# nt08.net
KiCad netlist of a schematic drawn in EAGLE
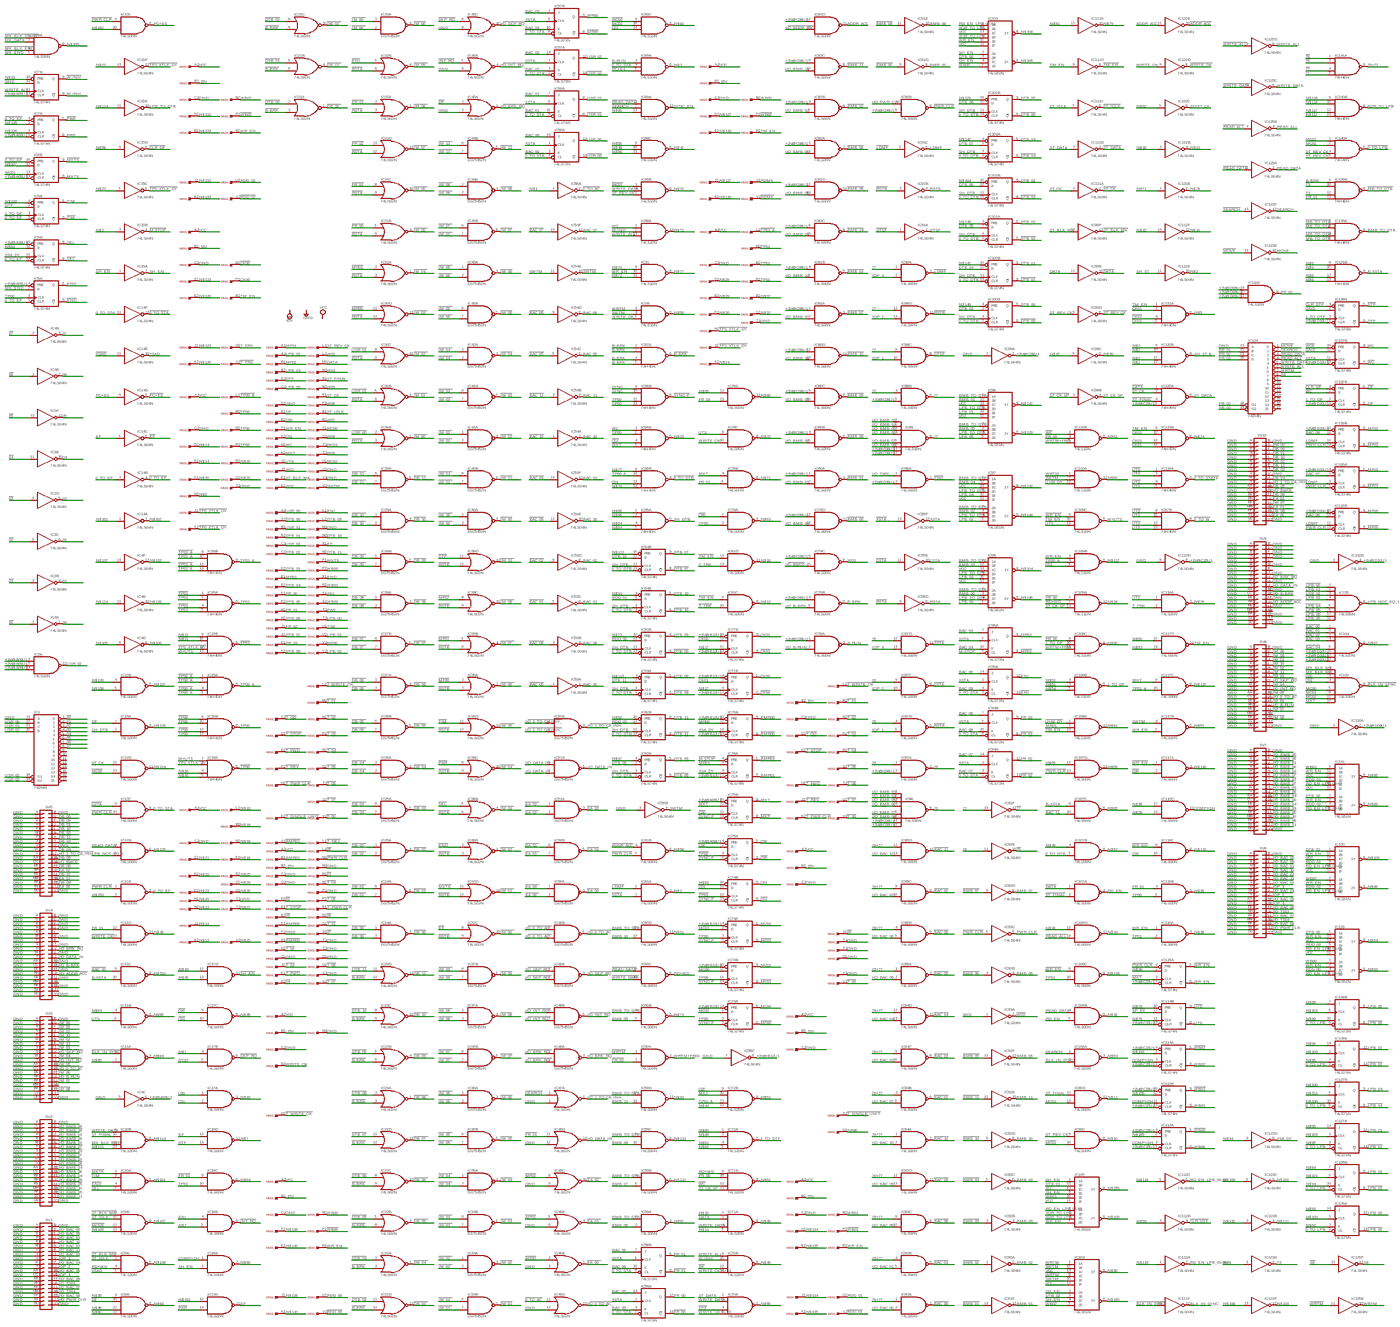
[diagram p0: schematic, sheet 1, overview]
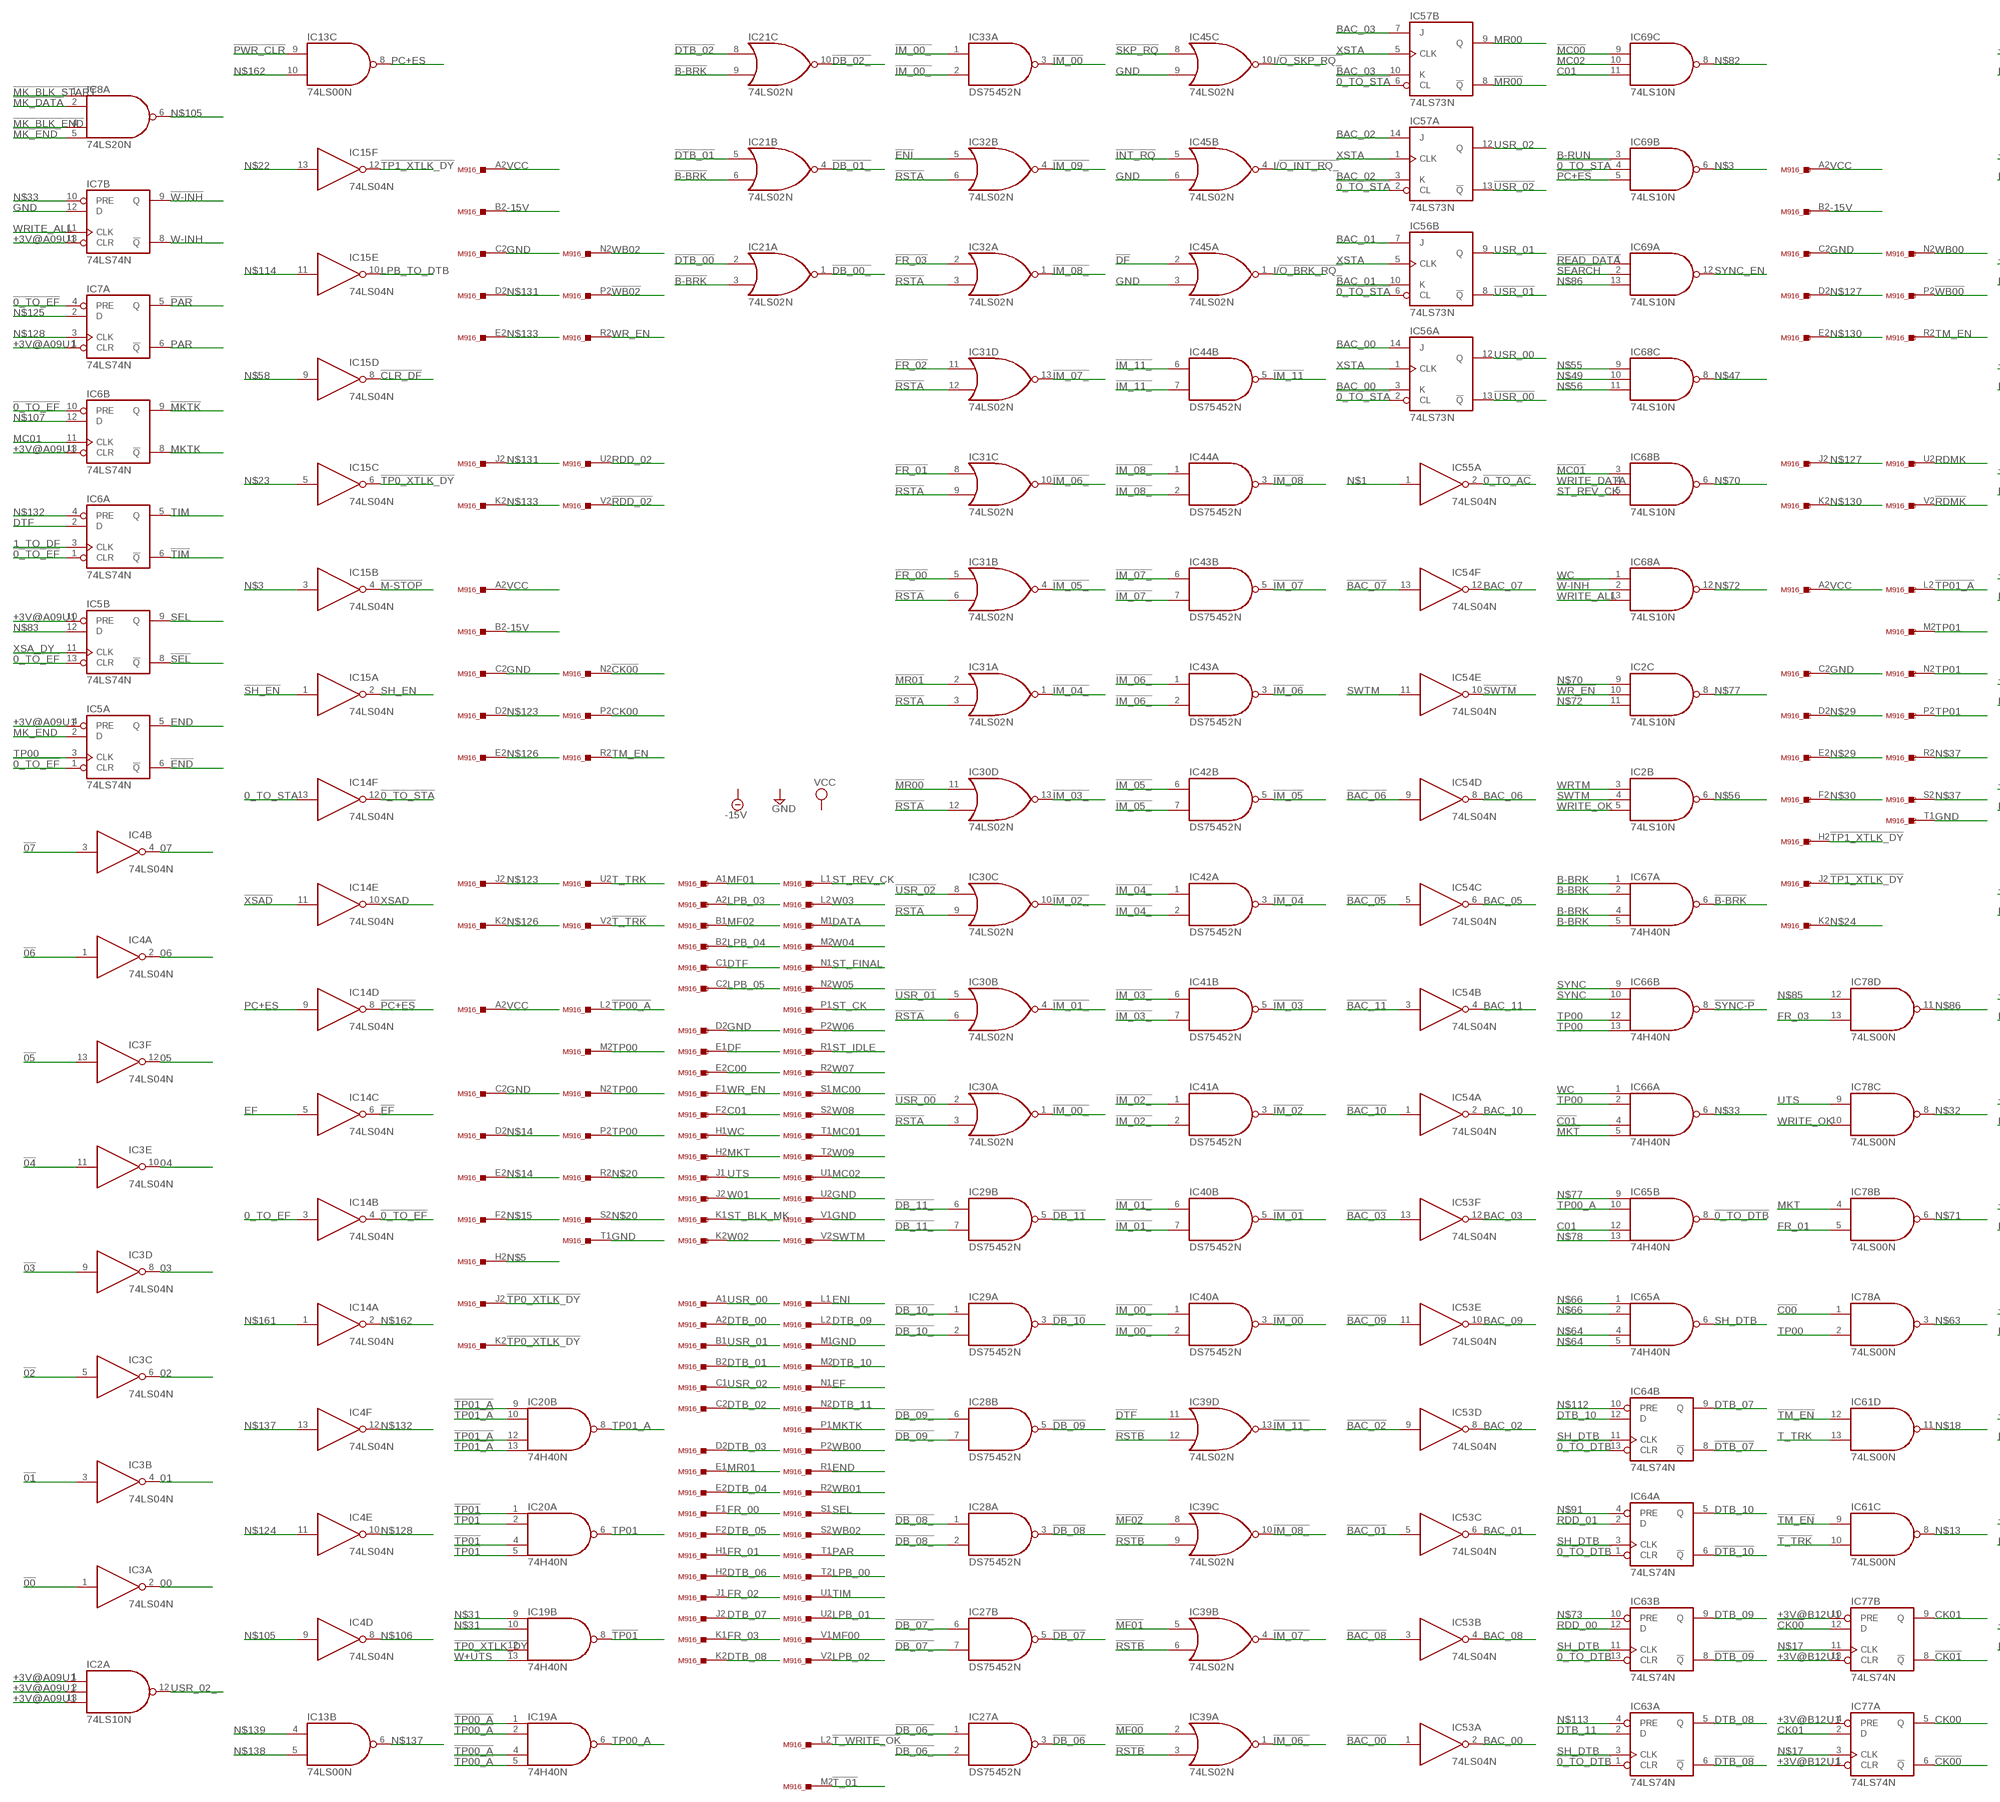
[diagram p1: schematic, sheet 1, part 1 of 4]
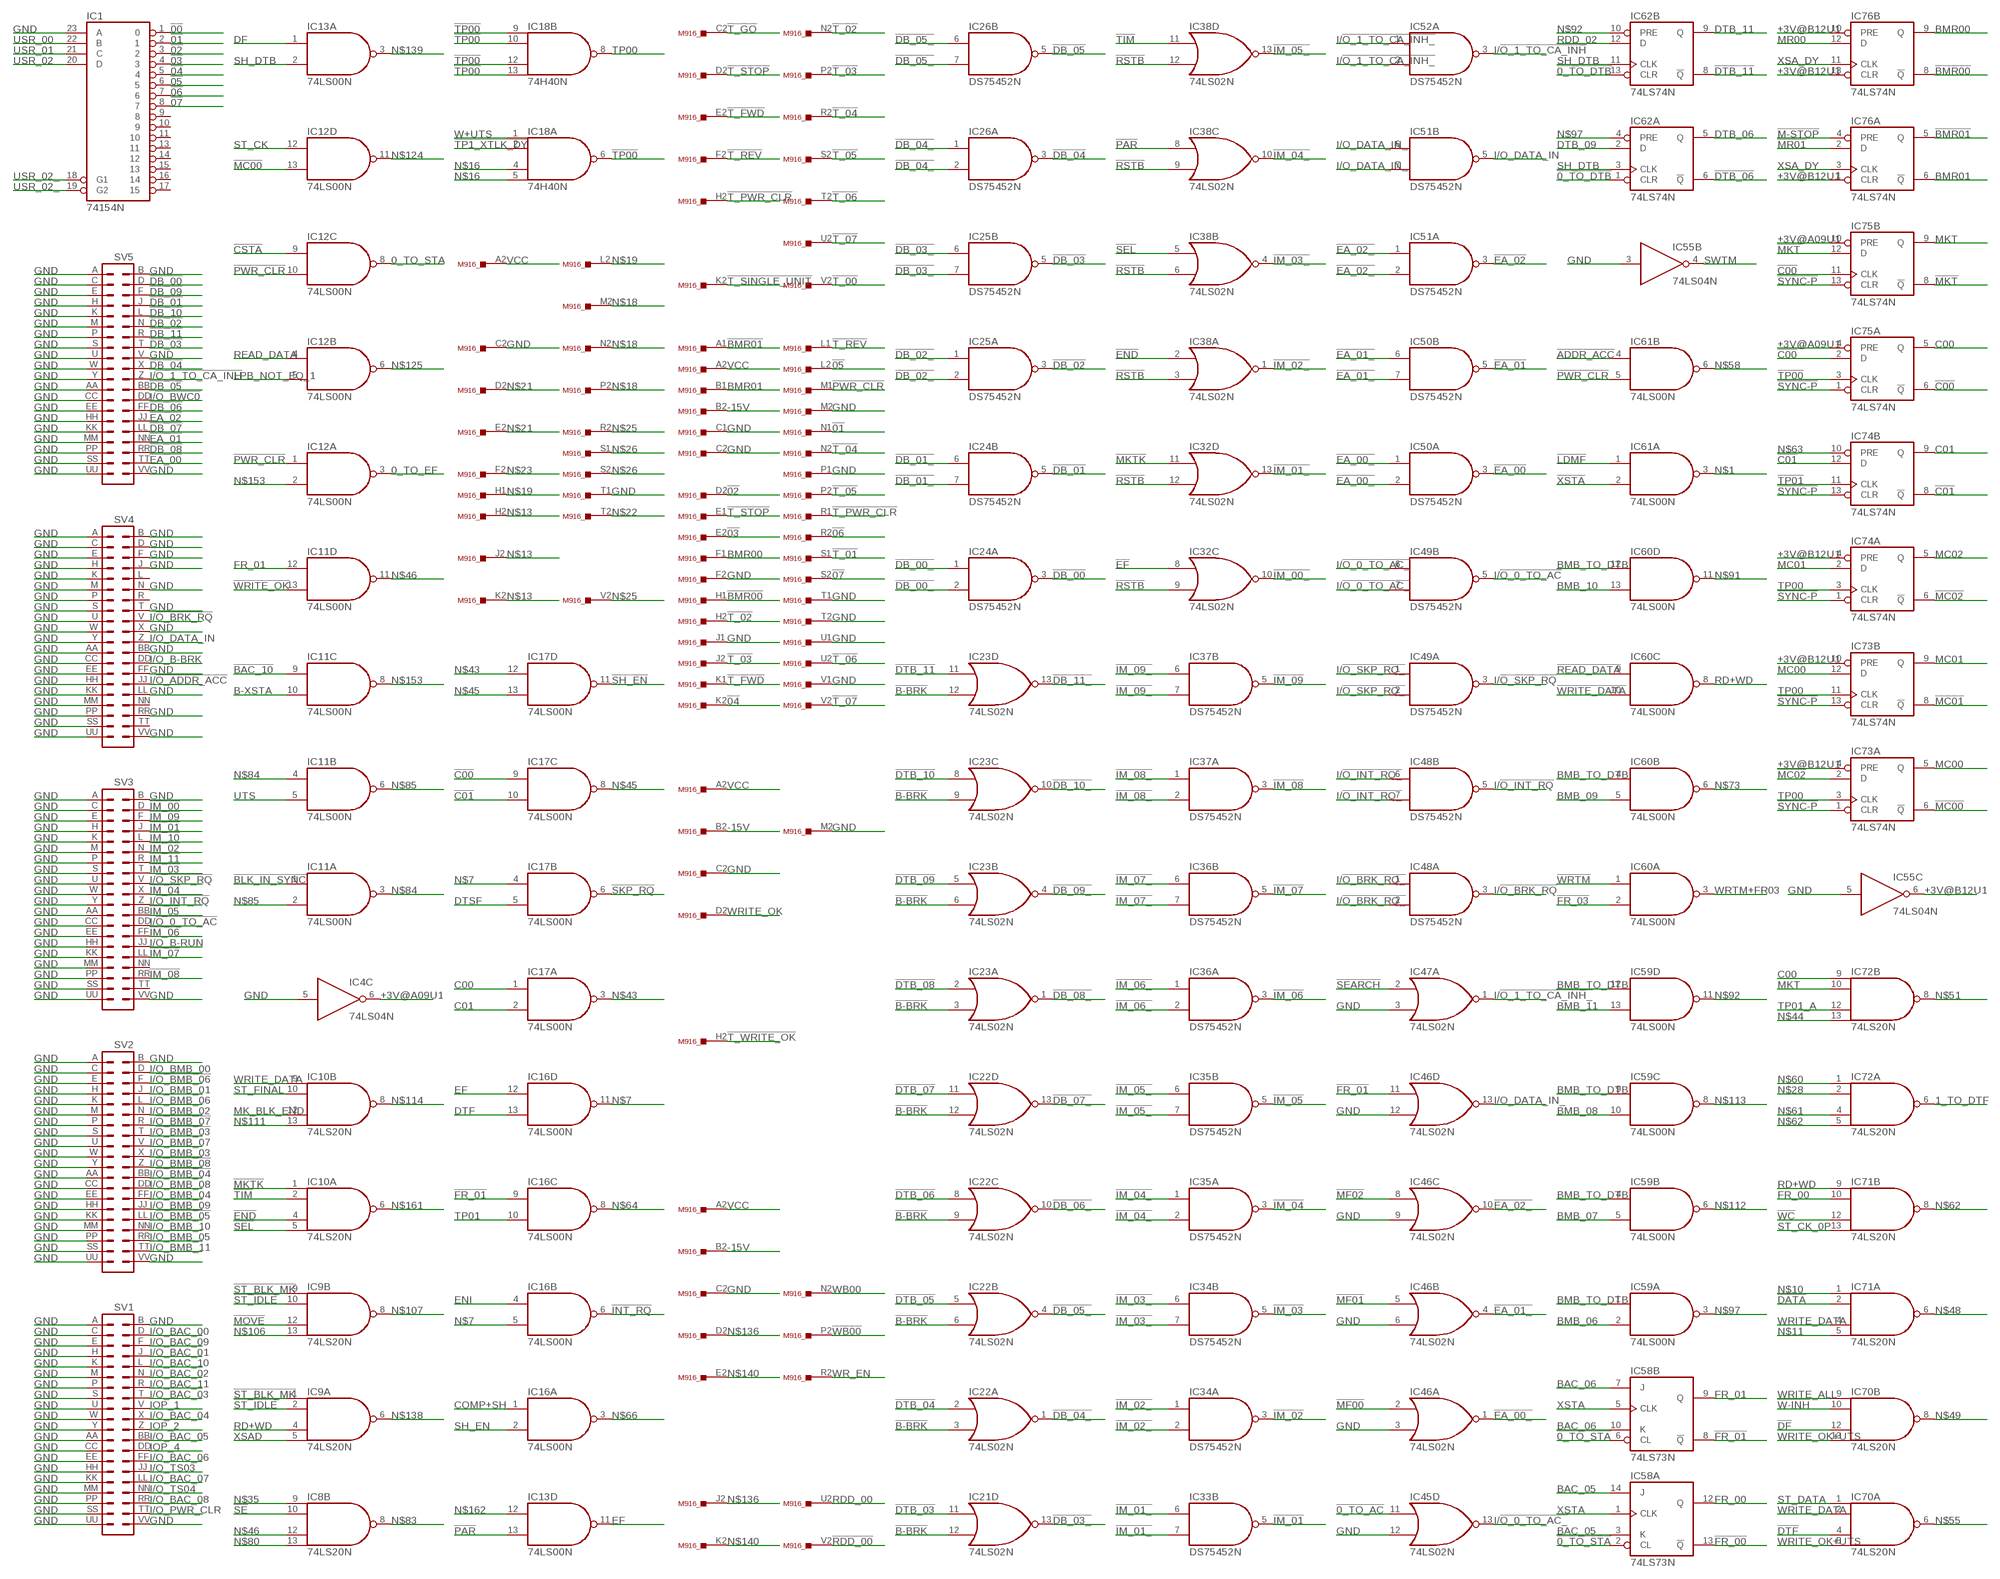
[diagram p2: schematic, sheet 1, part 2 of 4]
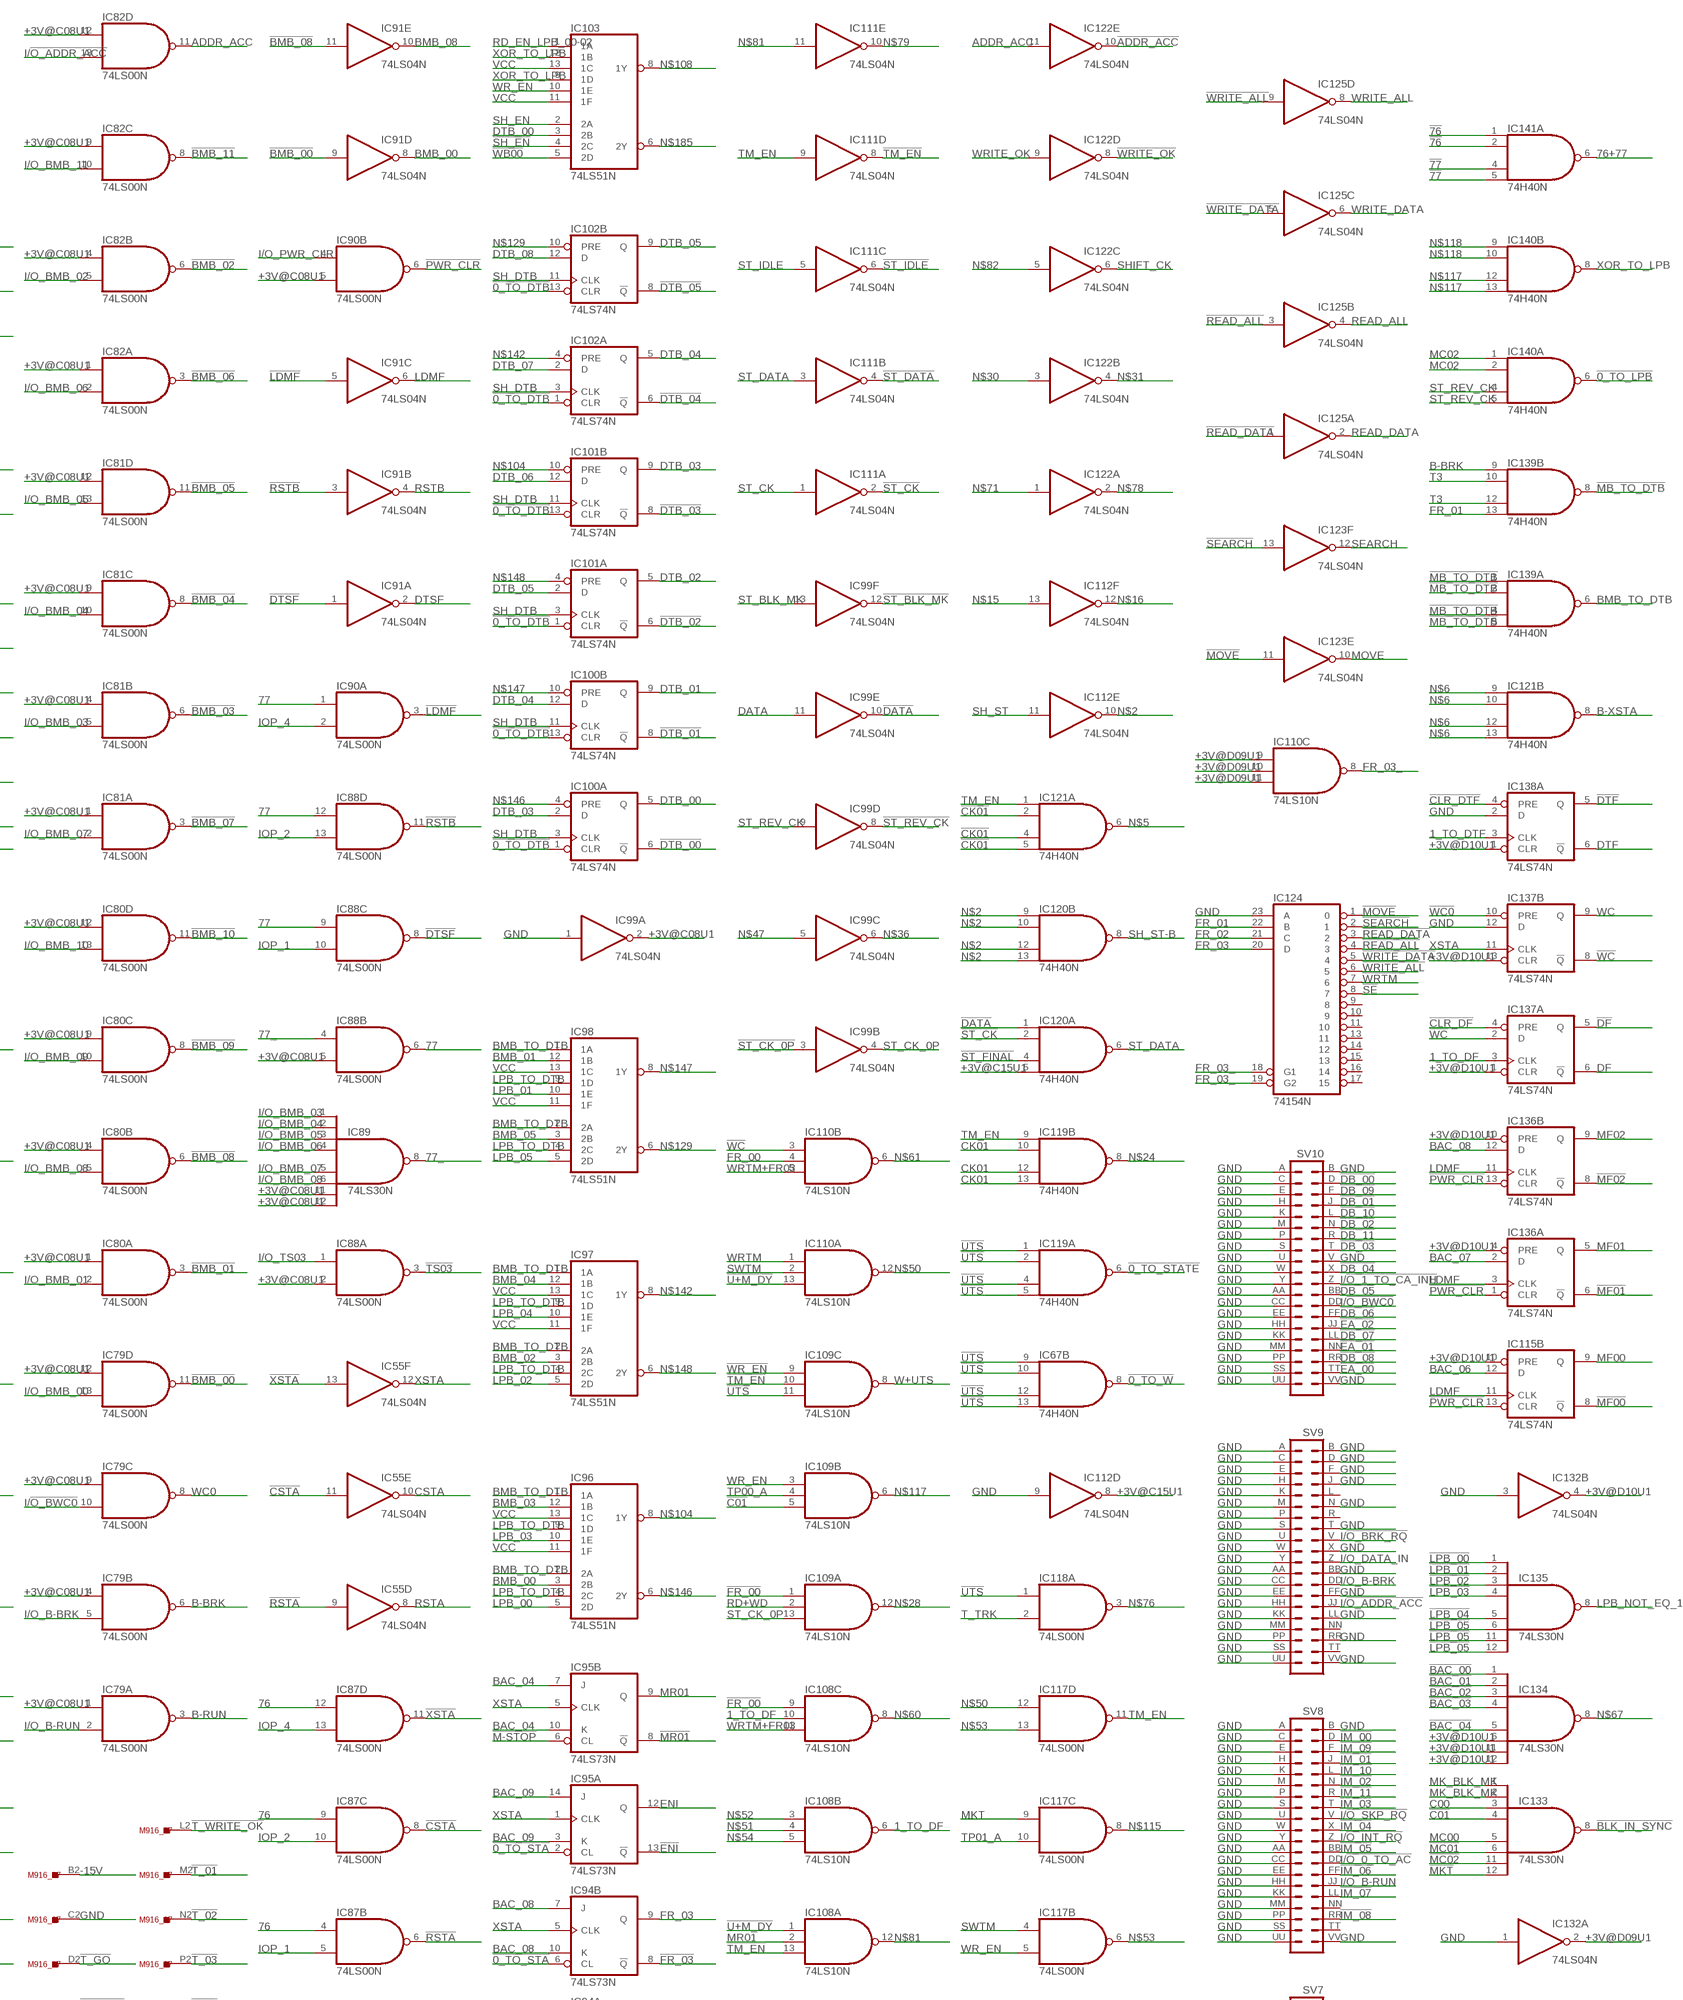
[diagram p3: schematic, sheet 1, part 3 of 4]
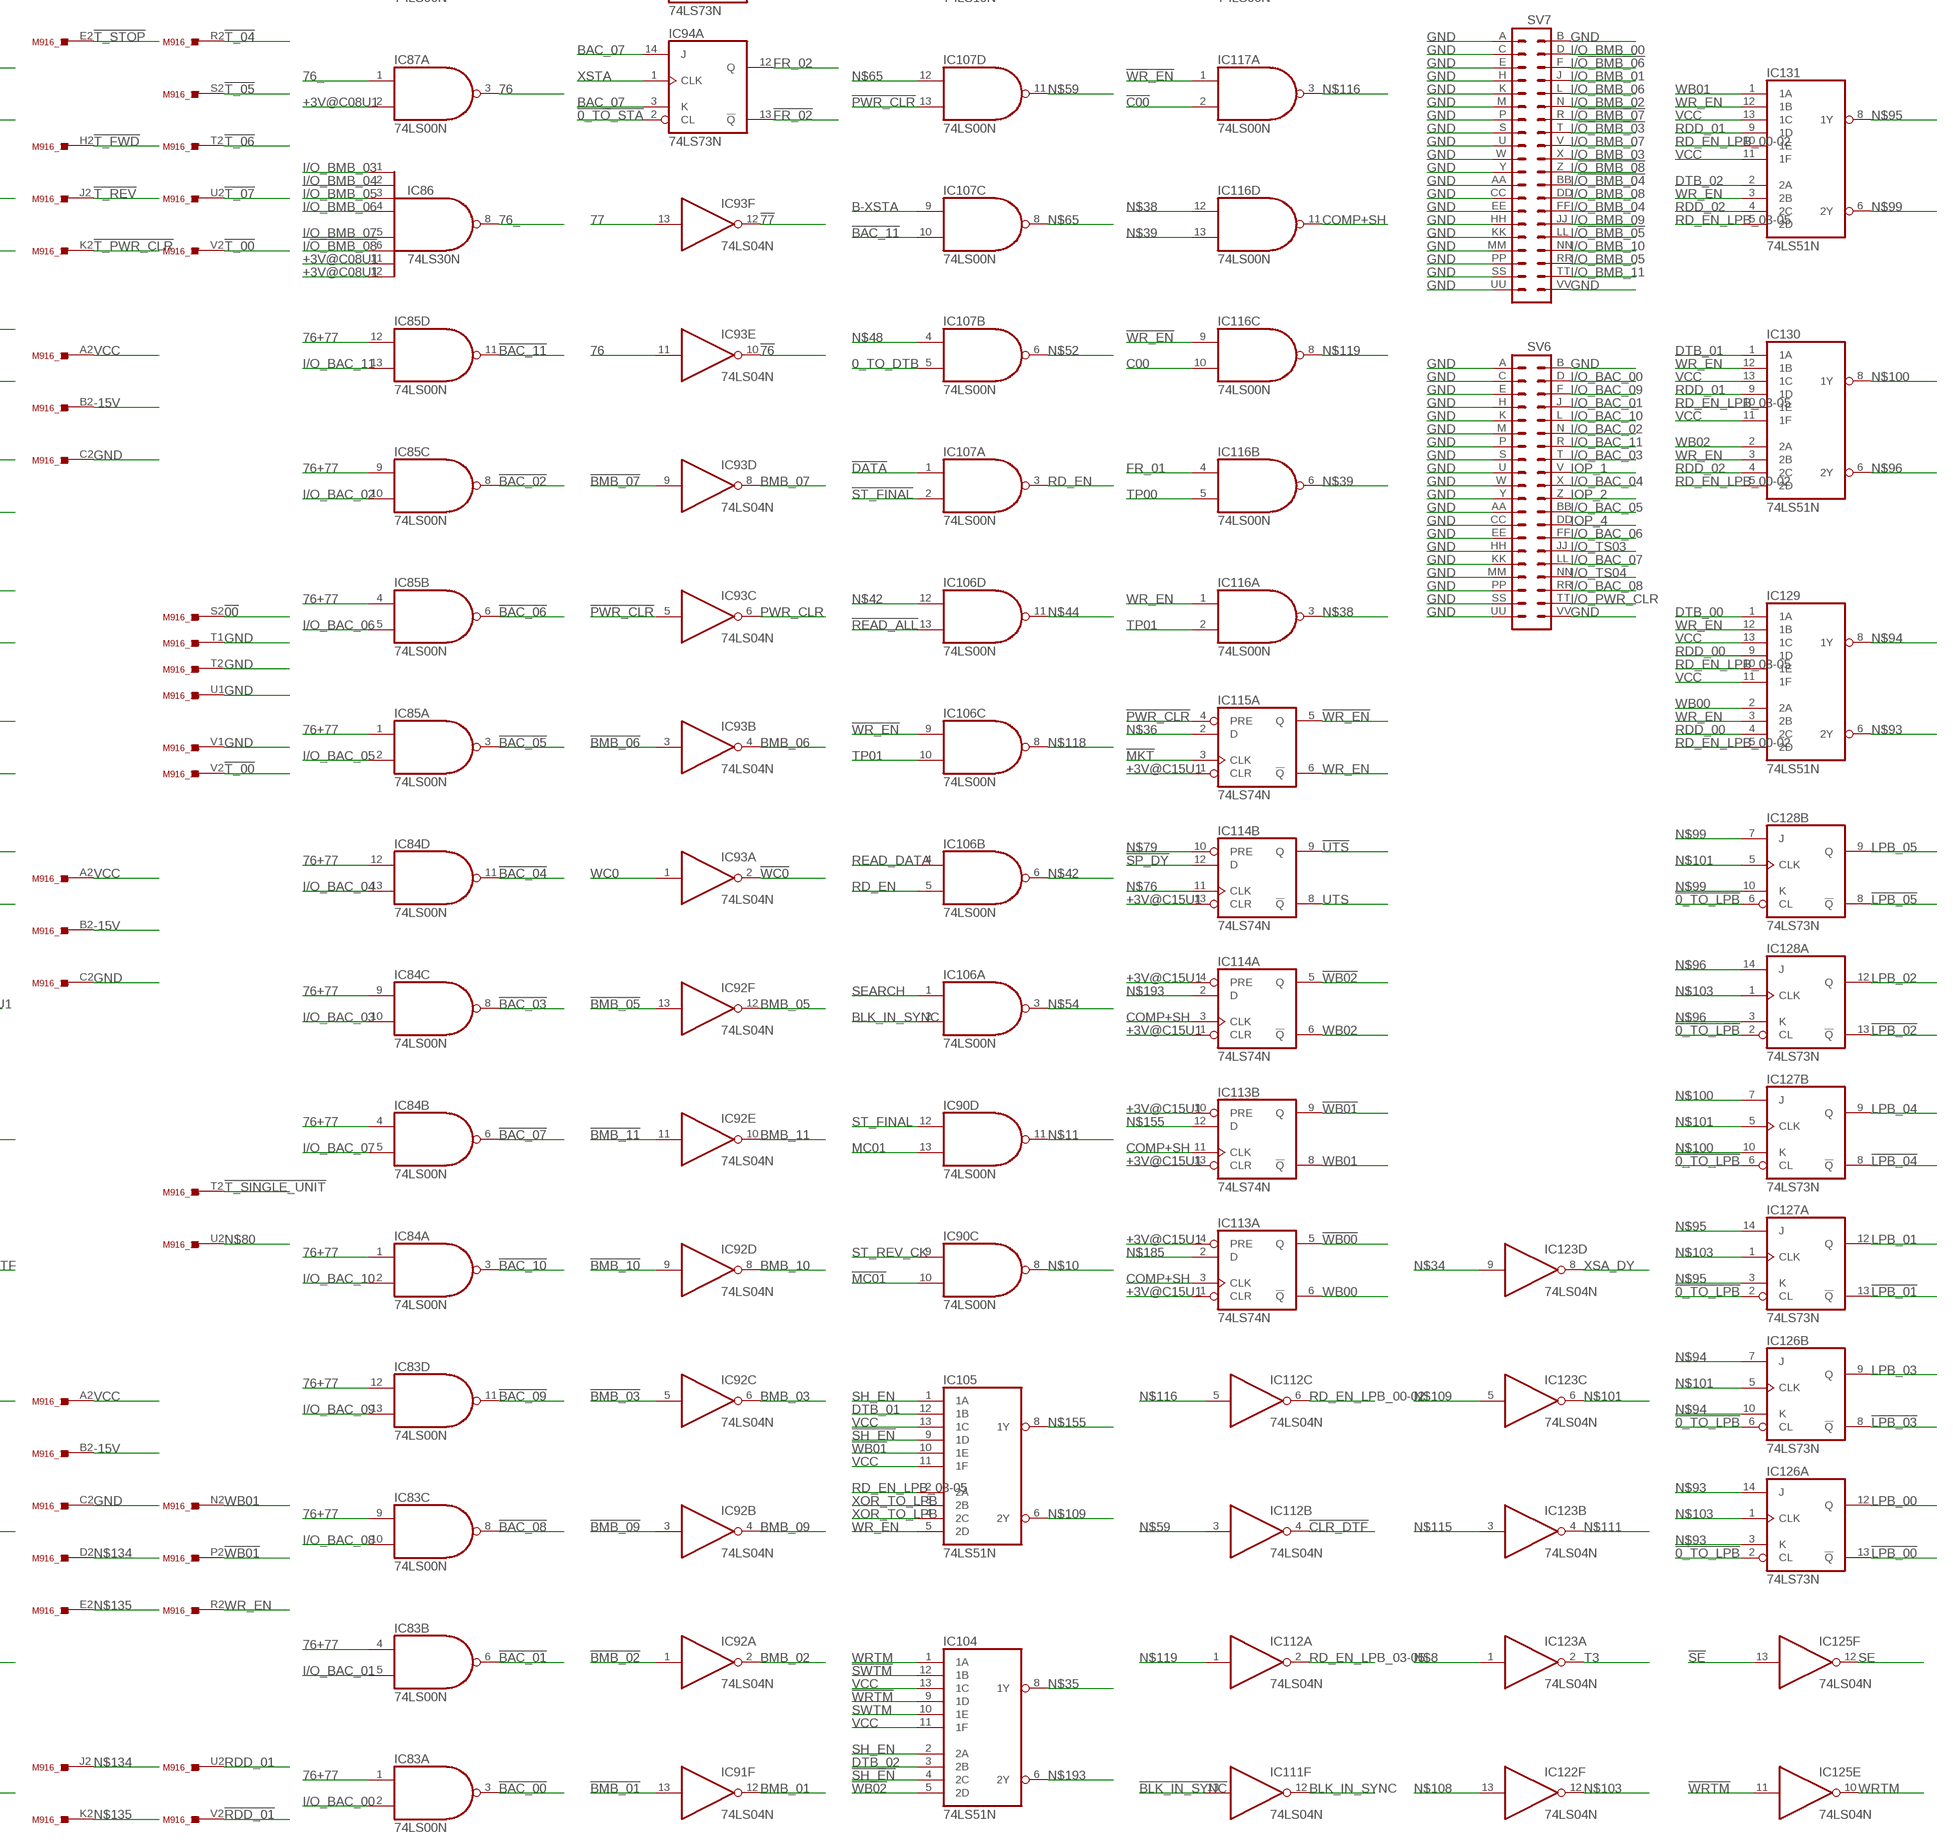
[diagram p4: schematic, sheet 1, part 4 of 4]
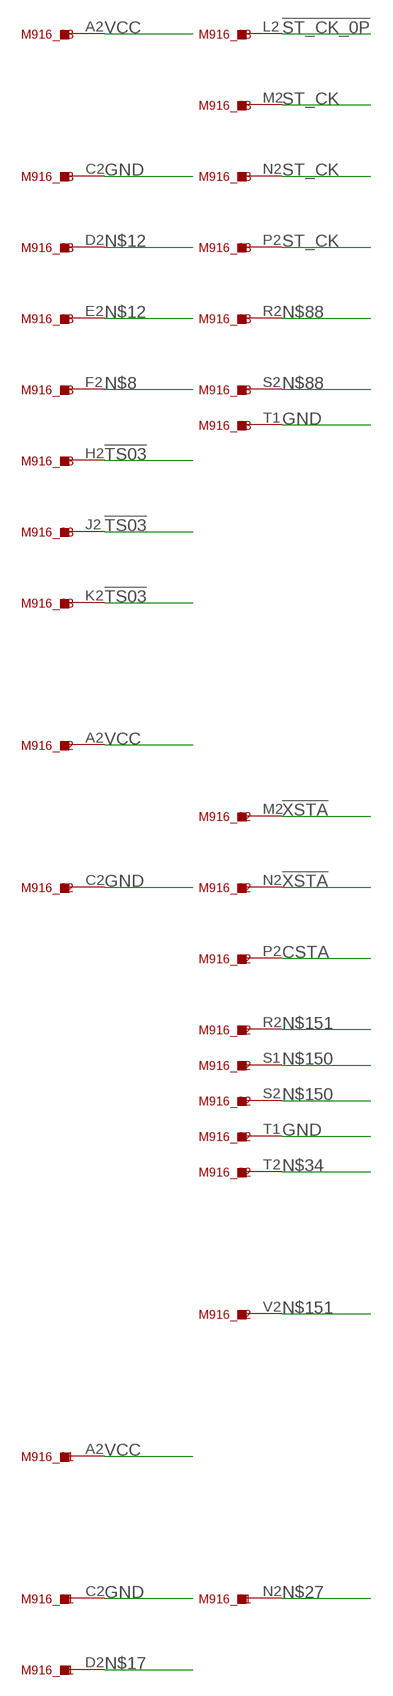
[diagram p5: schematic, sheet 2, part 1 of 2]
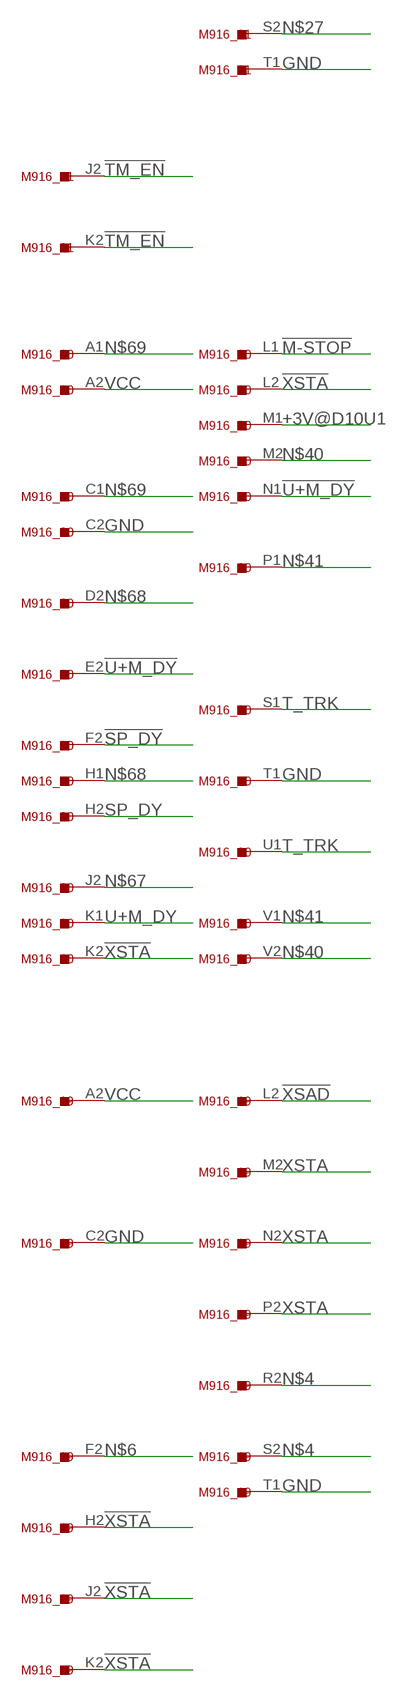
[diagram p6: schematic, sheet 2, part 2 of 2]

(export (version "E")
  (design (tool "Eeschema 10.0.6"))
  (components
    (comp (ref "M916_19")
      (value "M602")
      (footprint "eagle-import:H807")
      (libsource (lib "eagle-import") (part "M916"))
    )
    (comp (ref "M916_20")
      (value "M307")
      (footprint "eagle-import:H807")
      (libsource (lib "eagle-import") (part "M916"))
    )
    (comp (ref "M916_21")
      (value "M401")
      (footprint "eagle-import:H807")
      (libsource (lib "eagle-import") (part "M916"))
    )
    (comp (ref "M916_22")
      (value "M302")
      (footprint "eagle-import:H807")
      (libsource (lib "eagle-import") (part "M916"))
    )
    (comp (ref "M916_23")
      (value "M602")
      (footprint "eagle-import:H807")
      (libsource (lib "eagle-import") (part "M916"))
    )
    (comp (ref "IC1")
      (value "74154N")
      (footprint "eagle-import:DIL24-6")
      (libsource (lib "eagle-import") (part "74154N"))
    )
    (comp (ref "IC2")
      (value "74LS10N")
      (footprint "eagle-import:DIL14")
      (libsource (lib "eagle-import") (part "7410NLS"))
    )
    (comp (ref "IC3")
      (value "74LS04N")
      (footprint "eagle-import:DIL14")
      (libsource (lib "eagle-import") (part "7404NLS"))
    )
    (comp (ref "IC4")
      (value "74LS04N")
      (footprint "eagle-import:DIL14")
      (libsource (lib "eagle-import") (part "7404NLS"))
    )
    (comp (ref "IC5")
      (value "74LS74N")
      (footprint "eagle-import:DIL14")
      (libsource (lib "eagle-import") (part "7474NLS"))
    )
    (comp (ref "IC6")
      (value "74LS74N")
      (footprint "eagle-import:DIL14")
      (libsource (lib "eagle-import") (part "7474NLS"))
    )
    (comp (ref "IC7")
      (value "74LS74N")
      (footprint "eagle-import:DIL14")
      (libsource (lib "eagle-import") (part "7474NLS"))
    )
    (comp (ref "IC8")
      (value "74LS20N")
      (footprint "eagle-import:DIL14")
      (libsource (lib "eagle-import") (part "7420NLS"))
    )
    (comp (ref "IC9")
      (value "74LS20N")
      (footprint "eagle-import:DIL14")
      (libsource (lib "eagle-import") (part "7420NLS"))
    )
    (comp (ref "IC10")
      (value "74LS20N")
      (footprint "eagle-import:DIL14")
      (libsource (lib "eagle-import") (part "7420NLS"))
    )
    (comp (ref "IC11")
      (value "74LS00N")
      (footprint "eagle-import:DIL14")
      (libsource (lib "eagle-import") (part "7400NLS"))
    )
    (comp (ref "IC12")
      (value "74LS00N")
      (footprint "eagle-import:DIL14")
      (libsource (lib "eagle-import") (part "7400NLS"))
    )
    (comp (ref "IC13")
      (value "74LS00N")
      (footprint "eagle-import:DIL14")
      (libsource (lib "eagle-import") (part "7400NLS"))
    )
    (comp (ref "IC14")
      (value "74LS04N")
      (footprint "eagle-import:DIL14")
      (libsource (lib "eagle-import") (part "7404NLS"))
    )
    (comp (ref "IC15")
      (value "74LS04N")
      (footprint "eagle-import:DIL14")
      (libsource (lib "eagle-import") (part "7404NLS"))
    )
    (comp (ref "IC16")
      (value "74LS00N")
      (footprint "eagle-import:DIL14")
      (libsource (lib "eagle-import") (part "7400NLS"))
    )
    (comp (ref "IC17")
      (value "74LS00N")
      (footprint "eagle-import:DIL14")
      (libsource (lib "eagle-import") (part "7400NLS"))
    )
    (comp (ref "IC18")
      (value "74H40N")
      (footprint "eagle-import:DIL14")
      (libsource (lib "eagle-import") (part "7420NS"))
    )
    (comp (ref "IC19")
      (value "74H40N")
      (footprint "eagle-import:DIL14")
      (libsource (lib "eagle-import") (part "7420NS"))
    )
    (comp (ref "IC20")
      (value "74H40N")
      (footprint "eagle-import:DIL14")
      (libsource (lib "eagle-import") (part "7420NS"))
    )
    (comp (ref "IC21")
      (value "74LS02N")
      (footprint "eagle-import:DIL14")
      (libsource (lib "eagle-import") (part "7402NLS"))
    )
    (comp (ref "IC22")
      (value "74LS02N")
      (footprint "eagle-import:DIL14")
      (libsource (lib "eagle-import") (part "7402NLS"))
    )
    (comp (ref "IC23")
      (value "74LS02N")
      (footprint "eagle-import:DIL14")
      (libsource (lib "eagle-import") (part "7402NLS"))
    )
    (comp (ref "IC24")
      (value "DS75452N")
      (footprint "eagle-import:DIL08")
      (libsource (lib "eagle-import") (part "DS75452N"))
    )
    (comp (ref "IC25")
      (value "DS75452N")
      (footprint "eagle-import:DIL08")
      (libsource (lib "eagle-import") (part "DS75452N"))
    )
    (comp (ref "IC26")
      (value "DS75452N")
      (footprint "eagle-import:DIL08")
      (libsource (lib "eagle-import") (part "DS75452N"))
    )
    (comp (ref "IC27")
      (value "DS75452N")
      (footprint "eagle-import:DIL08")
      (libsource (lib "eagle-import") (part "DS75452N"))
    )
    (comp (ref "IC28")
      (value "DS75452N")
      (footprint "eagle-import:DIL08")
      (libsource (lib "eagle-import") (part "DS75452N"))
    )
    (comp (ref "IC29")
      (value "DS75452N")
      (footprint "eagle-import:DIL08")
      (libsource (lib "eagle-import") (part "DS75452N"))
    )
    (comp (ref "IC30")
      (value "74LS02N")
      (footprint "eagle-import:DIL14")
      (libsource (lib "eagle-import") (part "7402NLS"))
    )
    (comp (ref "IC31")
      (value "74LS02N")
      (footprint "eagle-import:DIL14")
      (libsource (lib "eagle-import") (part "7402NLS"))
    )
    (comp (ref "IC32")
      (value "74LS02N")
      (footprint "eagle-import:DIL14")
      (libsource (lib "eagle-import") (part "7402NLS"))
    )
    (comp (ref "IC33")
      (value "DS75452N")
      (footprint "eagle-import:DIL08")
      (libsource (lib "eagle-import") (part "DS75452N"))
    )
    (comp (ref "IC34")
      (value "DS75452N")
      (footprint "eagle-import:DIL08")
      (libsource (lib "eagle-import") (part "DS75452N"))
    )
    (comp (ref "IC35")
      (value "DS75452N")
      (footprint "eagle-import:DIL08")
      (libsource (lib "eagle-import") (part "DS75452N"))
    )
    (comp (ref "IC36")
      (value "DS75452N")
      (footprint "eagle-import:DIL08")
      (libsource (lib "eagle-import") (part "DS75452N"))
    )
    (comp (ref "IC37")
      (value "DS75452N")
      (footprint "eagle-import:DIL08")
      (libsource (lib "eagle-import") (part "DS75452N"))
    )
    (comp (ref "IC38")
      (value "74LS02N")
      (footprint "eagle-import:DIL14")
      (libsource (lib "eagle-import") (part "7402NLS"))
    )
    (comp (ref "IC39")
      (value "74LS02N")
      (footprint "eagle-import:DIL14")
      (libsource (lib "eagle-import") (part "7402NLS"))
    )
    (comp (ref "IC40")
      (value "DS75452N")
      (footprint "eagle-import:DIL08")
      (libsource (lib "eagle-import") (part "DS75452N"))
    )
    (comp (ref "IC41")
      (value "DS75452N")
      (footprint "eagle-import:DIL08")
      (libsource (lib "eagle-import") (part "DS75452N"))
    )
    (comp (ref "IC42")
      (value "DS75452N")
      (footprint "eagle-import:DIL08")
      (libsource (lib "eagle-import") (part "DS75452N"))
    )
    (comp (ref "IC43")
      (value "DS75452N")
      (footprint "eagle-import:DIL08")
      (libsource (lib "eagle-import") (part "DS75452N"))
    )
    (comp (ref "IC44")
      (value "DS75452N")
      (footprint "eagle-import:DIL08")
      (libsource (lib "eagle-import") (part "DS75452N"))
    )
    (comp (ref "IC45")
      (value "74LS02N")
      (footprint "eagle-import:DIL14")
      (libsource (lib "eagle-import") (part "7402NLS"))
    )
    (comp (ref "IC46")
      (value "74LS02N")
      (footprint "eagle-import:DIL14")
      (libsource (lib "eagle-import") (part "7402NLS"))
    )
    (comp (ref "IC47")
      (value "74LS02N")
      (footprint "eagle-import:DIL14")
      (libsource (lib "eagle-import") (part "7402NLS"))
    )
    (comp (ref "IC48")
      (value "DS75452N")
      (footprint "eagle-import:DIL08")
      (libsource (lib "eagle-import") (part "DS75452N"))
    )
    (comp (ref "IC49")
      (value "DS75452N")
      (footprint "eagle-import:DIL08")
      (libsource (lib "eagle-import") (part "DS75452N"))
    )
    (comp (ref "IC50")
      (value "DS75452N")
      (footprint "eagle-import:DIL08")
      (libsource (lib "eagle-import") (part "DS75452N"))
    )
    (comp (ref "IC51")
      (value "DS75452N")
      (footprint "eagle-import:DIL08")
      (libsource (lib "eagle-import") (part "DS75452N"))
    )
    (comp (ref "IC52")
      (value "DS75452N")
      (footprint "eagle-import:DIL08")
      (libsource (lib "eagle-import") (part "DS75452N"))
    )
    (comp (ref "IC53")
      (value "74LS04N")
      (footprint "eagle-import:DIL14")
      (libsource (lib "eagle-import") (part "7404NLS"))
    )
    (comp (ref "IC54")
      (value "74LS04N")
      (footprint "eagle-import:DIL14")
      (libsource (lib "eagle-import") (part "7404NLS"))
    )
    (comp (ref "IC55")
      (value "74LS04N")
      (footprint "eagle-import:DIL14")
      (libsource (lib "eagle-import") (part "7404NLS"))
    )
    (comp (ref "IC56")
      (value "74LS73N")
      (footprint "eagle-import:DIL14")
      (libsource (lib "eagle-import") (part "7473NLS"))
    )
    (comp (ref "IC57")
      (value "74LS73N")
      (footprint "eagle-import:DIL14")
      (libsource (lib "eagle-import") (part "7473NLS"))
    )
    (comp (ref "IC58")
      (value "74LS73N")
      (footprint "eagle-import:DIL14")
      (libsource (lib "eagle-import") (part "7473NLS"))
    )
    (comp (ref "IC59")
      (value "74LS00N")
      (footprint "eagle-import:DIL14")
      (libsource (lib "eagle-import") (part "7400NLS"))
    )
    (comp (ref "IC60")
      (value "74LS00N")
      (footprint "eagle-import:DIL14")
      (libsource (lib "eagle-import") (part "7400NLS"))
    )
    (comp (ref "IC61")
      (value "74LS00N")
      (footprint "eagle-import:DIL14")
      (libsource (lib "eagle-import") (part "7400NLS"))
    )
    (comp (ref "IC62")
      (value "74LS74N")
      (footprint "eagle-import:DIL14")
      (libsource (lib "eagle-import") (part "7474NLS"))
    )
    (comp (ref "IC63")
      (value "74LS74N")
      (footprint "eagle-import:DIL14")
      (libsource (lib "eagle-import") (part "7474NLS"))
    )
    (comp (ref "IC64")
      (value "74LS74N")
      (footprint "eagle-import:DIL14")
      (libsource (lib "eagle-import") (part "7474NLS"))
    )
    (comp (ref "IC65")
      (value "74H40N")
      (footprint "eagle-import:DIL14")
      (libsource (lib "eagle-import") (part "7420NS"))
    )
    (comp (ref "IC66")
      (value "74H40N")
      (footprint "eagle-import:DIL14")
      (libsource (lib "eagle-import") (part "7420NS"))
    )
    (comp (ref "IC67")
      (value "74H40N")
      (footprint "eagle-import:DIL14")
      (libsource (lib "eagle-import") (part "7420NS"))
    )
    (comp (ref "IC68")
      (value "74LS10N")
      (footprint "eagle-import:DIL14")
      (libsource (lib "eagle-import") (part "7410NLS"))
    )
    (comp (ref "IC69")
      (value "74LS10N")
      (footprint "eagle-import:DIL14")
      (libsource (lib "eagle-import") (part "7410NLS"))
    )
    (comp (ref "IC70")
      (value "74LS20N")
      (footprint "eagle-import:DIL14")
      (libsource (lib "eagle-import") (part "7420NLS"))
    )
    (comp (ref "IC71")
      (value "74LS20N")
      (footprint "eagle-import:DIL14")
      (libsource (lib "eagle-import") (part "7420NLS"))
    )
    (comp (ref "IC72")
      (value "74LS20N")
      (footprint "eagle-import:DIL14")
      (libsource (lib "eagle-import") (part "7420NLS"))
    )
    (comp (ref "IC73")
      (value "74LS74N")
      (footprint "eagle-import:DIL14")
      (libsource (lib "eagle-import") (part "7474NLS"))
    )
    (comp (ref "IC74")
      (value "74LS74N")
      (footprint "eagle-import:DIL14")
      (libsource (lib "eagle-import") (part "7474NLS"))
    )
    (comp (ref "IC75")
      (value "74LS74N")
      (footprint "eagle-import:DIL14")
      (libsource (lib "eagle-import") (part "7474NLS"))
    )
    (comp (ref "IC76")
      (value "74LS74N")
      (footprint "eagle-import:DIL14")
      (libsource (lib "eagle-import") (part "7474NLS"))
    )
    (comp (ref "IC77")
      (value "74LS74N")
      (footprint "eagle-import:DIL14")
      (libsource (lib "eagle-import") (part "7474NLS"))
    )
    (comp (ref "IC78")
      (value "74LS00N")
      (footprint "eagle-import:DIL14")
      (libsource (lib "eagle-import") (part "7400NLS"))
    )
    (comp (ref "IC79")
      (value "74LS00N")
      (footprint "eagle-import:DIL14")
      (libsource (lib "eagle-import") (part "7400NLS"))
    )
    (comp (ref "IC80")
      (value "74LS00N")
      (footprint "eagle-import:DIL14")
      (libsource (lib "eagle-import") (part "7400NLS"))
    )
    (comp (ref "IC81")
      (value "74LS00N")
      (footprint "eagle-import:DIL14")
      (libsource (lib "eagle-import") (part "7400NLS"))
    )
    (comp (ref "IC82")
      (value "74LS00N")
      (footprint "eagle-import:DIL14")
      (libsource (lib "eagle-import") (part "7400NLS"))
    )
    (comp (ref "IC83")
      (value "74LS00N")
      (footprint "eagle-import:DIL14")
      (libsource (lib "eagle-import") (part "7400NLS"))
    )
    (comp (ref "IC84")
      (value "74LS00N")
      (footprint "eagle-import:DIL14")
      (libsource (lib "eagle-import") (part "7400NLS"))
    )
    (comp (ref "IC85")
      (value "74LS00N")
      (footprint "eagle-import:DIL14")
      (libsource (lib "eagle-import") (part "7400NLS"))
    )
    (comp (ref "IC86")
      (value "74LS30N")
      (footprint "eagle-import:DIL14")
      (libsource (lib "eagle-import") (part "7430NLS"))
    )
    (comp (ref "IC87")
      (value "74LS00N")
      (footprint "eagle-import:DIL14")
      (libsource (lib "eagle-import") (part "7400NLS"))
    )
    (comp (ref "IC88")
      (value "74LS00N")
      (footprint "eagle-import:DIL14")
      (libsource (lib "eagle-import") (part "7400NLS"))
    )
    (comp (ref "IC89")
      (value "74LS30N")
      (footprint "eagle-import:DIL14")
      (libsource (lib "eagle-import") (part "7430NLS"))
    )
    (comp (ref "IC90")
      (value "74LS00N")
      (footprint "eagle-import:DIL14")
      (libsource (lib "eagle-import") (part "7400NLS"))
    )
    (comp (ref "IC91")
      (value "74LS04N")
      (footprint "eagle-import:DIL14")
      (libsource (lib "eagle-import") (part "7404NLS"))
    )
    (comp (ref "IC92")
      (value "74LS04N")
      (footprint "eagle-import:DIL14")
      (libsource (lib "eagle-import") (part "7404NLS"))
    )
    (comp (ref "IC93")
      (value "74LS04N")
      (footprint "eagle-import:DIL14")
      (libsource (lib "eagle-import") (part "7404NLS"))
    )
    (comp (ref "IC94")
      (value "74LS73N")
      (footprint "eagle-import:DIL14")
      (libsource (lib "eagle-import") (part "7473NLS"))
    )
    (comp (ref "IC95")
      (value "74LS73N")
      (footprint "eagle-import:DIL14")
      (libsource (lib "eagle-import") (part "7473NLS"))
    )
    (comp (ref "IC96")
      (value "74LS51N")
      (footprint "eagle-import:DIL14")
      (libsource (lib "eagle-import") (part "7451NLS"))
    )
    (comp (ref "IC97")
      (value "74LS51N")
      (footprint "eagle-import:DIL14")
      (libsource (lib "eagle-import") (part "7451NLS"))
    )
    (comp (ref "IC98")
      (value "74LS51N")
      (footprint "eagle-import:DIL14")
      (libsource (lib "eagle-import") (part "7451NLS"))
    )
    (comp (ref "IC99")
      (value "74LS04N")
      (footprint "eagle-import:DIL14")
      (libsource (lib "eagle-import") (part "7404NLS"))
    )
    (comp (ref "IC100")
      (value "74LS74N")
      (footprint "eagle-import:DIL14")
      (libsource (lib "eagle-import") (part "7474NLS"))
    )
    (comp (ref "IC101")
      (value "74LS74N")
      (footprint "eagle-import:DIL14")
      (libsource (lib "eagle-import") (part "7474NLS"))
    )
    (comp (ref "IC102")
      (value "74LS74N")
      (footprint "eagle-import:DIL14")
      (libsource (lib "eagle-import") (part "7474NLS"))
    )
    (comp (ref "IC103")
      (value "74LS51N")
      (footprint "eagle-import:DIL14")
      (libsource (lib "eagle-import") (part "7451NLS"))
    )
    (comp (ref "IC104")
      (value "74LS51N")
      (footprint "eagle-import:DIL14")
      (libsource (lib "eagle-import") (part "7451NLS"))
    )
    (comp (ref "IC105")
      (value "74LS51N")
      (footprint "eagle-import:DIL14")
      (libsource (lib "eagle-import") (part "7451NLS"))
    )
    (comp (ref "IC106")
      (value "74LS00N")
      (footprint "eagle-import:DIL14")
      (libsource (lib "eagle-import") (part "7400NLS"))
    )
    (comp (ref "IC107")
      (value "74LS00N")
      (footprint "eagle-import:DIL14")
      (libsource (lib "eagle-import") (part "7400NLS"))
    )
    (comp (ref "IC108")
      (value "74LS10N")
      (footprint "eagle-import:DIL14")
      (libsource (lib "eagle-import") (part "7410NLS"))
    )
    (comp (ref "IC109")
      (value "74LS10N")
      (footprint "eagle-import:DIL14")
      (libsource (lib "eagle-import") (part "7410NLS"))
    )
    (comp (ref "IC110")
      (value "74LS10N")
      (footprint "eagle-import:DIL14")
      (libsource (lib "eagle-import") (part "7410NLS"))
    )
    (comp (ref "IC111")
      (value "74LS04N")
      (footprint "eagle-import:DIL14")
      (libsource (lib "eagle-import") (part "7404NLS"))
    )
    (comp (ref "IC112")
      (value "74LS04N")
      (footprint "eagle-import:DIL14")
      (libsource (lib "eagle-import") (part "7404NLS"))
    )
    (comp (ref "IC113")
      (value "74LS74N")
      (footprint "eagle-import:DIL14")
      (libsource (lib "eagle-import") (part "7474NLS"))
    )
    (comp (ref "IC114")
      (value "74LS74N")
      (footprint "eagle-import:DIL14")
      (libsource (lib "eagle-import") (part "7474NLS"))
    )
    (comp (ref "IC115")
      (value "74LS74N")
      (footprint "eagle-import:DIL14")
      (libsource (lib "eagle-import") (part "7474NLS"))
    )
    (comp (ref "IC116")
      (value "74LS00N")
      (footprint "eagle-import:DIL14")
      (libsource (lib "eagle-import") (part "7400NLS"))
    )
    (comp (ref "IC117")
      (value "74LS00N")
      (footprint "eagle-import:DIL14")
      (libsource (lib "eagle-import") (part "7400NLS"))
    )
    (comp (ref "IC118")
      (value "74LS00N")
      (footprint "eagle-import:DIL14")
      (libsource (lib "eagle-import") (part "7400NLS"))
    )
    (comp (ref "IC119")
      (value "74H40N")
      (footprint "eagle-import:DIL14")
      (libsource (lib "eagle-import") (part "7420NS"))
    )
    (comp (ref "IC120")
      (value "74H40N")
      (footprint "eagle-import:DIL14")
      (libsource (lib "eagle-import") (part "7420NS"))
    )
    (comp (ref "IC121")
      (value "74H40N")
      (footprint "eagle-import:DIL14")
      (libsource (lib "eagle-import") (part "7420NS"))
    )
    (comp (ref "IC122")
      (value "74LS04N")
      (footprint "eagle-import:DIL14")
      (libsource (lib "eagle-import") (part "7404NLS"))
    )
    (comp (ref "IC123")
      (value "74LS04N")
      (footprint "eagle-import:DIL14")
      (libsource (lib "eagle-import") (part "7404NLS"))
    )
    (comp (ref "IC124")
      (value "74154N")
      (footprint "eagle-import:DIL24-6")
      (libsource (lib "eagle-import") (part "74154N"))
    )
    (comp (ref "IC125")
      (value "74LS04N")
      (footprint "eagle-import:DIL14")
      (libsource (lib "eagle-import") (part "7404NLS"))
    )
    (comp (ref "IC126")
      (value "74LS73N")
      (footprint "eagle-import:DIL14")
      (libsource (lib "eagle-import") (part "7473NLS"))
    )
    (comp (ref "IC127")
      (value "74LS73N")
      (footprint "eagle-import:DIL14")
      (libsource (lib "eagle-import") (part "7473NLS"))
    )
    (comp (ref "IC128")
      (value "74LS73N")
      (footprint "eagle-import:DIL14")
      (libsource (lib "eagle-import") (part "7473NLS"))
    )
    (comp (ref "IC129")
      (value "74LS51N")
      (footprint "eagle-import:DIL14")
      (libsource (lib "eagle-import") (part "7451NLS"))
    )
    (comp (ref "IC130")
      (value "74LS51N")
      (footprint "eagle-import:DIL14")
      (libsource (lib "eagle-import") (part "7451NLS"))
    )
    (comp (ref "IC131")
      (value "74LS51N")
      (footprint "eagle-import:DIL14")
      (libsource (lib "eagle-import") (part "7451NLS"))
    )
    (comp (ref "IC132")
      (value "74LS04N")
      (footprint "eagle-import:DIL14")
      (libsource (lib "eagle-import") (part "7404NLS"))
    )
    (comp (ref "IC133")
      (value "74LS30N")
      (footprint "eagle-import:DIL14")
      (libsource (lib "eagle-import") (part "7430NLS"))
    )
    (comp (ref "IC134")
      (value "74LS30N")
      (footprint "eagle-import:DIL14")
      (libsource (lib "eagle-import") (part "7430NLS"))
    )
    (comp (ref "IC135")
      (value "74LS30N")
      (footprint "eagle-import:DIL14")
      (libsource (lib "eagle-import") (part "7430NLS"))
    )
    (comp (ref "IC136")
      (value "74LS74N")
      (footprint "eagle-import:DIL14")
      (libsource (lib "eagle-import") (part "7474NLS"))
    )
    (comp (ref "IC137")
      (value "74LS74N")
      (footprint "eagle-import:DIL14")
      (libsource (lib "eagle-import") (part "7474NLS"))
    )
    (comp (ref "IC138")
      (value "74LS74N")
      (footprint "eagle-import:DIL14")
      (libsource (lib "eagle-import") (part "7474NLS"))
    )
    (comp (ref "IC139")
      (value "74H40N")
      (footprint "eagle-import:DIL14")
      (libsource (lib "eagle-import") (part "7420NS"))
    )
    (comp (ref "IC140")
      (value "74H40N")
      (footprint "eagle-import:DIL14")
      (libsource (lib "eagle-import") (part "7420NS"))
    )
    (comp (ref "IC141")
      (value "74H40N")
      (footprint "eagle-import:DIL14")
      (libsource (lib "eagle-import") (part "7420NS"))
    )
    (comp (ref "M916_1")
      (value "M302")
      (footprint "eagle-import:H807")
      (libsource (lib "eagle-import") (part "M916"))
    )
    (comp (ref "M916_2")
      (value "M602")
      (footprint "eagle-import:H807")
      (libsource (lib "eagle-import") (part "M916"))
    )
    (comp (ref "M916_3")
      (value "G888")
      (footprint "eagle-import:H807")
      (libsource (lib "eagle-import") (part "M916"))
    )
    (comp (ref "M916_4")
      (value "M302")
      (footprint "eagle-import:H807")
      (libsource (lib "eagle-import") (part "M916"))
    )
    (comp (ref "M916_5")
      (value "G888")
      (footprint "eagle-import:H807")
      (libsource (lib "eagle-import") (part "M916"))
    )
    (comp (ref "M916_6")
      (value "G888")
      (footprint "eagle-import:H807")
      (libsource (lib "eagle-import") (part "M916"))
    )
    (comp (ref "M916_7")
      (value "M633")
      (footprint "eagle-import:H807")
      (libsource (lib "eagle-import") (part "M916"))
    )
    (comp (ref "M916_8")
      (value "W023")
      (footprint "eagle-import:H807")
      (libsource (lib "eagle-import") (part "M916"))
    )
    (comp (ref "M916_9")
      (value "M916")
      (footprint "eagle-import:H807")
      (libsource (lib "eagle-import") (part "M916"))
    )
    (comp (ref "M916_10")
      (value "M916")
      (footprint "eagle-import:H807")
      (libsource (lib "eagle-import") (part "M916"))
    )
    (comp (ref "M916_12")
      (value "M602")
      (footprint "eagle-import:H807")
      (libsource (lib "eagle-import") (part "M916"))
    )
    (comp (ref "M916_13")
      (value "G888")
      (footprint "eagle-import:H807")
      (libsource (lib "eagle-import") (part "M916"))
    )
    (comp (ref "M916_14")
      (value "G888")
      (footprint "eagle-import:H807")
      (libsource (lib "eagle-import") (part "M916"))
    )
    (comp (ref "M916_15")
      (value "G879")
      (footprint "eagle-import:H807")
      (libsource (lib "eagle-import") (part "M916"))
    )
    (comp (ref "M916_16")
      (value "M633")
      (footprint "eagle-import:H807")
      (libsource (lib "eagle-import") (part "M916"))
    )
    (comp (ref "M916_17")
      (value "W005")
      (footprint "eagle-import:H807")
      (libsource (lib "eagle-import") (part "M916"))
    )
    (comp (ref "SV1")
      (value "DEC40PINV")
      (footprint "eagle-import:DEC40PINV")
      (libsource (lib "eagle-import") (part "DEC40PINV"))
    )
    (comp (ref "SV2")
      (value "DEC40PINV")
      (footprint "eagle-import:DEC40PINV")
      (libsource (lib "eagle-import") (part "DEC40PINV"))
    )
    (comp (ref "SV3")
      (value "DEC40PINV")
      (footprint "eagle-import:DEC40PINV")
      (libsource (lib "eagle-import") (part "DEC40PINV"))
    )
    (comp (ref "SV4")
      (value "DEC40PINV")
      (footprint "eagle-import:DEC40PINV")
      (libsource (lib "eagle-import") (part "DEC40PINV"))
    )
    (comp (ref "SV5")
      (value "DEC40PINV")
      (footprint "eagle-import:DEC40PINV")
      (libsource (lib "eagle-import") (part "DEC40PINV"))
    )
    (comp (ref "SV6")
      (value "DEC40PINV")
      (footprint "eagle-import:DEC40PINV")
      (libsource (lib "eagle-import") (part "DEC40PINV"))
    )
    (comp (ref "SV7")
      (value "DEC40PINV")
      (footprint "eagle-import:DEC40PINV")
      (libsource (lib "eagle-import") (part "DEC40PINV"))
    )
    (comp (ref "SV8")
      (value "DEC40PINV")
      (footprint "eagle-import:DEC40PINV")
      (libsource (lib "eagle-import") (part "DEC40PINV"))
    )
    (comp (ref "SV9")
      (value "DEC40PINV")
      (footprint "eagle-import:DEC40PINV")
      (libsource (lib "eagle-import") (part "DEC40PINV"))
    )
    (comp (ref "SV10")
      (value "DEC40PINV")
      (footprint "eagle-import:DEC40PINV")
      (libsource (lib "eagle-import") (part "DEC40PINV"))
    )
  )
  (nets
    (net (code "1") (name "+3V@A09U1") (class "Default")
      (node (ref "IC2") (pin "1") (pinfunction "I0_1") (pintype "input"))
      (node (ref "IC2") (pin "13") (pinfunction "I2_13") (pintype "input"))
      (node (ref "IC2") (pin "2") (pinfunction "I1_2") (pintype "input"))
      (node (ref "IC4") (pin "6") (pinfunction "O_6") (pintype "output"))
      (node (ref "IC5") (pin "10") (pinfunction "PRE_10") (pintype "input"))
      (node (ref "IC5") (pin "4") (pinfunction "PRE_4") (pintype "input"))
      (node (ref "IC6") (pin "13") (pinfunction "CLR_13") (pintype "input"))
      (node (ref "IC7") (pin "1") (pinfunction "CLR_1") (pintype "input"))
      (node (ref "IC7") (pin "13") (pinfunction "CLR_13") (pintype "input"))
      (node (ref "IC75") (pin "10") (pinfunction "PRE_10") (pintype "input"))
      (node (ref "IC75") (pin "4") (pinfunction "PRE_4") (pintype "input"))
    )
    (net (code "2") (name "+3V@B12U1") (class "Default")
      (node (ref "IC55") (pin "6") (pinfunction "O_6") (pintype "output"))
      (node (ref "IC73") (pin "10") (pinfunction "PRE_10") (pintype "input"))
      (node (ref "IC73") (pin "4") (pinfunction "PRE_4") (pintype "input"))
      (node (ref "IC74") (pin "4") (pinfunction "PRE_4") (pintype "input"))
      (node (ref "IC76") (pin "1") (pinfunction "CLR_1") (pintype "input"))
      (node (ref "IC76") (pin "10") (pinfunction "PRE_10") (pintype "input"))
      (node (ref "IC76") (pin "13") (pinfunction "CLR_13") (pintype "input"))
      (node (ref "IC77") (pin "1") (pinfunction "CLR_1") (pintype "input"))
      (node (ref "IC77") (pin "10") (pinfunction "PRE_10") (pintype "input"))
      (node (ref "IC77") (pin "13") (pinfunction "CLR_13") (pintype "input"))
      (node (ref "IC77") (pin "4") (pinfunction "PRE_4") (pintype "input"))
    )
    (net (code "3") (name "+3V@C08U1") (class "Default")
      (node (ref "IC79") (pin "1") (pinfunction "I0_1") (pintype "input"))
      (node (ref "IC79") (pin "12") (pinfunction "I0_12") (pintype "input"))
      (node (ref "IC79") (pin "4") (pinfunction "I0_4") (pintype "input"))
      (node (ref "IC79") (pin "9") (pinfunction "I0_9") (pintype "input"))
      (node (ref "IC80") (pin "1") (pinfunction "I0_1") (pintype "input"))
      (node (ref "IC80") (pin "12") (pinfunction "I0_12") (pintype "input"))
      (node (ref "IC80") (pin "4") (pinfunction "I0_4") (pintype "input"))
      (node (ref "IC80") (pin "9") (pinfunction "I0_9") (pintype "input"))
      (node (ref "IC81") (pin "1") (pinfunction "I0_1") (pintype "input"))
      (node (ref "IC81") (pin "12") (pinfunction "I0_12") (pintype "input"))
      (node (ref "IC81") (pin "4") (pinfunction "I0_4") (pintype "input"))
      (node (ref "IC81") (pin "9") (pinfunction "I0_9") (pintype "input"))
      (node (ref "IC82") (pin "1") (pinfunction "I0_1") (pintype "input"))
      (node (ref "IC82") (pin "12") (pinfunction "I0_12") (pintype "input"))
      (node (ref "IC82") (pin "4") (pinfunction "I0_4") (pintype "input"))
      (node (ref "IC82") (pin "9") (pinfunction "I0_9") (pintype "input"))
      (node (ref "IC86") (pin "11") (pinfunction "I6_11") (pintype "input"))
      (node (ref "IC86") (pin "12") (pinfunction "I7_12") (pintype "input"))
      (node (ref "IC87") (pin "2") (pinfunction "I1_2") (pintype "input"))
      (node (ref "IC88") (pin "2") (pinfunction "I1_2") (pintype "input"))
      (node (ref "IC88") (pin "5") (pinfunction "I1_5") (pintype "input"))
      (node (ref "IC89") (pin "11") (pinfunction "I6_11") (pintype "input"))
      (node (ref "IC89") (pin "12") (pinfunction "I7_12") (pintype "input"))
      (node (ref "IC90") (pin "5") (pinfunction "I1_5") (pintype "input"))
      (node (ref "IC99") (pin "2") (pinfunction "O_2") (pintype "output"))
    )
    (net (code "4") (name "+3V@C15U1") (class "Default")
      (node (ref "IC112") (pin "8") (pinfunction "O_8") (pintype "output"))
      (node (ref "IC113") (pin "1") (pinfunction "CLR_1") (pintype "input"))
      (node (ref "IC113") (pin "10") (pinfunction "PRE_10") (pintype "input"))
      (node (ref "IC113") (pin "13") (pinfunction "CLR_13") (pintype "input"))
      (node (ref "IC113") (pin "4") (pinfunction "PRE_4") (pintype "input"))
      (node (ref "IC114") (pin "1") (pinfunction "CLR_1") (pintype "input"))
      (node (ref "IC114") (pin "13") (pinfunction "CLR_13") (pintype "input"))
      (node (ref "IC114") (pin "4") (pinfunction "PRE_4") (pintype "input"))
      (node (ref "IC115") (pin "1") (pinfunction "CLR_1") (pintype "input"))
      (node (ref "IC120") (pin "5") (pinfunction "I3_5") (pintype "input"))
    )
    (net (code "5") (name "+3V@D09U1") (class "Default")
      (node (ref "IC110") (pin "10") (pinfunction "I1_10") (pintype "input"))
      (node (ref "IC110") (pin "11") (pinfunction "I2_11") (pintype "input"))
      (node (ref "IC110") (pin "9") (pinfunction "I0_9") (pintype "input"))
      (node (ref "IC132") (pin "2") (pinfunction "O_2") (pintype "output"))
    )
    (net (code "6") (name "+3V@D10U1") (class "Default")
      (node (ref "IC115") (pin "10") (pinfunction "PRE_10") (pintype "input"))
      (node (ref "IC132") (pin "4") (pinfunction "O_4") (pintype "output"))
      (node (ref "IC134") (pin "11") (pinfunction "I6_11") (pintype "input"))
      (node (ref "IC134") (pin "12") (pinfunction "I7_12") (pintype "input"))
      (node (ref "IC134") (pin "6") (pinfunction "I5_6") (pintype "input"))
      (node (ref "IC136") (pin "10") (pinfunction "PRE_10") (pintype "input"))
      (node (ref "IC136") (pin "4") (pinfunction "PRE_4") (pintype "input"))
      (node (ref "IC137") (pin "1") (pinfunction "CLR_1") (pintype "input"))
      (node (ref "IC137") (pin "13") (pinfunction "CLR_13") (pintype "input"))
      (node (ref "IC138") (pin "1") (pinfunction "CLR_1") (pintype "input"))
      (node (ref "M916_20") (pin "M1") (pinfunction "P$2_M1") (pintype "bidirectional"))
    )
    (net (code "7") (name "-15V") (class "Default")
      (node (ref "M916_13") (pin "B2") (pinfunction "P$2_B2") (pintype "bidirectional"))
      (node (ref "M916_14") (pin "B2") (pinfunction "P$2_B2") (pintype "bidirectional"))
      (node (ref "M916_15") (pin "B2") (pinfunction "P$2_B2") (pintype "bidirectional"))
      (node (ref "M916_16") (pin "B2") (pinfunction "P$2_B2") (pintype "bidirectional"))
      (node (ref "M916_17") (pin "B2") (pinfunction "P$2_B2") (pintype "bidirectional"))
      (node (ref "M916_3") (pin "B2") (pinfunction "P$2_B2") (pintype "bidirectional"))
      (node (ref "M916_4") (pin "B2") (pinfunction "P$2_B2") (pintype "bidirectional"))
      (node (ref "M916_5") (pin "B2") (pinfunction "P$2_B2") (pintype "bidirectional"))
      (node (ref "M916_6") (pin "B2") (pinfunction "P$2_B2") (pintype "bidirectional"))
      (node (ref "M916_7") (pin "B2") (pinfunction "P$2_B2") (pintype "bidirectional"))
    )
    (net (code "8") (name "00") (class "Default")
      (node (ref "IC3") (pin "2") (pinfunction "O_2") (pintype "output"))
    )
    (net (code "9") (name "0_TO_DTB") (class "Default")
      (node (ref "IC107") (pin "5") (pinfunction "I1_5") (pintype "input"))
    )
    (net (code "10") (name "0_TO_EF") (class "Default")
      (node (ref "IC12") (pin "3") (pinfunction "O_3") (pintype "output"))
      (node (ref "IC14") (pin "3") (pinfunction "I_3") (pintype "input"))
    )
    (net (code "11") (name "0_TO_STA") (class "Default")
      (node (ref "IC12") (pin "8") (pinfunction "O_8") (pintype "output"))
      (node (ref "IC14") (pin "13") (pinfunction "I_13") (pintype "input"))
    )
    (net (code "12") (name "01") (class "Default")
      (node (ref "IC3") (pin "4") (pinfunction "O_4") (pintype "output"))
    )
    (net (code "13") (name "1_TO_DF") (class "Default")
      (node (ref "IC108") (pin "10") (pinfunction "I1_10") (pintype "input"))
      (node (ref "IC108") (pin "6") (pinfunction "O_6") (pintype "output"))
      (node (ref "IC137") (pin "3") (pinfunction "CLK_3") (pintype "input"))
      (node (ref "IC6") (pin "3") (pinfunction "CLK_3") (pintype "input"))
    )
    (net (code "14") (name "1_TO_DTF") (class "Default")
      (node (ref "IC138") (pin "3") (pinfunction "CLK_3") (pintype "input"))
      (node (ref "IC72") (pin "6") (pinfunction "O_6") (pintype "output"))
    )
    (net (code "15") (name "02") (class "Default")
      (node (ref "IC3") (pin "6") (pinfunction "O_6") (pintype "output"))
    )
    (net (code "16") (name "03") (class "Default")
      (node (ref "IC3") (pin "8") (pinfunction "O_8") (pintype "output"))
    )
    (net (code "17") (name "04") (class "Default")
      (node (ref "IC3") (pin "10") (pinfunction "O_10") (pintype "output"))
    )
    (net (code "18") (name "05") (class "Default")
      (node (ref "IC3") (pin "12") (pinfunction "O_12") (pintype "output"))
    )
    (net (code "19") (name "06") (class "Default")
      (node (ref "IC4") (pin "2") (pinfunction "O_2") (pintype "output"))
    )
    (net (code "20") (name "07") (class "Default")
      (node (ref "IC4") (pin "4") (pinfunction "O_4") (pintype "output"))
    )
    (net (code "21") (name "76") (class "Default")
      (node (ref "IC87") (pin "12") (pinfunction "I0_12") (pintype "input"))
      (node (ref "IC87") (pin "3") (pinfunction "O_3") (pintype "output"))
      (node (ref "IC87") (pin "4") (pinfunction "I0_4") (pintype "input"))
      (node (ref "IC87") (pin "9") (pinfunction "I0_9") (pintype "input"))
      (node (ref "IC93") (pin "11") (pinfunction "I_11") (pintype "input"))
    )
    (net (code "22") (name "76+77") (class "Default")
      (node (ref "IC141") (pin "6") (pinfunction "O_6") (pintype "output"))
      (node (ref "IC83") (pin "1") (pinfunction "I0_1") (pintype "input"))
      (node (ref "IC83") (pin "12") (pinfunction "I0_12") (pintype "input"))
      (node (ref "IC83") (pin "4") (pinfunction "I0_4") (pintype "input"))
      (node (ref "IC83") (pin "9") (pinfunction "I0_9") (pintype "input"))
      (node (ref "IC84") (pin "1") (pinfunction "I0_1") (pintype "input"))
      (node (ref "IC84") (pin "12") (pinfunction "I0_12") (pintype "input"))
      (node (ref "IC84") (pin "4") (pinfunction "I0_4") (pintype "input"))
      (node (ref "IC84") (pin "9") (pinfunction "I0_9") (pintype "input"))
      (node (ref "IC85") (pin "1") (pinfunction "I0_1") (pintype "input"))
      (node (ref "IC85") (pin "12") (pinfunction "I0_12") (pintype "input"))
      (node (ref "IC85") (pin "4") (pinfunction "I0_4") (pintype "input"))
      (node (ref "IC85") (pin "9") (pinfunction "I0_9") (pintype "input"))
    )
    (net (code "23") (name "76_") (class "Default")
      (node (ref "IC86") (pin "8") (pinfunction "O_8") (pintype "output"))
      (node (ref "IC87") (pin "1") (pinfunction "I0_1") (pintype "input"))
    )
    (net (code "24") (name "77") (class "Default")
      (node (ref "IC88") (pin "12") (pinfunction "I0_12") (pintype "input"))
      (node (ref "IC88") (pin "6") (pinfunction "O_6") (pintype "output"))
      (node (ref "IC88") (pin "9") (pinfunction "I0_9") (pintype "input"))
      (node (ref "IC90") (pin "1") (pinfunction "I0_1") (pintype "input"))
      (node (ref "IC93") (pin "13") (pinfunction "I_13") (pintype "input"))
    )
    (net (code "25") (name "77_") (class "Default")
      (node (ref "IC88") (pin "4") (pinfunction "I0_4") (pintype "input"))
      (node (ref "IC89") (pin "8") (pinfunction "O_8") (pintype "output"))
    )
    (net (code "26") (name "ADDR_ACC") (class "Default")
      (node (ref "IC122") (pin "11") (pinfunction "I_11") (pintype "input"))
      (node (ref "IC82") (pin "11") (pinfunction "O_11") (pintype "output"))
    )
    (net (code "27") (name "B-BRK") (class "Default")
      (node (ref "IC139") (pin "9") (pinfunction "I0_9") (pintype "input"))
      (node (ref "IC67") (pin "1") (pinfunction "I0_1") (pintype "input"))
      (node (ref "IC67") (pin "2") (pinfunction "I1_2") (pintype "input"))
      (node (ref "IC67") (pin "4") (pinfunction "I2_4") (pintype "input"))
      (node (ref "IC67") (pin "5") (pinfunction "I3_5") (pintype "input"))
      (node (ref "IC79") (pin "6") (pinfunction "O_6") (pintype "output"))
    )
    (net (code "28") (name "B-RUN") (class "Default")
      (node (ref "IC69") (pin "3") (pinfunction "I0_3") (pintype "input"))
      (node (ref "IC79") (pin "3") (pinfunction "O_3") (pintype "output"))
    )
    (net (code "29") (name "B-XSTA") (class "Default")
      (node (ref "IC107") (pin "9") (pinfunction "I0_9") (pintype "input"))
      (node (ref "IC11") (pin "10") (pinfunction "I1_10") (pintype "input"))
      (node (ref "IC121") (pin "8") (pinfunction "O_8") (pintype "output"))
    )
    (net (code "30") (name "BAC_00") (class "Default")
      (node (ref "IC53") (pin "2") (pinfunction "O_2") (pintype "output"))
      (node (ref "IC56") (pin "14") (pinfunction "J_14") (pintype "input"))
      (node (ref "IC56") (pin "3") (pinfunction "K_3") (pintype "input"))
    )
    (net (code "31") (name "BAC_01") (class "Default")
      (node (ref "IC53") (pin "6") (pinfunction "O_6") (pintype "output"))
      (node (ref "IC56") (pin "10") (pinfunction "K_10") (pintype "input"))
      (node (ref "IC56") (pin "7") (pinfunction "J_7") (pintype "input"))
    )
    (net (code "32") (name "BAC_02") (class "Default")
      (node (ref "IC53") (pin "8") (pinfunction "O_8") (pintype "output"))
      (node (ref "IC57") (pin "14") (pinfunction "J_14") (pintype "input"))
      (node (ref "IC57") (pin "3") (pinfunction "K_3") (pintype "input"))
    )
    (net (code "33") (name "BAC_03") (class "Default")
      (node (ref "IC53") (pin "12") (pinfunction "O_12") (pintype "output"))
      (node (ref "IC57") (pin "10") (pinfunction "K_10") (pintype "input"))
      (node (ref "IC57") (pin "7") (pinfunction "J_7") (pintype "input"))
    )
    (net (code "34") (name "BAC_04") (class "Default")
      (node (ref "IC95") (pin "10") (pinfunction "K_10") (pintype "input"))
      (node (ref "IC95") (pin "7") (pinfunction "J_7") (pintype "input"))
    )
    (net (code "35") (name "BAC_05") (class "Default")
      (node (ref "IC54") (pin "6") (pinfunction "O_6") (pintype "output"))
      (node (ref "IC58") (pin "14") (pinfunction "J_14") (pintype "input"))
      (node (ref "IC58") (pin "3") (pinfunction "K_3") (pintype "input"))
    )
    (net (code "36") (name "BAC_06") (class "Default")
      (node (ref "IC115") (pin "12") (pinfunction "D_12") (pintype "input"))
      (node (ref "IC54") (pin "8") (pinfunction "O_8") (pintype "output"))
      (node (ref "IC58") (pin "10") (pinfunction "K_10") (pintype "input"))
      (node (ref "IC58") (pin "7") (pinfunction "J_7") (pintype "input"))
    )
    (net (code "37") (name "BAC_07") (class "Default")
      (node (ref "IC136") (pin "2") (pinfunction "D_2") (pintype "input"))
      (node (ref "IC54") (pin "12") (pinfunction "O_12") (pintype "output"))
      (node (ref "IC94") (pin "14") (pinfunction "J_14") (pintype "input"))
      (node (ref "IC94") (pin "3") (pinfunction "K_3") (pintype "input"))
    )
    (net (code "38") (name "BAC_08") (class "Default")
      (node (ref "IC136") (pin "12") (pinfunction "D_12") (pintype "input"))
      (node (ref "IC53") (pin "4") (pinfunction "O_4") (pintype "output"))
      (node (ref "IC94") (pin "10") (pinfunction "K_10") (pintype "input"))
      (node (ref "IC94") (pin "7") (pinfunction "J_7") (pintype "input"))
    )
    (net (code "39") (name "BAC_09") (class "Default")
      (node (ref "IC53") (pin "10") (pinfunction "O_10") (pintype "output"))
      (node (ref "IC95") (pin "14") (pinfunction "J_14") (pintype "input"))
      (node (ref "IC95") (pin "3") (pinfunction "K_3") (pintype "input"))
    )
    (net (code "40") (name "BAC_10") (class "Default")
      (node (ref "IC54") (pin "2") (pinfunction "O_2") (pintype "output"))
    )
    (net (code "41") (name "BAC_11") (class "Default")
      (node (ref "IC54") (pin "4") (pinfunction "O_4") (pintype "output"))
    )
    (net (code "42") (name "BLK_IN_SYNC") (class "Default")
      (node (ref "IC106") (pin "2") (pinfunction "I1_2") (pintype "input"))
      (node (ref "IC111") (pin "12") (pinfunction "O_12") (pintype "output"))
    )
    (net (code "43") (name "BMB_00") (class "Default")
      (node (ref "IC91") (pin "8") (pinfunction "O_8") (pintype "output"))
      (node (ref "IC96") (pin "3") (pinfunction "2B_3") (pintype "input"))
    )
    (net (code "44") (name "BMB_01") (class "Default")
      (node (ref "IC91") (pin "12") (pinfunction "O_12") (pintype "output"))
      (node (ref "IC98") (pin "12") (pinfunction "1B_12") (pintype "input"))
    )
    (net (code "45") (name "BMB_02") (class "Default")
      (node (ref "IC92") (pin "2") (pinfunction "O_2") (pintype "output"))
      (node (ref "IC97") (pin "3") (pinfunction "2B_3") (pintype "input"))
    )
    (net (code "46") (name "BMB_03") (class "Default")
      (node (ref "IC92") (pin "6") (pinfunction "O_6") (pintype "output"))
      (node (ref "IC96") (pin "12") (pinfunction "1B_12") (pintype "input"))
    )
    (net (code "47") (name "BMB_04") (class "Default")
      (node (ref "IC97") (pin "12") (pinfunction "1B_12") (pintype "input"))
    )
    (net (code "48") (name "BMB_05") (class "Default")
      (node (ref "IC92") (pin "12") (pinfunction "O_12") (pintype "output"))
      (node (ref "IC98") (pin "3") (pinfunction "2B_3") (pintype "input"))
    )
    (net (code "49") (name "BMB_06") (class "Default")
      (node (ref "IC59") (pin "2") (pinfunction "I1_2") (pintype "input"))
      (node (ref "IC93") (pin "4") (pinfunction "O_4") (pintype "output"))
    )
    (net (code "50") (name "BMB_07") (class "Default")
      (node (ref "IC59") (pin "5") (pinfunction "I1_5") (pintype "input"))
      (node (ref "IC93") (pin "8") (pinfunction "O_8") (pintype "output"))
    )
    (net (code "51") (name "BMB_08") (class "Default")
      (node (ref "IC59") (pin "10") (pinfunction "I1_10") (pintype "input"))
      (node (ref "IC91") (pin "10") (pinfunction "O_10") (pintype "output"))
    )
    (net (code "52") (name "BMB_09") (class "Default")
      (node (ref "IC60") (pin "5") (pinfunction "I1_5") (pintype "input"))
      (node (ref "IC92") (pin "4") (pinfunction "O_4") (pintype "output"))
    )
    (net (code "53") (name "BMB_10") (class "Default")
      (node (ref "IC60") (pin "13") (pinfunction "I1_13") (pintype "input"))
      (node (ref "IC92") (pin "8") (pinfunction "O_8") (pintype "output"))
    )
    (net (code "54") (name "BMB_11") (class "Default")
      (node (ref "IC59") (pin "13") (pinfunction "I1_13") (pintype "input"))
      (node (ref "IC92") (pin "10") (pinfunction "O_10") (pintype "output"))
    )
    (net (code "55") (name "BMB_TO_DTB") (class "Default")
      (node (ref "IC139") (pin "6") (pinfunction "O_6") (pintype "output"))
      (node (ref "IC59") (pin "1") (pinfunction "I0_1") (pintype "input"))
      (node (ref "IC59") (pin "12") (pinfunction "I0_12") (pintype "input"))
      (node (ref "IC59") (pin "4") (pinfunction "I0_4") (pintype "input"))
      (node (ref "IC59") (pin "9") (pinfunction "I0_9") (pintype "input"))
      (node (ref "IC60") (pin "12") (pinfunction "I0_12") (pintype "input"))
      (node (ref "IC60") (pin "4") (pinfunction "I0_4") (pintype "input"))
      (node (ref "IC96") (pin "1") (pinfunction "1A_1") (pintype "input"))
      (node (ref "IC96") (pin "2") (pinfunction "2A_2") (pintype "input"))
      (node (ref "IC97") (pin "1") (pinfunction "1A_1") (pintype "input"))
      (node (ref "IC97") (pin "2") (pinfunction "2A_2") (pintype "input"))
      (node (ref "IC98") (pin "1") (pinfunction "1A_1") (pintype "input"))
      (node (ref "IC98") (pin "2") (pinfunction "2A_2") (pintype "input"))
    )
    (net (code "56") (name "BMR00") (class "Default")
      (node (ref "IC76") (pin "9") (pinfunction "Q_9") (pintype "output"))
      (node (ref "M916_7") (pin "F1") (pinfunction "P$2_F1") (pintype "bidirectional"))
    )
    (net (code "57") (name "BMR01") (class "Default")
      (node (ref "IC76") (pin "6") (pinfunction "~{Q}_6") (pintype "output"))
      (node (ref "M916_7") (pin "B1") (pinfunction "P$2_B1") (pintype "bidirectional"))
    )
    (net (code "58") (name "C00") (class "Default")
      (node (ref "IC116") (pin "10") (pinfunction "I1_10") (pintype "input"))
      (node (ref "IC133") (pin "3") (pinfunction "I2_3") (pintype "input"))
      (node (ref "IC17") (pin "1") (pinfunction "I0_1") (pintype "input"))
      (node (ref "IC72") (pin "9") (pinfunction "I0_9") (pintype "input"))
      (node (ref "IC75") (pin "5") (pinfunction "Q_5") (pintype "output"))
      (node (ref "M916_10") (pin "E2") (pinfunction "P$2_E2") (pintype "bidirectional"))
    )
    (net (code "59") (name "C01") (class "Default")
      (node (ref "IC17") (pin "2") (pinfunction "I1_2") (pintype "input"))
      (node (ref "IC65") (pin "12") (pinfunction "I2_12") (pintype "input"))
      (node (ref "IC69") (pin "11") (pinfunction "I2_11") (pintype "input"))
      (node (ref "IC74") (pin "9") (pinfunction "Q_9") (pintype "output"))
      (node (ref "M916_10") (pin "F2") (pinfunction "P$2_F2") (pintype "bidirectional"))
    )
    (net (code "60") (name "CK00") (class "Default")
      (node (ref "IC77") (pin "5") (pinfunction "Q_5") (pintype "output"))
      (node (ref "M916_3") (pin "P2") (pinfunction "P$2_P2") (pintype "bidirectional"))
    )
    (net (code "61") (name "CK01") (class "Default")
      (node (ref "IC119") (pin "10") (pinfunction "I1_10") (pintype "input"))
      (node (ref "IC119") (pin "12") (pinfunction "I2_12") (pintype "input"))
      (node (ref "IC119") (pin "13") (pinfunction "I3_13") (pintype "input"))
      (node (ref "IC77") (pin "2") (pinfunction "D_2") (pintype "input"))
      (node (ref "IC77") (pin "9") (pinfunction "Q_9") (pintype "output"))
    )
    (net (code "62") (name "COMP+SH") (class "Default")
      (node (ref "IC113") (pin "11") (pinfunction "CLK_11") (pintype "input"))
      (node (ref "IC113") (pin "3") (pinfunction "CLK_3") (pintype "input"))
      (node (ref "IC114") (pin "3") (pinfunction "CLK_3") (pintype "input"))
      (node (ref "IC116") (pin "11") (pinfunction "O_11") (pintype "output"))
      (node (ref "IC16") (pin "1") (pinfunction "I0_1") (pintype "input"))
    )
    (net (code "63") (name "CSTA") (class "Default")
      (node (ref "IC55") (pin "10") (pinfunction "O_10") (pintype "output"))
      (node (ref "M916_22") (pin "P2") (pinfunction "P$2_P2") (pintype "bidirectional"))
    )
    (net (code "64") (name "DATA") (class "Default")
      (node (ref "IC99") (pin "11") (pinfunction "I_11") (pintype "input"))
      (node (ref "M916_10") (pin "M1") (pinfunction "P$2_M1") (pintype "bidirectional"))
    )
    (net (code "65") (name "DF") (class "Default")
      (node (ref "IC13") (pin "1") (pinfunction "I0_1") (pintype "input"))
      (node (ref "IC137") (pin "6") (pinfunction "~{Q}_6") (pintype "output"))
      (node (ref "M916_10") (pin "E1") (pinfunction "P$2_E1") (pintype "bidirectional"))
    )
    (net (code "66") (name "DTB_00") (class "Default")
      (node (ref "IC100") (pin "5") (pinfunction "Q_5") (pintype "output"))
      (node (ref "IC103") (pin "3") (pinfunction "2B_3") (pintype "input"))
      (node (ref "IC129") (pin "1") (pinfunction "1A_1") (pintype "input"))
      (node (ref "M916_9") (pin "A2") (pinfunction "P$2_A2") (pintype "bidirectional"))
    )
    (net (code "67") (name "DTB_01") (class "Default")
      (node (ref "IC100") (pin "9") (pinfunction "Q_9") (pintype "output"))
      (node (ref "IC105") (pin "12") (pinfunction "1B_12") (pintype "input"))
      (node (ref "IC130") (pin "1") (pinfunction "1A_1") (pintype "input"))
      (node (ref "M916_9") (pin "B2") (pinfunction "P$2_B2") (pintype "bidirectional"))
    )
    (net (code "68") (name "DTB_02") (class "Default")
      (node (ref "IC101") (pin "5") (pinfunction "Q_5") (pintype "output"))
      (node (ref "IC104") (pin "3") (pinfunction "2B_3") (pintype "input"))
      (node (ref "IC131") (pin "2") (pinfunction "2A_2") (pintype "input"))
      (node (ref "M916_9") (pin "C2") (pinfunction "P$2_C2") (pintype "bidirectional"))
    )
    (net (code "69") (name "DTB_03") (class "Default")
      (node (ref "IC100") (pin "2") (pinfunction "D_2") (pintype "input"))
      (node (ref "IC101") (pin "9") (pinfunction "Q_9") (pintype "output"))
      (node (ref "M916_9") (pin "D2") (pinfunction "P$2_D2") (pintype "bidirectional"))
    )
    (net (code "70") (name "DTB_04") (class "Default")
      (node (ref "IC100") (pin "12") (pinfunction "D_12") (pintype "input"))
      (node (ref "IC102") (pin "5") (pinfunction "Q_5") (pintype "output"))
      (node (ref "M916_9") (pin "E2") (pinfunction "P$2_E2") (pintype "bidirectional"))
    )
    (net (code "71") (name "DTB_05") (class "Default")
      (node (ref "IC101") (pin "2") (pinfunction "D_2") (pintype "input"))
      (node (ref "IC102") (pin "9") (pinfunction "Q_9") (pintype "output"))
      (node (ref "M916_9") (pin "F2") (pinfunction "P$2_F2") (pintype "bidirectional"))
    )
    (net (code "72") (name "DTB_06") (class "Default")
      (node (ref "IC101") (pin "12") (pinfunction "D_12") (pintype "input"))
      (node (ref "IC62") (pin "5") (pinfunction "Q_5") (pintype "output"))
      (node (ref "M916_9") (pin "H2") (pinfunction "P$2_H2") (pintype "bidirectional"))
    )
    (net (code "73") (name "DTB_07") (class "Default")
      (node (ref "IC102") (pin "2") (pinfunction "D_2") (pintype "input"))
      (node (ref "IC64") (pin "9") (pinfunction "Q_9") (pintype "output"))
      (node (ref "M916_9") (pin "J2") (pinfunction "P$2_J2") (pintype "bidirectional"))
    )
    (net (code "74") (name "DTB_08") (class "Default")
      (node (ref "IC102") (pin "12") (pinfunction "D_12") (pintype "input"))
      (node (ref "IC63") (pin "5") (pinfunction "Q_5") (pintype "output"))
      (node (ref "M916_9") (pin "K2") (pinfunction "P$2_K2") (pintype "bidirectional"))
    )
    (net (code "75") (name "DTB_09") (class "Default")
      (node (ref "IC62") (pin "2") (pinfunction "D_2") (pintype "input"))
      (node (ref "IC63") (pin "9") (pinfunction "Q_9") (pintype "output"))
      (node (ref "M916_9") (pin "L2") (pinfunction "P$2_L2") (pintype "bidirectional"))
    )
    (net (code "76") (name "DTB_10") (class "Default")
      (node (ref "IC64") (pin "12") (pinfunction "D_12") (pintype "input"))
      (node (ref "IC64") (pin "5") (pinfunction "Q_5") (pintype "output"))
      (node (ref "M916_9") (pin "M2") (pinfunction "P$2_M2") (pintype "bidirectional"))
    )
    (net (code "77") (name "DTB_11") (class "Default")
      (node (ref "IC62") (pin "9") (pinfunction "Q_9") (pintype "output"))
      (node (ref "IC63") (pin "2") (pinfunction "D_2") (pintype "input"))
      (node (ref "M916_9") (pin "N2") (pinfunction "P$2_N2") (pintype "bidirectional"))
    )
    (net (code "78") (name "DTF") (class "Default")
      (node (ref "IC138") (pin "6") (pinfunction "~{Q}_6") (pintype "output"))
      (node (ref "IC16") (pin "13") (pinfunction "I1_13") (pintype "input"))
      (node (ref "IC6") (pin "2") (pinfunction "D_2") (pintype "input"))
      (node (ref "M916_10") (pin "C1") (pinfunction "P$2_C1") (pintype "bidirectional"))
    )
    (net (code "79") (name "DTSF") (class "Default")
      (node (ref "IC17") (pin "5") (pinfunction "I1_5") (pintype "input"))
      (node (ref "IC91") (pin "2") (pinfunction "O_2") (pintype "output"))
    )
    (net (code "80") (name "EF") (class "Default")
      (node (ref "IC13") (pin "11") (pinfunction "O_11") (pintype "output"))
      (node (ref "IC14") (pin "5") (pinfunction "I_5") (pintype "input"))
      (node (ref "IC16") (pin "12") (pinfunction "I0_12") (pintype "input"))
      (node (ref "M916_9") (pin "N1") (pinfunction "P$2_N1") (pintype "bidirectional"))
    )
    (net (code "81") (name "END") (class "Default")
      (node (ref "IC5") (pin "5") (pinfunction "Q_5") (pintype "output"))
      (node (ref "M916_9") (pin "R1") (pinfunction "P$2_R1") (pintype "bidirectional"))
    )
    (net (code "82") (name "ENI") (class "Default")
      (node (ref "IC16") (pin "4") (pinfunction "I0_4") (pintype "input"))
      (node (ref "IC95") (pin "12") (pinfunction "Q_12") (pintype "output"))
      (node (ref "M916_9") (pin "L1") (pinfunction "P$2_L1") (pintype "bidirectional"))
    )
    (net (code "83") (name "FR_00") (class "Default")
      (node (ref "IC110") (pin "4") (pinfunction "I1_4") (pintype "input"))
      (node (ref "IC58") (pin "12") (pinfunction "Q_12") (pintype "output"))
      (node (ref "IC71") (pin "10") (pinfunction "I1_10") (pintype "input"))
      (node (ref "M916_9") (pin "F1") (pinfunction "P$2_F1") (pintype "bidirectional"))
    )
    (net (code "84") (name "FR_01") (class "Default")
      (node (ref "IC11") (pin "12") (pinfunction "I0_12") (pintype "input"))
      (node (ref "IC116") (pin "4") (pinfunction "I0_4") (pintype "input"))
      (node (ref "IC124") (pin "22") (pinfunction "B_22") (pintype "input"))
      (node (ref "IC139") (pin "13") (pinfunction "I3_13") (pintype "input"))
      (node (ref "IC58") (pin "9") (pinfunction "Q_9") (pintype "output"))
      (node (ref "IC78") (pin "5") (pinfunction "I1_5") (pintype "input"))
      (node (ref "M916_9") (pin "H1") (pinfunction "P$2_H1") (pintype "bidirectional"))
    )
    (net (code "85") (name "FR_02") (class "Default")
      (node (ref "IC124") (pin "21") (pinfunction "C_21") (pintype "input"))
      (node (ref "IC94") (pin "12") (pinfunction "Q_12") (pintype "output"))
      (node (ref "M916_9") (pin "J1") (pinfunction "P$2_J1") (pintype "bidirectional"))
    )
    (net (code "86") (name "FR_03") (class "Default")
      (node (ref "IC124") (pin "20") (pinfunction "D_20") (pintype "input"))
      (node (ref "IC78") (pin "13") (pinfunction "I1_13") (pintype "input"))
      (node (ref "IC94") (pin "9") (pinfunction "Q_9") (pintype "output"))
      (node (ref "M916_9") (pin "K1") (pinfunction "P$2_K1") (pintype "bidirectional"))
    )
    (net (code "87") (name "FR_03_") (class "Default")
      (node (ref "IC110") (pin "8") (pinfunction "O_8") (pintype "output"))
      (node (ref "IC124") (pin "18") (pinfunction "G1_18") (pintype "input"))
      (node (ref "IC124") (pin "19") (pinfunction "G2_19") (pintype "input"))
    )
    (net (code "88") (name "GND") (class "Default")
      (node (ref "IC1") (pin "23") (pinfunction "A_23") (pintype "input"))
      (node (ref "IC112") (pin "9") (pinfunction "I_9") (pintype "input"))
      (node (ref "IC124") (pin "23") (pinfunction "A_23") (pintype "input"))
      (node (ref "IC132") (pin "1") (pinfunction "I_1") (pintype "input"))
      (node (ref "IC132") (pin "3") (pinfunction "I_3") (pintype "input"))
      (node (ref "IC137") (pin "12") (pinfunction "D_12") (pintype "input"))
      (node (ref "IC138") (pin "2") (pinfunction "D_2") (pintype "input"))
      (node (ref "IC4") (pin "5") (pinfunction "I_5") (pintype "input"))
      (node (ref "IC45") (pin "12") (pinfunction "I1_12") (pintype "input"))
      (node (ref "IC45") (pin "3") (pinfunction "I1_3") (pintype "input"))
      (node (ref "IC45") (pin "6") (pinfunction "I1_6") (pintype "input"))
      (node (ref "IC45") (pin "9") (pinfunction "I1_9") (pintype "input"))
      (node (ref "IC46") (pin "12") (pinfunction "I1_12") (pintype "input"))
      (node (ref "IC46") (pin "3") (pinfunction "I1_3") (pintype "input"))
      (node (ref "IC46") (pin "6") (pinfunction "I1_6") (pintype "input"))
      (node (ref "IC46") (pin "9") (pinfunction "I1_9") (pintype "input"))
      (node (ref "IC47") (pin "3") (pinfunction "I1_3") (pintype "input"))
      (node (ref "IC55") (pin "3") (pinfunction "I_3") (pintype "input"))
      (node (ref "IC55") (pin "5") (pinfunction "I_5") (pintype "input"))
      (node (ref "IC7") (pin "12") (pinfunction "D_12") (pintype "input"))
      (node (ref "IC99") (pin "1") (pinfunction "I_1") (pintype "input"))
      (node (ref "M916_1") (pin "C2") (pinfunction "P$2_C2") (pintype "bidirectional"))
      (node (ref "M916_1") (pin "T1") (pinfunction "P$2_T1") (pintype "bidirectional"))
      (node (ref "M916_10") (pin "D2") (pinfunction "P$2_D2") (pintype "bidirectional"))
      (node (ref "M916_10") (pin "U2") (pinfunction "P$2_U2") (pintype "bidirectional"))
      (node (ref "M916_10") (pin "V1") (pinfunction "P$2_V1") (pintype "bidirectional"))
      (node (ref "M916_12") (pin "C2") (pinfunction "P$2_C2") (pintype "bidirectional"))
      (node (ref "M916_12") (pin "T1") (pinfunction "P$2_T1") (pintype "bidirectional"))
      (node (ref "M916_13") (pin "C2") (pinfunction "P$2_C2") (pintype "bidirectional"))
      (node (ref "M916_14") (pin "C2") (pinfunction "P$2_C2") (pintype "bidirectional"))
      (node (ref "M916_15") (pin "C2") (pinfunction "P$2_C2") (pintype "bidirectional"))
      (node (ref "M916_16") (pin "C2") (pinfunction "P$2_C2") (pintype "bidirectional"))
      (node (ref "M916_16") (pin "T1") (pinfunction "P$2_T1") (pintype "bidirectional"))
      (node (ref "M916_16") (pin "T2") (pinfunction "P$2_T2") (pintype "bidirectional"))
      (node (ref "M916_16") (pin "U1") (pinfunction "P$2_U1") (pintype "bidirectional"))
      (node (ref "M916_16") (pin "V1") (pinfunction "P$2_V1") (pintype "bidirectional"))
      (node (ref "M916_17") (pin "C2") (pinfunction "P$2_C2") (pintype "bidirectional"))
      (node (ref "M916_19") (pin "C2") (pinfunction "P$2_C2") (pintype "bidirectional"))
      (node (ref "M916_19") (pin "T1") (pinfunction "P$2_T1") (pintype "bidirectional"))
      (node (ref "M916_2") (pin "C2") (pinfunction "P$2_C2") (pintype "bidirectional"))
      (node (ref "M916_2") (pin "T1") (pinfunction "P$2_T1") (pintype "bidirectional"))
      (node (ref "M916_20") (pin "C2") (pinfunction "P$2_C2") (pintype "bidirectional"))
      (node (ref "M916_20") (pin "T1") (pinfunction "P$2_T1") (pintype "bidirectional"))
      (node (ref "M916_21") (pin "C2") (pinfunction "P$2_C2") (pintype "bidirectional"))
      (node (ref "M916_21") (pin "T1") (pinfunction "P$2_T1") (pintype "bidirectional"))
      (node (ref "M916_22") (pin "C2") (pinfunction "P$2_C2") (pintype "bidirectional"))
      (node (ref "M916_22") (pin "T1") (pinfunction "P$2_T1") (pintype "bidirectional"))
      (node (ref "M916_23") (pin "C2") (pinfunction "P$2_C2") (pintype "bidirectional"))
      (node (ref "M916_23") (pin "T1") (pinfunction "P$2_T1") (pintype "bidirectional"))
      (node (ref "M916_3") (pin "C2") (pinfunction "P$2_C2") (pintype "bidirectional"))
      (node (ref "M916_4") (pin "C2") (pinfunction "P$2_C2") (pintype "bidirectional"))
      (node (ref "M916_5") (pin "C2") (pinfunction "P$2_C2") (pintype "bidirectional"))
      (node (ref "M916_6") (pin "C2") (pinfunction "P$2_C2") (pintype "bidirectional"))
      (node (ref "M916_6") (pin "M2") (pinfunction "P$2_M2") (pintype "bidirectional"))
      (node (ref "M916_7") (pin "C1") (pinfunction "P$2_C1") (pintype "bidirectional"))
      (node (ref "M916_7") (pin "C2") (pinfunction "P$2_C2") (pintype "bidirectional"))
      (node (ref "M916_7") (pin "F2") (pinfunction "P$2_F2") (pintype "bidirectional"))
      (node (ref "M916_7") (pin "J1") (pinfunction "P$2_J1") (pintype "bidirectional"))
      (node (ref "M916_7") (pin "M2") (pinfunction "P$2_M2") (pintype "bidirectional"))
      (node (ref "M916_7") (pin "P1") (pinfunction "P$2_P1") (pintype "bidirectional"))
      (node (ref "M916_7") (pin "T1") (pinfunction "P$2_T1") (pintype "bidirectional"))
      (node (ref "M916_7") (pin "T2") (pinfunction "P$2_T2") (pintype "bidirectional"))
      (node (ref "M916_7") (pin "U1") (pinfunction "P$2_U1") (pintype "bidirectional"))
      (node (ref "M916_7") (pin "V1") (pinfunction "P$2_V1") (pintype "bidirectional"))
      (node (ref "M916_9") (pin "M1") (pinfunction "P$2_M1") (pintype "bidirectional"))
      (node (ref "SV1") (pin "A") (pinfunction "1_A") (pintype "bidirectional"))
      (node (ref "SV1") (pin "AA") (pinfunction "23_AA") (pintype "bidirectional"))
      (node (ref "SV1") (pin "B") (pinfunction "2_B") (pintype "bidirectional"))
      (node (ref "SV1") (pin "C") (pinfunction "3_C") (pintype "bidirectional"))
      (node (ref "SV1") (pin "CC") (pinfunction "25_CC") (pintype "bidirectional"))
      (node (ref "SV1") (pin "E") (pinfunction "5_E") (pintype "bidirectional"))
      (node (ref "SV1") (pin "EE") (pinfunction "27_EE") (pintype "bidirectional"))
      (node (ref "SV1") (pin "H") (pinfunction "7_H") (pintype "bidirectional"))
      (node (ref "SV1") (pin "HH") (pinfunction "29_HH") (pintype "bidirectional"))
      (node (ref "SV1") (pin "K") (pinfunction "9_K") (pintype "bidirectional"))
      (node (ref "SV1") (pin "KK") (pinfunction "31_KK") (pintype "bidirectional"))
      (node (ref "SV1") (pin "M") (pinfunction "11_M") (pintype "bidirectional"))
      (node (ref "SV1") (pin "MM") (pinfunction "33_MM") (pintype "bidirectional"))
      (node (ref "SV1") (pin "P") (pinfunction "13_P") (pintype "bidirectional"))
      (node (ref "SV1") (pin "PP") (pinfunction "35_PP") (pintype "bidirectional"))
      (node (ref "SV1") (pin "S") (pinfunction "15_S") (pintype "bidirectional"))
      (node (ref "SV1") (pin "SS") (pinfunction "37_SS") (pintype "bidirectional"))
      (node (ref "SV1") (pin "U") (pinfunction "17_U") (pintype "bidirectional"))
      (node (ref "SV1") (pin "UU") (pinfunction "39_UU") (pintype "bidirectional"))
      (node (ref "SV1") (pin "VV") (pinfunction "40_VV") (pintype "bidirectional"))
      (node (ref "SV1") (pin "W") (pinfunction "19_W") (pintype "bidirectional"))
      (node (ref "SV1") (pin "Y") (pinfunction "21_Y") (pintype "bidirectional"))
      (node (ref "SV10") (pin "A") (pinfunction "1_A") (pintype "bidirectional"))
      (node (ref "SV10") (pin "AA") (pinfunction "23_AA") (pintype "bidirectional"))
      (node (ref "SV10") (pin "B") (pinfunction "2_B") (pintype "bidirectional"))
      (node (ref "SV10") (pin "C") (pinfunction "3_C") (pintype "bidirectional"))
      (node (ref "SV10") (pin "CC") (pinfunction "25_CC") (pintype "bidirectional"))
      (node (ref "SV10") (pin "E") (pinfunction "5_E") (pintype "bidirectional"))
      (node (ref "SV10") (pin "EE") (pinfunction "27_EE") (pintype "bidirectional"))
      (node (ref "SV10") (pin "H") (pinfunction "7_H") (pintype "bidirectional"))
      (node (ref "SV10") (pin "HH") (pinfunction "29_HH") (pintype "bidirectional"))
      (node (ref "SV10") (pin "K") (pinfunction "9_K") (pintype "bidirectional"))
      (node (ref "SV10") (pin "KK") (pinfunction "31_KK") (pintype "bidirectional"))
      (node (ref "SV10") (pin "M") (pinfunction "11_M") (pintype "bidirectional"))
      (node (ref "SV10") (pin "MM") (pinfunction "33_MM") (pintype "bidirectional"))
      (node (ref "SV10") (pin "P") (pinfunction "13_P") (pintype "bidirectional"))
      (node (ref "SV10") (pin "PP") (pinfunction "35_PP") (pintype "bidirectional"))
      (node (ref "SV10") (pin "S") (pinfunction "15_S") (pintype "bidirectional"))
      (node (ref "SV10") (pin "SS") (pinfunction "37_SS") (pintype "bidirectional"))
      (node (ref "SV10") (pin "U") (pinfunction "17_U") (pintype "bidirectional"))
      (node (ref "SV10") (pin "UU") (pinfunction "39_UU") (pintype "bidirectional"))
      (node (ref "SV10") (pin "V") (pinfunction "18_V") (pintype "bidirectional"))
      (node (ref "SV10") (pin "VV") (pinfunction "40_VV") (pintype "bidirectional"))
      (node (ref "SV10") (pin "W") (pinfunction "19_W") (pintype "bidirectional"))
      (node (ref "SV10") (pin "Y") (pinfunction "21_Y") (pintype "bidirectional"))
      (node (ref "SV2") (pin "A") (pinfunction "1_A") (pintype "bidirectional"))
      (node (ref "SV2") (pin "AA") (pinfunction "23_AA") (pintype "bidirectional"))
      (node (ref "SV2") (pin "B") (pinfunction "2_B") (pintype "bidirectional"))
      (node (ref "SV2") (pin "C") (pinfunction "3_C") (pintype "bidirectional"))
      (node (ref "SV2") (pin "CC") (pinfunction "25_CC") (pintype "bidirectional"))
      (node (ref "SV2") (pin "E") (pinfunction "5_E") (pintype "bidirectional"))
      (node (ref "SV2") (pin "EE") (pinfunction "27_EE") (pintype "bidirectional"))
      (node (ref "SV2") (pin "H") (pinfunction "7_H") (pintype "bidirectional"))
      (node (ref "SV2") (pin "HH") (pinfunction "29_HH") (pintype "bidirectional"))
      (node (ref "SV2") (pin "K") (pinfunction "9_K") (pintype "bidirectional"))
      (node (ref "SV2") (pin "KK") (pinfunction "31_KK") (pintype "bidirectional"))
      (node (ref "SV2") (pin "M") (pinfunction "11_M") (pintype "bidirectional"))
      (node (ref "SV2") (pin "MM") (pinfunction "33_MM") (pintype "bidirectional"))
      (node (ref "SV2") (pin "P") (pinfunction "13_P") (pintype "bidirectional"))
      (node (ref "SV2") (pin "PP") (pinfunction "35_PP") (pintype "bidirectional"))
      (node (ref "SV2") (pin "S") (pinfunction "15_S") (pintype "bidirectional"))
      (node (ref "SV2") (pin "SS") (pinfunction "37_SS") (pintype "bidirectional"))
      (node (ref "SV2") (pin "U") (pinfunction "17_U") (pintype "bidirectional"))
      (node (ref "SV2") (pin "UU") (pinfunction "39_UU") (pintype "bidirectional"))
      (node (ref "SV2") (pin "VV") (pinfunction "40_VV") (pintype "bidirectional"))
      (node (ref "SV2") (pin "W") (pinfunction "19_W") (pintype "bidirectional"))
      (node (ref "SV2") (pin "Y") (pinfunction "21_Y") (pintype "bidirectional"))
      (node (ref "SV3") (pin "A") (pinfunction "1_A") (pintype "bidirectional"))
      (node (ref "SV3") (pin "AA") (pinfunction "23_AA") (pintype "bidirectional"))
      (node (ref "SV3") (pin "B") (pinfunction "2_B") (pintype "bidirectional"))
      (node (ref "SV3") (pin "C") (pinfunction "3_C") (pintype "bidirectional"))
      (node (ref "SV3") (pin "CC") (pinfunction "25_CC") (pintype "bidirectional"))
      (node (ref "SV3") (pin "E") (pinfunction "5_E") (pintype "bidirectional"))
      (node (ref "SV3") (pin "EE") (pinfunction "27_EE") (pintype "bidirectional"))
      (node (ref "SV3") (pin "H") (pinfunction "7_H") (pintype "bidirectional"))
      (node (ref "SV3") (pin "HH") (pinfunction "29_HH") (pintype "bidirectional"))
      (node (ref "SV3") (pin "K") (pinfunction "9_K") (pintype "bidirectional"))
      (node (ref "SV3") (pin "KK") (pinfunction "31_KK") (pintype "bidirectional"))
      (node (ref "SV3") (pin "M") (pinfunction "11_M") (pintype "bidirectional"))
      (node (ref "SV3") (pin "MM") (pinfunction "33_MM") (pintype "bidirectional"))
      (node (ref "SV3") (pin "P") (pinfunction "13_P") (pintype "bidirectional"))
      (node (ref "SV3") (pin "PP") (pinfunction "35_PP") (pintype "bidirectional"))
      (node (ref "SV3") (pin "S") (pinfunction "15_S") (pintype "bidirectional"))
      (node (ref "SV3") (pin "SS") (pinfunction "37_SS") (pintype "bidirectional"))
      (node (ref "SV3") (pin "U") (pinfunction "17_U") (pintype "bidirectional"))
      (node (ref "SV3") (pin "UU") (pinfunction "39_UU") (pintype "bidirectional"))
      (node (ref "SV3") (pin "VV") (pinfunction "40_VV") (pintype "bidirectional"))
      (node (ref "SV3") (pin "W") (pinfunction "19_W") (pintype "bidirectional"))
      (node (ref "SV3") (pin "Y") (pinfunction "21_Y") (pintype "bidirectional"))
      (node (ref "SV4") (pin "A") (pinfunction "1_A") (pintype "bidirectional"))
      (node (ref "SV4") (pin "AA") (pinfunction "23_AA") (pintype "bidirectional"))
      (node (ref "SV4") (pin "B") (pinfunction "2_B") (pintype "bidirectional"))
      (node (ref "SV4") (pin "BB") (pinfunction "24_BB") (pintype "bidirectional"))
      (node (ref "SV4") (pin "C") (pinfunction "3_C") (pintype "bidirectional"))
      (node (ref "SV4") (pin "CC") (pinfunction "25_CC") (pintype "bidirectional"))
      (node (ref "SV4") (pin "D") (pinfunction "4_D") (pintype "bidirectional"))
      (node (ref "SV4") (pin "E") (pinfunction "5_E") (pintype "bidirectional"))
      (node (ref "SV4") (pin "EE") (pinfunction "27_EE") (pintype "bidirectional"))
      (node (ref "SV4") (pin "F") (pinfunction "6_F") (pintype "bidirectional"))
      (node (ref "SV4") (pin "FF") (pinfunction "28_FF") (pintype "bidirectional"))
      (node (ref "SV4") (pin "H") (pinfunction "7_H") (pintype "bidirectional"))
      (node (ref "SV4") (pin "HH") (pinfunction "29_HH") (pintype "bidirectional"))
      (node (ref "SV4") (pin "J") (pinfunction "8_J") (pintype "bidirectional"))
      (node (ref "SV4") (pin "K") (pinfunction "9_K") (pintype "bidirectional"))
      (node (ref "SV4") (pin "KK") (pinfunction "31_KK") (pintype "bidirectional"))
      (node (ref "SV4") (pin "LL") (pinfunction "32_LL") (pintype "bidirectional"))
      (node (ref "SV4") (pin "M") (pinfunction "11_M") (pintype "bidirectional"))
      (node (ref "SV4") (pin "MM") (pinfunction "33_MM") (pintype "bidirectional"))
      (node (ref "SV4") (pin "N") (pinfunction "12_N") (pintype "bidirectional"))
      (node (ref "SV4") (pin "P") (pinfunction "13_P") (pintype "bidirectional"))
      (node (ref "SV4") (pin "PP") (pinfunction "35_PP") (pintype "bidirectional"))
      (node (ref "SV4") (pin "RR") (pinfunction "36_RR") (pintype "bidirectional"))
      (node (ref "SV4") (pin "S") (pinfunction "15_S") (pintype "bidirectional"))
      (node (ref "SV4") (pin "SS") (pinfunction "37_SS") (pintype "bidirectional"))
      (node (ref "SV4") (pin "T") (pinfunction "16_T") (pintype "bidirectional"))
      (node (ref "SV4") (pin "U") (pinfunction "17_U") (pintype "bidirectional"))
      (node (ref "SV4") (pin "UU") (pinfunction "39_UU") (pintype "bidirectional"))
      (node (ref "SV4") (pin "VV") (pinfunction "40_VV") (pintype "bidirectional"))
      (node (ref "SV4") (pin "W") (pinfunction "19_W") (pintype "bidirectional"))
      (node (ref "SV4") (pin "X") (pinfunction "20_X") (pintype "bidirectional"))
      (node (ref "SV4") (pin "Y") (pinfunction "21_Y") (pintype "bidirectional"))
      (node (ref "SV5") (pin "A") (pinfunction "1_A") (pintype "bidirectional"))
      (node (ref "SV5") (pin "AA") (pinfunction "23_AA") (pintype "bidirectional"))
      (node (ref "SV5") (pin "B") (pinfunction "2_B") (pintype "bidirectional"))
      (node (ref "SV5") (pin "C") (pinfunction "3_C") (pintype "bidirectional"))
      (node (ref "SV5") (pin "CC") (pinfunction "25_CC") (pintype "bidirectional"))
      (node (ref "SV5") (pin "E") (pinfunction "5_E") (pintype "bidirectional"))
      (node (ref "SV5") (pin "EE") (pinfunction "27_EE") (pintype "bidirectional"))
      (node (ref "SV5") (pin "H") (pinfunction "7_H") (pintype "bidirectional"))
      (node (ref "SV5") (pin "HH") (pinfunction "29_HH") (pintype "bidirectional"))
      (node (ref "SV5") (pin "K") (pinfunction "9_K") (pintype "bidirectional"))
      (node (ref "SV5") (pin "KK") (pinfunction "31_KK") (pintype "bidirectional"))
      (node (ref "SV5") (pin "M") (pinfunction "11_M") (pintype "bidirectional"))
      (node (ref "SV5") (pin "MM") (pinfunction "33_MM") (pintype "bidirectional"))
      (node (ref "SV5") (pin "P") (pinfunction "13_P") (pintype "bidirectional"))
      (node (ref "SV5") (pin "PP") (pinfunction "35_PP") (pintype "bidirectional"))
      (node (ref "SV5") (pin "S") (pinfunction "15_S") (pintype "bidirectional"))
      (node (ref "SV5") (pin "SS") (pinfunction "37_SS") (pintype "bidirectional"))
      (node (ref "SV5") (pin "U") (pinfunction "17_U") (pintype "bidirectional"))
      (node (ref "SV5") (pin "UU") (pinfunction "39_UU") (pintype "bidirectional"))
      (node (ref "SV5") (pin "V") (pinfunction "18_V") (pintype "bidirectional"))
      (node (ref "SV5") (pin "VV") (pinfunction "40_VV") (pintype "bidirectional"))
      (node (ref "SV5") (pin "W") (pinfunction "19_W") (pintype "bidirectional"))
      (node (ref "SV5") (pin "Y") (pinfunction "21_Y") (pintype "bidirectional"))
      (node (ref "SV6") (pin "A") (pinfunction "1_A") (pintype "bidirectional"))
      (node (ref "SV6") (pin "AA") (pinfunction "23_AA") (pintype "bidirectional"))
      (node (ref "SV6") (pin "B") (pinfunction "2_B") (pintype "bidirectional"))
      (node (ref "SV6") (pin "C") (pinfunction "3_C") (pintype "bidirectional"))
      (node (ref "SV6") (pin "CC") (pinfunction "25_CC") (pintype "bidirectional"))
      (node (ref "SV6") (pin "E") (pinfunction "5_E") (pintype "bidirectional"))
      (node (ref "SV6") (pin "EE") (pinfunction "27_EE") (pintype "bidirectional"))
      (node (ref "SV6") (pin "H") (pinfunction "7_H") (pintype "bidirectional"))
      (node (ref "SV6") (pin "HH") (pinfunction "29_HH") (pintype "bidirectional"))
      (node (ref "SV6") (pin "K") (pinfunction "9_K") (pintype "bidirectional"))
      (node (ref "SV6") (pin "KK") (pinfunction "31_KK") (pintype "bidirectional"))
      (node (ref "SV6") (pin "M") (pinfunction "11_M") (pintype "bidirectional"))
      (node (ref "SV6") (pin "MM") (pinfunction "33_MM") (pintype "bidirectional"))
      (node (ref "SV6") (pin "P") (pinfunction "13_P") (pintype "bidirectional"))
      (node (ref "SV6") (pin "PP") (pinfunction "35_PP") (pintype "bidirectional"))
      (node (ref "SV6") (pin "S") (pinfunction "15_S") (pintype "bidirectional"))
      (node (ref "SV6") (pin "SS") (pinfunction "37_SS") (pintype "bidirectional"))
      (node (ref "SV6") (pin "U") (pinfunction "17_U") (pintype "bidirectional"))
      (node (ref "SV6") (pin "UU") (pinfunction "39_UU") (pintype "bidirectional"))
      (node (ref "SV6") (pin "VV") (pinfunction "40_VV") (pintype "bidirectional"))
      (node (ref "SV6") (pin "W") (pinfunction "19_W") (pintype "bidirectional"))
      (node (ref "SV6") (pin "Y") (pinfunction "21_Y") (pintype "bidirectional"))
      (node (ref "SV7") (pin "A") (pinfunction "1_A") (pintype "bidirectional"))
      (node (ref "SV7") (pin "AA") (pinfunction "23_AA") (pintype "bidirectional"))
      (node (ref "SV7") (pin "B") (pinfunction "2_B") (pintype "bidirectional"))
      (node (ref "SV7") (pin "C") (pinfunction "3_C") (pintype "bidirectional"))
      (node (ref "SV7") (pin "CC") (pinfunction "25_CC") (pintype "bidirectional"))
      (node (ref "SV7") (pin "E") (pinfunction "5_E") (pintype "bidirectional"))
      (node (ref "SV7") (pin "EE") (pinfunction "27_EE") (pintype "bidirectional"))
      (node (ref "SV7") (pin "H") (pinfunction "7_H") (pintype "bidirectional"))
      (node (ref "SV7") (pin "HH") (pinfunction "29_HH") (pintype "bidirectional"))
      (node (ref "SV7") (pin "K") (pinfunction "9_K") (pintype "bidirectional"))
      (node (ref "SV7") (pin "KK") (pinfunction "31_KK") (pintype "bidirectional"))
      (node (ref "SV7") (pin "M") (pinfunction "11_M") (pintype "bidirectional"))
      (node (ref "SV7") (pin "MM") (pinfunction "33_MM") (pintype "bidirectional"))
      (node (ref "SV7") (pin "P") (pinfunction "13_P") (pintype "bidirectional"))
      (node (ref "SV7") (pin "PP") (pinfunction "35_PP") (pintype "bidirectional"))
      (node (ref "SV7") (pin "S") (pinfunction "15_S") (pintype "bidirectional"))
      (node (ref "SV7") (pin "SS") (pinfunction "37_SS") (pintype "bidirectional"))
      (node (ref "SV7") (pin "U") (pinfunction "17_U") (pintype "bidirectional"))
      (node (ref "SV7") (pin "UU") (pinfunction "39_UU") (pintype "bidirectional"))
      (node (ref "SV7") (pin "VV") (pinfunction "40_VV") (pintype "bidirectional"))
      (node (ref "SV7") (pin "W") (pinfunction "19_W") (pintype "bidirectional"))
      (node (ref "SV7") (pin "Y") (pinfunction "21_Y") (pintype "bidirectional"))
      (node (ref "SV8") (pin "A") (pinfunction "1_A") (pintype "bidirectional"))
      (node (ref "SV8") (pin "AA") (pinfunction "23_AA") (pintype "bidirectional"))
      (node (ref "SV8") (pin "B") (pinfunction "2_B") (pintype "bidirectional"))
      (node (ref "SV8") (pin "C") (pinfunction "3_C") (pintype "bidirectional"))
      (node (ref "SV8") (pin "CC") (pinfunction "25_CC") (pintype "bidirectional"))
      (node (ref "SV8") (pin "E") (pinfunction "5_E") (pintype "bidirectional"))
      (node (ref "SV8") (pin "EE") (pinfunction "27_EE") (pintype "bidirectional"))
      (node (ref "SV8") (pin "H") (pinfunction "7_H") (pintype "bidirectional"))
      (node (ref "SV8") (pin "HH") (pinfunction "29_HH") (pintype "bidirectional"))
      (node (ref "SV8") (pin "K") (pinfunction "9_K") (pintype "bidirectional"))
      (node (ref "SV8") (pin "KK") (pinfunction "31_KK") (pintype "bidirectional"))
      (node (ref "SV8") (pin "M") (pinfunction "11_M") (pintype "bidirectional"))
      (node (ref "SV8") (pin "MM") (pinfunction "33_MM") (pintype "bidirectional"))
      (node (ref "SV8") (pin "P") (pinfunction "13_P") (pintype "bidirectional"))
      (node (ref "SV8") (pin "PP") (pinfunction "35_PP") (pintype "bidirectional"))
      (node (ref "SV8") (pin "S") (pinfunction "15_S") (pintype "bidirectional"))
      (node (ref "SV8") (pin "SS") (pinfunction "37_SS") (pintype "bidirectional"))
      (node (ref "SV8") (pin "U") (pinfunction "17_U") (pintype "bidirectional"))
      (node (ref "SV8") (pin "UU") (pinfunction "39_UU") (pintype "bidirectional"))
      (node (ref "SV8") (pin "VV") (pinfunction "40_VV") (pintype "bidirectional"))
      (node (ref "SV8") (pin "W") (pinfunction "19_W") (pintype "bidirectional"))
      (node (ref "SV8") (pin "Y") (pinfunction "21_Y") (pintype "bidirectional"))
      (node (ref "SV9") (pin "A") (pinfunction "1_A") (pintype "bidirectional"))
      (node (ref "SV9") (pin "AA") (pinfunction "23_AA") (pintype "bidirectional"))
      (node (ref "SV9") (pin "B") (pinfunction "2_B") (pintype "bidirectional"))
      (node (ref "SV9") (pin "BB") (pinfunction "24_BB") (pintype "bidirectional"))
      (node (ref "SV9") (pin "C") (pinfunction "3_C") (pintype "bidirectional"))
      (node (ref "SV9") (pin "CC") (pinfunction "25_CC") (pintype "bidirectional"))
      (node (ref "SV9") (pin "D") (pinfunction "4_D") (pintype "bidirectional"))
      (node (ref "SV9") (pin "E") (pinfunction "5_E") (pintype "bidirectional"))
      (node (ref "SV9") (pin "EE") (pinfunction "27_EE") (pintype "bidirectional"))
      (node (ref "SV9") (pin "F") (pinfunction "6_F") (pintype "bidirectional"))
      (node (ref "SV9") (pin "FF") (pinfunction "28_FF") (pintype "bidirectional"))
      (node (ref "SV9") (pin "H") (pinfunction "7_H") (pintype "bidirectional"))
      (node (ref "SV9") (pin "HH") (pinfunction "29_HH") (pintype "bidirectional"))
      (node (ref "SV9") (pin "J") (pinfunction "8_J") (pintype "bidirectional"))
      (node (ref "SV9") (pin "K") (pinfunction "9_K") (pintype "bidirectional"))
      (node (ref "SV9") (pin "KK") (pinfunction "31_KK") (pintype "bidirectional"))
      (node (ref "SV9") (pin "LL") (pinfunction "32_LL") (pintype "bidirectional"))
      (node (ref "SV9") (pin "M") (pinfunction "11_M") (pintype "bidirectional"))
      (node (ref "SV9") (pin "MM") (pinfunction "33_MM") (pintype "bidirectional"))
      (node (ref "SV9") (pin "N") (pinfunction "12_N") (pintype "bidirectional"))
      (node (ref "SV9") (pin "P") (pinfunction "13_P") (pintype "bidirectional"))
      (node (ref "SV9") (pin "PP") (pinfunction "35_PP") (pintype "bidirectional"))
      (node (ref "SV9") (pin "RR") (pinfunction "36_RR") (pintype "bidirectional"))
      (node (ref "SV9") (pin "S") (pinfunction "15_S") (pintype "bidirectional"))
      (node (ref "SV9") (pin "SS") (pinfunction "37_SS") (pintype "bidirectional"))
      (node (ref "SV9") (pin "T") (pinfunction "16_T") (pintype "bidirectional"))
      (node (ref "SV9") (pin "U") (pinfunction "17_U") (pintype "bidirectional"))
      (node (ref "SV9") (pin "UU") (pinfunction "39_UU") (pintype "bidirectional"))
      (node (ref "SV9") (pin "VV") (pinfunction "40_VV") (pintype "bidirectional"))
      (node (ref "SV9") (pin "W") (pinfunction "19_W") (pintype "bidirectional"))
      (node (ref "SV9") (pin "X") (pinfunction "20_X") (pintype "bidirectional"))
      (node (ref "SV9") (pin "Y") (pinfunction "21_Y") (pintype "bidirectional"))
    )
    (net (code "89") (name "IOP_1") (class "Default")
      (node (ref "IC87") (pin "5") (pinfunction "I1_5") (pintype "input"))
      (node (ref "IC88") (pin "10") (pinfunction "I1_10") (pintype "input"))
      (node (ref "SV1") (pin "V") (pinfunction "18_V") (pintype "bidirectional"))
      (node (ref "SV6") (pin "V") (pinfunction "18_V") (pintype "bidirectional"))
    )
    (net (code "90") (name "IOP_2") (class "Default")
      (node (ref "IC87") (pin "10") (pinfunction "I1_10") (pintype "input"))
      (node (ref "IC88") (pin "13") (pinfunction "I1_13") (pintype "input"))
      (node (ref "SV1") (pin "Z") (pinfunction "22_Z") (pintype "bidirectional"))
      (node (ref "SV6") (pin "Z") (pinfunction "22_Z") (pintype "bidirectional"))
    )
    (net (code "91") (name "IOP_4") (class "Default")
      (node (ref "IC87") (pin "13") (pinfunction "I1_13") (pintype "input"))
      (node (ref "IC90") (pin "2") (pinfunction "I1_2") (pintype "input"))
      (node (ref "SV1") (pin "DD") (pinfunction "26_DD") (pintype "bidirectional"))
      (node (ref "SV6") (pin "DD") (pinfunction "26_DD") (pintype "bidirectional"))
    )
    (net (code "92") (name "I{slash}O_B-BRK") (class "Default")
      (node (ref "IC79") (pin "5") (pinfunction "I1_5") (pintype "input"))
      (node (ref "SV4") (pin "DD") (pinfunction "26_DD") (pintype "bidirectional"))
      (node (ref "SV9") (pin "DD") (pinfunction "26_DD") (pintype "bidirectional"))
    )
    (net (code "93") (name "I{slash}O_B-RUN") (class "Default")
      (node (ref "IC79") (pin "2") (pinfunction "I1_2") (pintype "input"))
      (node (ref "SV3") (pin "JJ") (pinfunction "30_JJ") (pintype "bidirectional"))
      (node (ref "SV8") (pin "JJ") (pinfunction "30_JJ") (pintype "bidirectional"))
    )
    (net (code "94") (name "I{slash}O_BAC_00") (class "Default")
      (node (ref "IC83") (pin "2") (pinfunction "I1_2") (pintype "input"))
      (node (ref "SV1") (pin "D") (pinfunction "4_D") (pintype "bidirectional"))
      (node (ref "SV6") (pin "D") (pinfunction "4_D") (pintype "bidirectional"))
    )
    (net (code "95") (name "I{slash}O_BAC_01") (class "Default")
      (node (ref "IC83") (pin "5") (pinfunction "I1_5") (pintype "input"))
      (node (ref "SV1") (pin "J") (pinfunction "8_J") (pintype "bidirectional"))
      (node (ref "SV6") (pin "J") (pinfunction "8_J") (pintype "bidirectional"))
    )
    (net (code "96") (name "I{slash}O_BAC_02") (class "Default")
      (node (ref "IC85") (pin "10") (pinfunction "I1_10") (pintype "input"))
      (node (ref "SV1") (pin "N") (pinfunction "12_N") (pintype "bidirectional"))
      (node (ref "SV6") (pin "N") (pinfunction "12_N") (pintype "bidirectional"))
    )
    (net (code "97") (name "I{slash}O_BAC_03") (class "Default")
      (node (ref "IC84") (pin "10") (pinfunction "I1_10") (pintype "input"))
      (node (ref "SV1") (pin "T") (pinfunction "16_T") (pintype "bidirectional"))
      (node (ref "SV6") (pin "T") (pinfunction "16_T") (pintype "bidirectional"))
    )
    (net (code "98") (name "I{slash}O_BAC_04") (class "Default")
      (node (ref "IC84") (pin "13") (pinfunction "I1_13") (pintype "input"))
      (node (ref "SV1") (pin "X") (pinfunction "20_X") (pintype "bidirectional"))
      (node (ref "SV6") (pin "X") (pinfunction "20_X") (pintype "bidirectional"))
    )
    (net (code "99") (name "I{slash}O_BAC_05") (class "Default")
      (node (ref "IC85") (pin "2") (pinfunction "I1_2") (pintype "input"))
      (node (ref "SV1") (pin "BB") (pinfunction "24_BB") (pintype "bidirectional"))
      (node (ref "SV6") (pin "BB") (pinfunction "24_BB") (pintype "bidirectional"))
    )
    (net (code "100") (name "I{slash}O_BAC_06") (class "Default")
      (node (ref "IC85") (pin "5") (pinfunction "I1_5") (pintype "input"))
      (node (ref "SV1") (pin "FF") (pinfunction "28_FF") (pintype "bidirectional"))
      (node (ref "SV6") (pin "FF") (pinfunction "28_FF") (pintype "bidirectional"))
    )
    (net (code "101") (name "I{slash}O_BAC_07") (class "Default")
      (node (ref "IC84") (pin "5") (pinfunction "I1_5") (pintype "input"))
      (node (ref "SV1") (pin "LL") (pinfunction "32_LL") (pintype "bidirectional"))
      (node (ref "SV6") (pin "LL") (pinfunction "32_LL") (pintype "bidirectional"))
    )
    (net (code "102") (name "I{slash}O_BAC_08") (class "Default")
      (node (ref "IC83") (pin "10") (pinfunction "I1_10") (pintype "input"))
      (node (ref "SV1") (pin "RR") (pinfunction "36_RR") (pintype "bidirectional"))
      (node (ref "SV6") (pin "RR") (pinfunction "36_RR") (pintype "bidirectional"))
    )
    (net (code "103") (name "I{slash}O_BAC_09") (class "Default")
      (node (ref "IC83") (pin "13") (pinfunction "I1_13") (pintype "input"))
      (node (ref "SV1") (pin "F") (pinfunction "6_F") (pintype "bidirectional"))
      (node (ref "SV6") (pin "F") (pinfunction "6_F") (pintype "bidirectional"))
    )
    (net (code "104") (name "I{slash}O_BAC_10") (class "Default")
      (node (ref "IC84") (pin "2") (pinfunction "I1_2") (pintype "input"))
      (node (ref "SV1") (pin "L") (pinfunction "10_L") (pintype "bidirectional"))
      (node (ref "SV6") (pin "L") (pinfunction "10_L") (pintype "bidirectional"))
    )
    (net (code "105") (name "I{slash}O_BAC_11") (class "Default")
      (node (ref "IC85") (pin "13") (pinfunction "I1_13") (pintype "input"))
      (node (ref "SV1") (pin "R") (pinfunction "14_R") (pintype "bidirectional"))
      (node (ref "SV6") (pin "R") (pinfunction "14_R") (pintype "bidirectional"))
    )
    (net (code "106") (name "I{slash}O_BMB_00") (class "Default")
      (node (ref "IC79") (pin "13") (pinfunction "I1_13") (pintype "input"))
      (node (ref "SV2") (pin "D") (pinfunction "4_D") (pintype "bidirectional"))
      (node (ref "SV7") (pin "D") (pinfunction "4_D") (pintype "bidirectional"))
    )
    (net (code "107") (name "I{slash}O_BMB_01") (class "Default")
      (node (ref "IC80") (pin "2") (pinfunction "I1_2") (pintype "input"))
      (node (ref "SV2") (pin "J") (pinfunction "8_J") (pintype "bidirectional"))
      (node (ref "SV7") (pin "J") (pinfunction "8_J") (pintype "bidirectional"))
    )
    (net (code "108") (name "I{slash}O_BMB_02") (class "Default")
      (node (ref "IC82") (pin "5") (pinfunction "I1_5") (pintype "input"))
      (node (ref "SV2") (pin "N") (pinfunction "12_N") (pintype "bidirectional"))
      (node (ref "SV7") (pin "N") (pinfunction "12_N") (pintype "bidirectional"))
    )
    (net (code "109") (name "I{slash}O_BMB_03") (class "Default")
      (node (ref "IC81") (pin "5") (pinfunction "I1_5") (pintype "input"))
      (node (ref "IC86") (pin "1") (pinfunction "I0_1") (pintype "input"))
      (node (ref "IC89") (pin "1") (pinfunction "I0_1") (pintype "input"))
      (node (ref "SV2") (pin "X") (pinfunction "20_X") (pintype "bidirectional"))
      (node (ref "SV7") (pin "X") (pinfunction "20_X") (pintype "bidirectional"))
    )
    (net (code "110") (name "I{slash}O_BMB_04") (class "Default")
      (node (ref "IC81") (pin "10") (pinfunction "I1_10") (pintype "input"))
      (node (ref "IC86") (pin "2") (pinfunction "I1_2") (pintype "input"))
      (node (ref "IC89") (pin "2") (pinfunction "I1_2") (pintype "input"))
      (node (ref "SV2") (pin "FF") (pinfunction "28_FF") (pintype "bidirectional"))
      (node (ref "SV7") (pin "FF") (pinfunction "28_FF") (pintype "bidirectional"))
    )
    (net (code "111") (name "I{slash}O_BMB_05") (class "Default")
      (node (ref "IC81") (pin "13") (pinfunction "I1_13") (pintype "input"))
      (node (ref "IC86") (pin "3") (pinfunction "I2_3") (pintype "input"))
      (node (ref "IC89") (pin "3") (pinfunction "I2_3") (pintype "input"))
      (node (ref "SV2") (pin "RR") (pinfunction "36_RR") (pintype "bidirectional"))
      (node (ref "SV7") (pin "RR") (pinfunction "36_RR") (pintype "bidirectional"))
    )
    (net (code "112") (name "I{slash}O_BMB_06") (class "Default")
      (node (ref "IC82") (pin "2") (pinfunction "I1_2") (pintype "input"))
      (node (ref "IC86") (pin "4") (pinfunction "I3_4") (pintype "input"))
      (node (ref "IC89") (pin "4") (pinfunction "I3_4") (pintype "input"))
      (node (ref "SV2") (pin "L") (pinfunction "10_L") (pintype "bidirectional"))
      (node (ref "SV7") (pin "L") (pinfunction "10_L") (pintype "bidirectional"))
    )
    (net (code "113") (name "I{slash}O_BMB_07") (class "Default")
      (node (ref "IC81") (pin "2") (pinfunction "I1_2") (pintype "input"))
      (node (ref "IC86") (pin "5") (pinfunction "I4_5") (pintype "input"))
      (node (ref "IC89") (pin "5") (pinfunction "I4_5") (pintype "input"))
      (node (ref "SV2") (pin "V") (pinfunction "18_V") (pintype "bidirectional"))
      (node (ref "SV7") (pin "V") (pinfunction "18_V") (pintype "bidirectional"))
    )
    (net (code "114") (name "I{slash}O_BMB_08") (class "Default")
      (node (ref "IC80") (pin "5") (pinfunction "I1_5") (pintype "input"))
      (node (ref "IC89") (pin "6") (pinfunction "I5_6") (pintype "input"))
      (node (ref "SV2") (pin "DD") (pinfunction "26_DD") (pintype "bidirectional"))
      (node (ref "SV7") (pin "DD") (pinfunction "26_DD") (pintype "bidirectional"))
    )
    (net (code "115") (name "I{slash}O_BMB_09") (class "Default")
      (node (ref "IC80") (pin "10") (pinfunction "I1_10") (pintype "input"))
      (node (ref "SV2") (pin "JJ") (pinfunction "30_JJ") (pintype "bidirectional"))
      (node (ref "SV7") (pin "JJ") (pinfunction "30_JJ") (pintype "bidirectional"))
    )
    (net (code "116") (name "I{slash}O_BMB_10") (class "Default")
      (node (ref "IC80") (pin "13") (pinfunction "I1_13") (pintype "input"))
      (node (ref "SV2") (pin "NN") (pinfunction "34_NN") (pintype "bidirectional"))
      (node (ref "SV7") (pin "NN") (pinfunction "34_NN") (pintype "bidirectional"))
    )
    (net (code "117") (name "I{slash}O_BMB_11") (class "Default")
      (node (ref "IC82") (pin "10") (pinfunction "I1_10") (pintype "input"))
      (node (ref "SV2") (pin "TT") (pinfunction "38_TT") (pintype "bidirectional"))
      (node (ref "SV7") (pin "TT") (pinfunction "38_TT") (pintype "bidirectional"))
    )
    (net (code "118") (name "I{slash}O_DATA_IN") (class "Default")
      (node (ref "IC51") (pin "5") (pinfunction "O_5") (pintype "open_collector"))
      (node (ref "SV4") (pin "Z") (pinfunction "22_Z") (pintype "bidirectional"))
      (node (ref "SV9") (pin "Z") (pinfunction "22_Z") (pintype "bidirectional"))
    )
    (net (code "119") (name "I{slash}O_DATA_IN_") (class "Default")
      (node (ref "IC46") (pin "13") (pinfunction "O_13") (pintype "output"))
      (node (ref "IC51") (pin "6") (pinfunction "I0_6") (pintype "input"))
      (node (ref "IC51") (pin "7") (pinfunction "I1_7") (pintype "input"))
    )
    (net (code "120") (name "I{slash}O_PWR_CLR") (class "Default")
      (node (ref "IC90") (pin "4") (pinfunction "I0_4") (pintype "input"))
      (node (ref "SV1") (pin "TT") (pinfunction "38_TT") (pintype "bidirectional"))
      (node (ref "SV6") (pin "TT") (pinfunction "38_TT") (pintype "bidirectional"))
    )
    (net (code "121") (name "I{slash}O_TS03") (class "Default")
      (node (ref "IC88") (pin "1") (pinfunction "I0_1") (pintype "input"))
      (node (ref "SV1") (pin "JJ") (pinfunction "30_JJ") (pintype "bidirectional"))
      (node (ref "SV6") (pin "JJ") (pinfunction "30_JJ") (pintype "bidirectional"))
    )
    (net (code "122") (name "I{slash}O_TS04") (class "Default")
      (node (ref "SV1") (pin "NN") (pinfunction "34_NN") (pintype "bidirectional"))
      (node (ref "SV6") (pin "NN") (pinfunction "34_NN") (pintype "bidirectional"))
    )
    (net (code "123") (name "I{slash}~{O_0_TO_AC_}") (class "Default")
      (node (ref "IC45") (pin "13") (pinfunction "O_13") (pintype "output"))
      (node (ref "IC49") (pin "6") (pinfunction "I0_6") (pintype "input"))
      (node (ref "IC49") (pin "7") (pinfunction "I1_7") (pintype "input"))
    )
    (net (code "124") (name "I{slash}~{O_0_TO_AC}") (class "Default")
      (node (ref "IC49") (pin "5") (pinfunction "O_5") (pintype "open_collector"))
      (node (ref "SV3") (pin "DD") (pinfunction "26_DD") (pintype "bidirectional"))
      (node (ref "SV8") (pin "DD") (pinfunction "26_DD") (pintype "bidirectional"))
    )
    (net (code "125") (name "I{slash}~{O_1_TO_CA_INH_}") (class "Default")
      (node (ref "IC47") (pin "1") (pinfunction "O_1") (pintype "output"))
      (node (ref "IC52") (pin "1") (pinfunction "I0_1") (pintype "input"))
      (node (ref "IC52") (pin "2") (pinfunction "I1_2") (pintype "input"))
    )
    (net (code "126") (name "I{slash}~{O_1_TO_CA_INH}") (class "Default")
      (node (ref "IC52") (pin "3") (pinfunction "O_3") (pintype "open_collector"))
      (node (ref "SV10") (pin "Z") (pinfunction "22_Z") (pintype "bidirectional"))
      (node (ref "SV5") (pin "Z") (pinfunction "22_Z") (pintype "bidirectional"))
    )
    (net (code "127") (name "I{slash}~{O_ADDR_ACC}") (class "Default")
      (node (ref "IC82") (pin "13") (pinfunction "I1_13") (pintype "input"))
      (node (ref "SV4") (pin "JJ") (pinfunction "30_JJ") (pintype "bidirectional"))
      (node (ref "SV9") (pin "JJ") (pinfunction "30_JJ") (pintype "bidirectional"))
    )
    (net (code "128") (name "I{slash}~{O_BMB_03}") (class "Default")
      (node (ref "SV2") (pin "T") (pinfunction "16_T") (pintype "bidirectional"))
      (node (ref "SV7") (pin "T") (pinfunction "16_T") (pintype "bidirectional"))
    )
    (net (code "129") (name "I{slash}~{O_BMB_04}") (class "Default")
      (node (ref "SV2") (pin "BB") (pinfunction "24_BB") (pintype "bidirectional"))
      (node (ref "SV7") (pin "BB") (pinfunction "24_BB") (pintype "bidirectional"))
    )
    (net (code "130") (name "I{slash}~{O_BMB_05}") (class "Default")
      (node (ref "SV2") (pin "LL") (pinfunction "32_LL") (pintype "bidirectional"))
      (node (ref "SV7") (pin "LL") (pinfunction "32_LL") (pintype "bidirectional"))
    )
    (net (code "131") (name "I{slash}~{O_BMB_06}") (class "Default")
      (node (ref "SV2") (pin "F") (pinfunction "6_F") (pintype "bidirectional"))
      (node (ref "SV7") (pin "F") (pinfunction "6_F") (pintype "bidirectional"))
    )
    (net (code "132") (name "I{slash}~{O_BMB_07}") (class "Default")
      (node (ref "SV2") (pin "R") (pinfunction "14_R") (pintype "bidirectional"))
      (node (ref "SV7") (pin "R") (pinfunction "14_R") (pintype "bidirectional"))
    )
    (net (code "133") (name "I{slash}~{O_BMB_08}") (class "Default")
      (node (ref "IC86") (pin "6") (pinfunction "I5_6") (pintype "input"))
      (node (ref "SV2") (pin "Z") (pinfunction "22_Z") (pintype "bidirectional"))
      (node (ref "SV7") (pin "Z") (pinfunction "22_Z") (pintype "bidirectional"))
    )
    (net (code "134") (name "I{slash}~{O_BRK_RQ_}") (class "Default")
      (node (ref "IC45") (pin "1") (pinfunction "O_1") (pintype "output"))
      (node (ref "IC48") (pin "1") (pinfunction "I0_1") (pintype "input"))
      (node (ref "IC48") (pin "2") (pinfunction "I1_2") (pintype "input"))
    )
    (net (code "135") (name "I{slash}~{O_BRK_RQ}") (class "Default")
      (node (ref "IC48") (pin "3") (pinfunction "O_3") (pintype "open_collector"))
      (node (ref "SV4") (pin "V") (pinfunction "18_V") (pintype "bidirectional"))
      (node (ref "SV9") (pin "V") (pinfunction "18_V") (pintype "bidirectional"))
    )
    (net (code "136") (name "I{slash}~{O_BWC0}") (class "Default")
      (node (ref "IC79") (pin "10") (pinfunction "I1_10") (pintype "input"))
      (node (ref "SV10") (pin "DD") (pinfunction "26_DD") (pintype "bidirectional"))
      (node (ref "SV5") (pin "DD") (pinfunction "26_DD") (pintype "bidirectional"))
    )
    (net (code "137") (name "I{slash}~{O_INT_RQ_}") (class "Default")
      (node (ref "IC45") (pin "4") (pinfunction "O_4") (pintype "output"))
      (node (ref "IC48") (pin "6") (pinfunction "I0_6") (pintype "input"))
      (node (ref "IC48") (pin "7") (pinfunction "I1_7") (pintype "input"))
    )
    (net (code "138") (name "I{slash}~{O_INT_RQ}") (class "Default")
      (node (ref "IC48") (pin "5") (pinfunction "O_5") (pintype "open_collector"))
      (node (ref "SV3") (pin "Z") (pinfunction "22_Z") (pintype "bidirectional"))
      (node (ref "SV8") (pin "Z") (pinfunction "22_Z") (pintype "bidirectional"))
    )
    (net (code "139") (name "I{slash}~{O_SKP_RQ_}") (class "Default")
      (node (ref "IC45") (pin "10") (pinfunction "O_10") (pintype "output"))
      (node (ref "IC49") (pin "1") (pinfunction "I0_1") (pintype "input"))
      (node (ref "IC49") (pin "2") (pinfunction "I1_2") (pintype "input"))
    )
    (net (code "140") (name "I{slash}~{O_SKP_RQ}") (class "Default")
      (node (ref "IC49") (pin "3") (pinfunction "O_3") (pintype "open_collector"))
      (node (ref "SV3") (pin "V") (pinfunction "18_V") (pintype "bidirectional"))
      (node (ref "SV8") (pin "V") (pinfunction "18_V") (pintype "bidirectional"))
    )
    (net (code "141") (name "LDMF") (class "Default")
      (node (ref "IC115") (pin "11") (pinfunction "CLK_11") (pintype "input"))
      (node (ref "IC136") (pin "11") (pinfunction "CLK_11") (pintype "input"))
      (node (ref "IC136") (pin "3") (pinfunction "CLK_3") (pintype "input"))
      (node (ref "IC91") (pin "6") (pinfunction "O_6") (pintype "output"))
    )
    (net (code "142") (name "LPB_00") (class "Default")
      (node (ref "IC126") (pin "12") (pinfunction "Q_12") (pintype "output"))
      (node (ref "IC96") (pin "5") (pinfunction "2D_5") (pintype "input"))
      (node (ref "M916_9") (pin "T2") (pinfunction "P$2_T2") (pintype "bidirectional"))
    )
    (net (code "143") (name "LPB_01") (class "Default")
      (node (ref "IC127") (pin "12") (pinfunction "Q_12") (pintype "output"))
      (node (ref "IC98") (pin "10") (pinfunction "1E_10") (pintype "input"))
      (node (ref "M916_9") (pin "U2") (pinfunction "P$2_U2") (pintype "bidirectional"))
    )
    (net (code "144") (name "LPB_02") (class "Default")
      (node (ref "IC128") (pin "12") (pinfunction "Q_12") (pintype "output"))
      (node (ref "IC97") (pin "5") (pinfunction "2D_5") (pintype "input"))
      (node (ref "M916_9") (pin "V2") (pinfunction "P$2_V2") (pintype "bidirectional"))
    )
    (net (code "145") (name "LPB_03") (class "Default")
      (node (ref "IC126") (pin "9") (pinfunction "Q_9") (pintype "output"))
      (node (ref "IC96") (pin "10") (pinfunction "1E_10") (pintype "input"))
      (node (ref "M916_10") (pin "A2") (pinfunction "P$2_A2") (pintype "bidirectional"))
    )
    (net (code "146") (name "LPB_04") (class "Default")
      (node (ref "IC127") (pin "9") (pinfunction "Q_9") (pintype "output"))
      (node (ref "IC97") (pin "10") (pinfunction "1E_10") (pintype "input"))
      (node (ref "M916_10") (pin "B2") (pinfunction "P$2_B2") (pintype "bidirectional"))
    )
    (net (code "147") (name "LPB_05") (class "Default")
      (node (ref "IC128") (pin "9") (pinfunction "Q_9") (pintype "output"))
      (node (ref "IC98") (pin "5") (pinfunction "2D_5") (pintype "input"))
      (node (ref "M916_10") (pin "C2") (pinfunction "P$2_C2") (pintype "bidirectional"))
    )
    (net (code "148") (name "LPB_NOT_EQ_1") (class "Default")
      (node (ref "IC12") (pin "5") (pinfunction "I1_5") (pintype "input"))
      (node (ref "IC135") (pin "8") (pinfunction "O_8") (pintype "output"))
    )
    (net (code "149") (name "LPB_TO_DTB") (class "Default")
      (node (ref "IC15") (pin "10") (pinfunction "O_10") (pintype "output"))
      (node (ref "IC96") (pin "4") (pinfunction "2C_4") (pintype "input"))
      (node (ref "IC96") (pin "9") (pinfunction "1D_9") (pintype "input"))
      (node (ref "IC97") (pin "4") (pinfunction "2C_4") (pintype "input"))
      (node (ref "IC97") (pin "9") (pinfunction "1D_9") (pintype "input"))
      (node (ref "IC98") (pin "4") (pinfunction "2C_4") (pintype "input"))
      (node (ref "IC98") (pin "9") (pinfunction "1D_9") (pintype "input"))
    )
    (net (code "150") (name "MC00") (class "Default")
      (node (ref "IC133") (pin "5") (pinfunction "I4_5") (pintype "input"))
      (node (ref "IC73") (pin "12") (pinfunction "D_12") (pintype "input"))
      (node (ref "IC73") (pin "5") (pinfunction "Q_5") (pintype "output"))
      (node (ref "M916_10") (pin "S1") (pinfunction "P$2_S1") (pintype "bidirectional"))
    )
    (net (code "151") (name "MC01") (class "Default")
      (node (ref "IC6") (pin "11") (pinfunction "CLK_11") (pintype "input"))
      (node (ref "IC73") (pin "9") (pinfunction "Q_9") (pintype "output"))
      (node (ref "IC74") (pin "2") (pinfunction "D_2") (pintype "input"))
      (node (ref "IC90") (pin "13") (pinfunction "I1_13") (pintype "input"))
      (node (ref "M916_10") (pin "T1") (pinfunction "P$2_T1") (pintype "bidirectional"))
    )
    (net (code "152") (name "MC02") (class "Default")
      (node (ref "IC140") (pin "1") (pinfunction "I0_1") (pintype "input"))
      (node (ref "IC140") (pin "2") (pinfunction "I1_2") (pintype "input"))
      (node (ref "IC69") (pin "10") (pinfunction "I1_10") (pintype "input"))
      (node (ref "IC74") (pin "5") (pinfunction "Q_5") (pintype "output"))
      (node (ref "M916_10") (pin "U1") (pinfunction "P$2_U1") (pintype "bidirectional"))
    )
    (net (code "153") (name "MF00") (class "Default")
      (node (ref "IC115") (pin "9") (pinfunction "Q_9") (pintype "output"))
      (node (ref "M916_9") (pin "V1") (pinfunction "P$2_V1") (pintype "bidirectional"))
    )
    (net (code "154") (name "MF01") (class "Default")
      (node (ref "IC136") (pin "5") (pinfunction "Q_5") (pintype "output"))
      (node (ref "M916_10") (pin "A1") (pinfunction "P$2_A1") (pintype "bidirectional"))
    )
    (net (code "155") (name "MF02") (class "Default")
      (node (ref "IC136") (pin "9") (pinfunction "Q_9") (pintype "output"))
      (node (ref "M916_10") (pin "B1") (pinfunction "P$2_B1") (pintype "bidirectional"))
    )
    (net (code "156") (name "MKT") (class "Default")
      (node (ref "IC117") (pin "9") (pinfunction "I0_9") (pintype "input"))
      (node (ref "IC72") (pin "10") (pinfunction "I1_10") (pintype "input"))
      (node (ref "IC75") (pin "9") (pinfunction "Q_9") (pintype "output"))
      (node (ref "IC78") (pin "4") (pinfunction "I0_4") (pintype "input"))
      (node (ref "M916_10") (pin "H2") (pinfunction "P$2_H2") (pintype "bidirectional"))
    )
    (net (code "157") (name "MKTK") (class "Default")
      (node (ref "IC6") (pin "8") (pinfunction "~{Q}_8") (pintype "output"))
      (node (ref "M916_9") (pin "P1") (pinfunction "P$2_P1") (pintype "bidirectional"))
    )
    (net (code "158") (name "MK_BLK_END") (class "Default")
      (node (ref "IC10") (pin "12") (pinfunction "I2_12") (pintype "input"))
    )
    (net (code "159") (name "MK_BLK_MK") (class "Default")
      (node (ref "IC133") (pin "1") (pinfunction "I0_1") (pintype "input"))
      (node (ref "IC133") (pin "2") (pinfunction "I1_2") (pintype "input"))
    )
    (net (code "160") (name "MK_END") (class "Default")
      (node (ref "IC5") (pin "2") (pinfunction "D_2") (pintype "input"))
    )
    (net (code "161") (name "MOVE") (class "Default")
      (node (ref "IC123") (pin "10") (pinfunction "O_10") (pintype "output"))
    )
    (net (code "162") (name "MR00") (class "Default")
      (node (ref "IC57") (pin "9") (pinfunction "Q_9") (pintype "output"))
      (node (ref "IC76") (pin "12") (pinfunction "D_12") (pintype "input"))
    )
    (net (code "163") (name "MR01") (class "Default")
      (node (ref "IC108") (pin "2") (pinfunction "I1_2") (pintype "input"))
      (node (ref "IC95") (pin "9") (pinfunction "Q_9") (pintype "output"))
      (node (ref "M916_9") (pin "E1") (pinfunction "P$2_E1") (pintype "bidirectional"))
    )
    (net (code "164") (name "N$1") (class "Default")
      (node (ref "IC55") (pin "1") (pinfunction "I_1") (pintype "input"))
      (node (ref "IC61") (pin "3") (pinfunction "O_3") (pintype "output"))
    )
    (net (code "165") (name "N$2") (class "Default")
      (node (ref "IC112") (pin "10") (pinfunction "O_10") (pintype "output"))
      (node (ref "IC120") (pin "10") (pinfunction "I1_10") (pintype "input"))
      (node (ref "IC120") (pin "12") (pinfunction "I2_12") (pintype "input"))
      (node (ref "IC120") (pin "13") (pinfunction "I3_13") (pintype "input"))
      (node (ref "IC120") (pin "9") (pinfunction "I0_9") (pintype "input"))
    )
    (net (code "166") (name "N$3") (class "Default")
      (node (ref "IC15") (pin "3") (pinfunction "I_3") (pintype "input"))
      (node (ref "IC69") (pin "6") (pinfunction "O_6") (pintype "output"))
    )
    (net (code "167") (name "N$4") (class "Default")
      (node (ref "M916_19") (pin "R2") (pinfunction "P$2_R2") (pintype "bidirectional"))
      (node (ref "M916_19") (pin "S2") (pinfunction "P$2_S2") (pintype "bidirectional"))
    )
    (net (code "168") (name "N$5") (class "Default")
      (node (ref "IC121") (pin "6") (pinfunction "O_6") (pintype "output"))
      (node (ref "M916_2") (pin "H2") (pinfunction "P$2_H2") (pintype "bidirectional"))
    )
    (net (code "169") (name "N$6") (class "Default")
      (node (ref "IC121") (pin "10") (pinfunction "I1_10") (pintype "input"))
      (node (ref "IC121") (pin "12") (pinfunction "I2_12") (pintype "input"))
      (node (ref "IC121") (pin "13") (pinfunction "I3_13") (pintype "input"))
      (node (ref "IC121") (pin "9") (pinfunction "I0_9") (pintype "input"))
      (node (ref "M916_19") (pin "F2") (pinfunction "P$2_F2") (pintype "bidirectional"))
    )
    (net (code "170") (name "N$7") (class "Default")
      (node (ref "IC16") (pin "11") (pinfunction "O_11") (pintype "output"))
      (node (ref "IC16") (pin "5") (pinfunction "I1_5") (pintype "input"))
      (node (ref "IC17") (pin "4") (pinfunction "I0_4") (pintype "input"))
    )
    (net (code "171") (name "N$8") (class "Default")
      (node (ref "IC123") (pin "1") (pinfunction "I_1") (pintype "input"))
      (node (ref "M916_23") (pin "F2") (pinfunction "P$2_F2") (pintype "bidirectional"))
    )
    (net (code "172") (name "N$10") (class "Default")
      (node (ref "IC71") (pin "1") (pinfunction "I0_1") (pintype "input"))
      (node (ref "IC90") (pin "8") (pinfunction "O_8") (pintype "output"))
    )
    (net (code "173") (name "N$11") (class "Default")
      (node (ref "IC71") (pin "5") (pinfunction "I3_5") (pintype "input"))
      (node (ref "IC90") (pin "11") (pinfunction "O_11") (pintype "output"))
    )
    (net (code "174") (name "N$12") (class "Default")
      (node (ref "M916_23") (pin "D2") (pinfunction "P$2_D2") (pintype "bidirectional"))
      (node (ref "M916_23") (pin "E2") (pinfunction "P$2_E2") (pintype "bidirectional"))
    )
    (net (code "175") (name "N$13") (class "Default")
      (node (ref "IC61") (pin "8") (pinfunction "O_8") (pintype "output"))
      (node (ref "M916_1") (pin "H2") (pinfunction "P$2_H2") (pintype "bidirectional"))
      (node (ref "M916_1") (pin "J2") (pinfunction "P$2_J2") (pintype "bidirectional"))
      (node (ref "M916_1") (pin "K2") (pinfunction "P$2_K2") (pintype "bidirectional"))
    )
    (net (code "176") (name "N$14") (class "Default")
      (node (ref "M916_2") (pin "D2") (pinfunction "P$2_D2") (pintype "bidirectional"))
      (node (ref "M916_2") (pin "E2") (pinfunction "P$2_E2") (pintype "bidirectional"))
    )
    (net (code "177") (name "N$15") (class "Default")
      (node (ref "IC112") (pin "13") (pinfunction "I_13") (pintype "input"))
      (node (ref "M916_2") (pin "F2") (pinfunction "P$2_F2") (pintype "bidirectional"))
    )
    (net (code "178") (name "N$16") (class "Default")
      (node (ref "IC112") (pin "12") (pinfunction "O_12") (pintype "output"))
      (node (ref "IC18") (pin "4") (pinfunction "I2_4") (pintype "input"))
      (node (ref "IC18") (pin "5") (pinfunction "I3_5") (pintype "input"))
    )
    (net (code "179") (name "N$17") (class "Default")
      (node (ref "IC77") (pin "11") (pinfunction "CLK_11") (pintype "input"))
      (node (ref "IC77") (pin "3") (pinfunction "CLK_3") (pintype "input"))
      (node (ref "M916_21") (pin "D2") (pinfunction "P$2_D2") (pintype "bidirectional"))
    )
    (net (code "180") (name "N$18") (class "Default")
      (node (ref "IC61") (pin "11") (pinfunction "O_11") (pintype "output"))
      (node (ref "M916_1") (pin "M2") (pinfunction "P$2_M2") (pintype "bidirectional"))
      (node (ref "M916_1") (pin "N2") (pinfunction "P$2_N2") (pintype "bidirectional"))
      (node (ref "M916_1") (pin "P2") (pinfunction "P$2_P2") (pintype "bidirectional"))
    )
    (net (code "181") (name "N$19") (class "Default")
      (node (ref "M916_1") (pin "H1") (pinfunction "P$2_H1") (pintype "bidirectional"))
      (node (ref "M916_1") (pin "L2") (pinfunction "P$2_L2") (pintype "bidirectional"))
    )
    (net (code "182") (name "N$20") (class "Default")
      (node (ref "M916_2") (pin "R2") (pinfunction "P$2_R2") (pintype "bidirectional"))
      (node (ref "M916_2") (pin "S2") (pinfunction "P$2_S2") (pintype "bidirectional"))
    )
    (net (code "183") (name "N$21") (class "Default")
      (node (ref "M916_1") (pin "D2") (pinfunction "P$2_D2") (pintype "bidirectional"))
      (node (ref "M916_1") (pin "E2") (pinfunction "P$2_E2") (pintype "bidirectional"))
    )
    (net (code "184") (name "N$22") (class "Default")
      (node (ref "IC15") (pin "13") (pinfunction "I_13") (pintype "input"))
      (node (ref "M916_1") (pin "T2") (pinfunction "P$2_T2") (pintype "bidirectional"))
    )
    (net (code "185") (name "N$23") (class "Default")
      (node (ref "IC15") (pin "5") (pinfunction "I_5") (pintype "input"))
      (node (ref "M916_1") (pin "F2") (pinfunction "P$2_F2") (pintype "bidirectional"))
    )
    (net (code "186") (name "N$24") (class "Default")
      (node (ref "IC119") (pin "8") (pinfunction "O_8") (pintype "output"))
      (node (ref "M916_12") (pin "K2") (pinfunction "P$2_K2") (pintype "bidirectional"))
    )
    (net (code "187") (name "N$25") (class "Default")
      (node (ref "M916_1") (pin "R2") (pinfunction "P$2_R2") (pintype "bidirectional"))
      (node (ref "M916_1") (pin "V2") (pinfunction "P$2_V2") (pintype "bidirectional"))
    )
    (net (code "188") (name "N$26") (class "Default")
      (node (ref "M916_1") (pin "S1") (pinfunction "P$2_S1") (pintype "bidirectional"))
      (node (ref "M916_1") (pin "S2") (pinfunction "P$2_S2") (pintype "bidirectional"))
    )
    (net (code "189") (name "N$27") (class "Default")
      (node (ref "M916_21") (pin "N2") (pinfunction "P$2_N2") (pintype "bidirectional"))
      (node (ref "M916_21") (pin "S2") (pinfunction "P$2_S2") (pintype "bidirectional"))
    )
    (net (code "190") (name "N$28") (class "Default")
      (node (ref "IC109") (pin "12") (pinfunction "O_12") (pintype "output"))
      (node (ref "IC72") (pin "2") (pinfunction "I1_2") (pintype "input"))
    )
    (net (code "191") (name "N$29") (class "Default")
      (node (ref "M916_12") (pin "D2") (pinfunction "P$2_D2") (pintype "bidirectional"))
      (node (ref "M916_12") (pin "E2") (pinfunction "P$2_E2") (pintype "bidirectional"))
    )
    (net (code "192") (name "N$30") (class "Default")
      (node (ref "IC122") (pin "3") (pinfunction "I_3") (pintype "input"))
      (node (ref "M916_12") (pin "F2") (pinfunction "P$2_F2") (pintype "bidirectional"))
    )
    (net (code "193") (name "N$31") (class "Default")
      (node (ref "IC122") (pin "4") (pinfunction "O_4") (pintype "output"))
      (node (ref "IC19") (pin "10") (pinfunction "I1_10") (pintype "input"))
      (node (ref "IC19") (pin "9") (pinfunction "I0_9") (pintype "input"))
    )
    (net (code "194") (name "N$32") (class "Default")
      (node (ref "IC78") (pin "8") (pinfunction "O_8") (pintype "output"))
    )
    (net (code "195") (name "N$33") (class "Default")
      (node (ref "IC66") (pin "6") (pinfunction "O_6") (pintype "output"))
      (node (ref "IC7") (pin "10") (pinfunction "PRE_10") (pintype "input"))
    )
    (net (code "196") (name "N$34") (class "Default")
      (node (ref "IC123") (pin "9") (pinfunction "I_9") (pintype "input"))
      (node (ref "M916_22") (pin "T2") (pinfunction "P$2_T2") (pintype "bidirectional"))
    )
    (net (code "197") (name "N$35") (class "Default")
      (node (ref "IC104") (pin "8") (pinfunction "1Y_8") (pintype "output"))
      (node (ref "IC8") (pin "9") (pinfunction "I0_9") (pintype "input"))
    )
    (net (code "198") (name "N$36") (class "Default")
      (node (ref "IC115") (pin "2") (pinfunction "D_2") (pintype "input"))
      (node (ref "IC99") (pin "6") (pinfunction "O_6") (pintype "output"))
    )
    (net (code "199") (name "N$37") (class "Default")
      (node (ref "M916_12") (pin "R2") (pinfunction "P$2_R2") (pintype "bidirectional"))
      (node (ref "M916_12") (pin "S2") (pinfunction "P$2_S2") (pintype "bidirectional"))
    )
    (net (code "200") (name "N$38") (class "Default")
      (node (ref "IC116") (pin "12") (pinfunction "I0_12") (pintype "input"))
      (node (ref "IC116") (pin "3") (pinfunction "O_3") (pintype "output"))
    )
    (net (code "201") (name "N$39") (class "Default")
      (node (ref "IC116") (pin "13") (pinfunction "I1_13") (pintype "input"))
      (node (ref "IC116") (pin "6") (pinfunction "O_6") (pintype "output"))
    )
    (net (code "202") (name "N$40") (class "Default")
      (node (ref "M916_20") (pin "M2") (pinfunction "P$2_M2") (pintype "bidirectional"))
      (node (ref "M916_20") (pin "V2") (pinfunction "P$2_V2") (pintype "bidirectional"))
    )
    (net (code "203") (name "N$41") (class "Default")
      (node (ref "M916_20") (pin "P1") (pinfunction "P$2_P1") (pintype "bidirectional"))
      (node (ref "M916_20") (pin "V1") (pinfunction "P$2_V1") (pintype "bidirectional"))
    )
    (net (code "204") (name "N$42") (class "Default")
      (node (ref "IC106") (pin "12") (pinfunction "I0_12") (pintype "input"))
      (node (ref "IC106") (pin "6") (pinfunction "O_6") (pintype "output"))
    )
    (net (code "205") (name "N$43") (class "Default")
      (node (ref "IC17") (pin "12") (pinfunction "I0_12") (pintype "input"))
      (node (ref "IC17") (pin "3") (pinfunction "O_3") (pintype "output"))
    )
    (net (code "206") (name "N$44") (class "Default")
      (node (ref "IC106") (pin "11") (pinfunction "O_11") (pintype "output"))
      (node (ref "IC72") (pin "13") (pinfunction "I3_13") (pintype "input"))
    )
    (net (code "207") (name "N$45") (class "Default")
      (node (ref "IC17") (pin "13") (pinfunction "I1_13") (pintype "input"))
      (node (ref "IC17") (pin "8") (pinfunction "O_8") (pintype "output"))
    )
    (net (code "208") (name "N$46") (class "Default")
      (node (ref "IC11") (pin "11") (pinfunction "O_11") (pintype "output"))
      (node (ref "IC8") (pin "12") (pinfunction "I2_12") (pintype "input"))
    )
    (net (code "209") (name "N$47") (class "Default")
      (node (ref "IC68") (pin "8") (pinfunction "O_8") (pintype "output"))
      (node (ref "IC99") (pin "5") (pinfunction "I_5") (pintype "input"))
    )
    (net (code "210") (name "N$48") (class "Default")
      (node (ref "IC107") (pin "4") (pinfunction "I0_4") (pintype "input"))
      (node (ref "IC71") (pin "6") (pinfunction "O_6") (pintype "output"))
    )
    (net (code "211") (name "N$49") (class "Default")
      (node (ref "IC68") (pin "10") (pinfunction "I1_10") (pintype "input"))
      (node (ref "IC70") (pin "8") (pinfunction "O_8") (pintype "output"))
    )
    (net (code "212") (name "N$50") (class "Default")
      (node (ref "IC110") (pin "12") (pinfunction "O_12") (pintype "output"))
      (node (ref "IC117") (pin "12") (pinfunction "I0_12") (pintype "input"))
    )
    (net (code "213") (name "N$51") (class "Default")
      (node (ref "IC108") (pin "4") (pinfunction "I1_4") (pintype "input"))
      (node (ref "IC72") (pin "8") (pinfunction "O_8") (pintype "output"))
    )
    (net (code "214") (name "N$52") (class "Default")
      (node (ref "IC107") (pin "6") (pinfunction "O_6") (pintype "output"))
      (node (ref "IC108") (pin "3") (pinfunction "I0_3") (pintype "input"))
    )
    (net (code "215") (name "N$53") (class "Default")
      (node (ref "IC117") (pin "13") (pinfunction "I1_13") (pintype "input"))
      (node (ref "IC117") (pin "6") (pinfunction "O_6") (pintype "output"))
    )
    (net (code "216") (name "N$54") (class "Default")
      (node (ref "IC106") (pin "3") (pinfunction "O_3") (pintype "output"))
      (node (ref "IC108") (pin "5") (pinfunction "I2_5") (pintype "input"))
    )
    (net (code "217") (name "N$55") (class "Default")
      (node (ref "IC68") (pin "9") (pinfunction "I0_9") (pintype "input"))
      (node (ref "IC70") (pin "6") (pinfunction "O_6") (pintype "output"))
    )
    (net (code "218") (name "N$56") (class "Default")
      (node (ref "IC2") (pin "6") (pinfunction "O_6") (pintype "output"))
      (node (ref "IC68") (pin "11") (pinfunction "I2_11") (pintype "input"))
    )
    (net (code "219") (name "N$58") (class "Default")
      (node (ref "IC15") (pin "9") (pinfunction "I_9") (pintype "input"))
      (node (ref "IC61") (pin "6") (pinfunction "O_6") (pintype "output"))
    )
    (net (code "220") (name "N$59") (class "Default")
      (node (ref "IC107") (pin "11") (pinfunction "O_11") (pintype "output"))
      (node (ref "IC112") (pin "3") (pinfunction "I_3") (pintype "input"))
    )
    (net (code "221") (name "N$60") (class "Default")
      (node (ref "IC108") (pin "8") (pinfunction "O_8") (pintype "output"))
      (node (ref "IC72") (pin "1") (pinfunction "I0_1") (pintype "input"))
    )
    (net (code "222") (name "N$61") (class "Default")
      (node (ref "IC110") (pin "6") (pinfunction "O_6") (pintype "output"))
      (node (ref "IC72") (pin "4") (pinfunction "I2_4") (pintype "input"))
    )
    (net (code "223") (name "N$62") (class "Default")
      (node (ref "IC71") (pin "8") (pinfunction "O_8") (pintype "output"))
      (node (ref "IC72") (pin "5") (pinfunction "I3_5") (pintype "input"))
    )
    (net (code "224") (name "N$63") (class "Default")
      (node (ref "IC74") (pin "10") (pinfunction "PRE_10") (pintype "input"))
      (node (ref "IC78") (pin "3") (pinfunction "O_3") (pintype "output"))
    )
    (net (code "225") (name "N$64") (class "Default")
      (node (ref "IC16") (pin "8") (pinfunction "O_8") (pintype "output"))
      (node (ref "IC65") (pin "4") (pinfunction "I2_4") (pintype "input"))
      (node (ref "IC65") (pin "5") (pinfunction "I3_5") (pintype "input"))
    )
    (net (code "226") (name "N$65") (class "Default")
      (node (ref "IC107") (pin "12") (pinfunction "I0_12") (pintype "input"))
      (node (ref "IC107") (pin "8") (pinfunction "O_8") (pintype "output"))
    )
    (net (code "227") (name "N$66") (class "Default")
      (node (ref "IC16") (pin "3") (pinfunction "O_3") (pintype "output"))
      (node (ref "IC65") (pin "1") (pinfunction "I0_1") (pintype "input"))
      (node (ref "IC65") (pin "2") (pinfunction "I1_2") (pintype "input"))
    )
    (net (code "228") (name "N$67") (class "Default")
      (node (ref "IC134") (pin "8") (pinfunction "O_8") (pintype "output"))
      (node (ref "M916_20") (pin "J2") (pinfunction "P$2_J2") (pintype "bidirectional"))
    )
    (net (code "229") (name "N$68") (class "Default")
      (node (ref "M916_20") (pin "D2") (pinfunction "P$2_D2") (pintype "bidirectional"))
      (node (ref "M916_20") (pin "H1") (pinfunction "P$2_H1") (pintype "bidirectional"))
    )
    (net (code "230") (name "N$69") (class "Default")
      (node (ref "M916_20") (pin "A1") (pinfunction "P$2_A1") (pintype "bidirectional"))
      (node (ref "M916_20") (pin "C1") (pinfunction "P$2_C1") (pintype "bidirectional"))
    )
    (net (code "231") (name "N$70") (class "Default")
      (node (ref "IC2") (pin "9") (pinfunction "I0_9") (pintype "input"))
      (node (ref "IC68") (pin "6") (pinfunction "O_6") (pintype "output"))
    )
    (net (code "232") (name "N$71") (class "Default")
      (node (ref "IC122") (pin "1") (pinfunction "I_1") (pintype "input"))
      (node (ref "IC78") (pin "6") (pinfunction "O_6") (pintype "output"))
    )
    (net (code "233") (name "N$72") (class "Default")
      (node (ref "IC2") (pin "11") (pinfunction "I2_11") (pintype "input"))
      (node (ref "IC68") (pin "12") (pinfunction "O_12") (pintype "output"))
    )
    (net (code "234") (name "N$73") (class "Default")
      (node (ref "IC60") (pin "6") (pinfunction "O_6") (pintype "output"))
      (node (ref "IC63") (pin "10") (pinfunction "PRE_10") (pintype "input"))
    )
    (net (code "235") (name "N$76") (class "Default")
      (node (ref "IC114") (pin "11") (pinfunction "CLK_11") (pintype "input"))
      (node (ref "IC118") (pin "3") (pinfunction "O_3") (pintype "output"))
    )
    (net (code "236") (name "N$77") (class "Default")
      (node (ref "IC2") (pin "8") (pinfunction "O_8") (pintype "output"))
      (node (ref "IC65") (pin "9") (pinfunction "I0_9") (pintype "input"))
    )
    (net (code "237") (name "N$78") (class "Default")
      (node (ref "IC122") (pin "2") (pinfunction "O_2") (pintype "output"))
      (node (ref "IC65") (pin "13") (pinfunction "I3_13") (pintype "input"))
    )
    (net (code "238") (name "N$79") (class "Default")
      (node (ref "IC111") (pin "10") (pinfunction "O_10") (pintype "output"))
      (node (ref "IC114") (pin "10") (pinfunction "PRE_10") (pintype "input"))
    )
    (net (code "239") (name "N$80") (class "Default")
      (node (ref "IC8") (pin "13") (pinfunction "I3_13") (pintype "input"))
      (node (ref "M916_15") (pin "U2") (pinfunction "P$2_U2") (pintype "bidirectional"))
    )
    (net (code "240") (name "N$81") (class "Default")
      (node (ref "IC108") (pin "12") (pinfunction "O_12") (pintype "output"))
      (node (ref "IC111") (pin "11") (pinfunction "I_11") (pintype "input"))
    )
    (net (code "241") (name "N$82") (class "Default")
      (node (ref "IC122") (pin "5") (pinfunction "I_5") (pintype "input"))
      (node (ref "IC69") (pin "8") (pinfunction "O_8") (pintype "output"))
    )
    (net (code "242") (name "N$83") (class "Default")
      (node (ref "IC5") (pin "12") (pinfunction "D_12") (pintype "input"))
      (node (ref "IC8") (pin "8") (pinfunction "O_8") (pintype "output"))
    )
    (net (code "243") (name "N$84") (class "Default")
      (node (ref "IC11") (pin "3") (pinfunction "O_3") (pintype "output"))
      (node (ref "IC11") (pin "4") (pinfunction "I0_4") (pintype "input"))
    )
    (net (code "244") (name "N$85") (class "Default")
      (node (ref "IC11") (pin "2") (pinfunction "I1_2") (pintype "input"))
      (node (ref "IC11") (pin "6") (pinfunction "O_6") (pintype "output"))
      (node (ref "IC78") (pin "12") (pinfunction "I0_12") (pintype "input"))
    )
    (net (code "245") (name "N$86") (class "Default")
      (node (ref "IC69") (pin "13") (pinfunction "I2_13") (pintype "input"))
      (node (ref "IC78") (pin "11") (pinfunction "O_11") (pintype "output"))
    )
    (net (code "246") (name "N$88") (class "Default")
      (node (ref "M916_23") (pin "R2") (pinfunction "P$2_R2") (pintype "bidirectional"))
      (node (ref "M916_23") (pin "S2") (pinfunction "P$2_S2") (pintype "bidirectional"))
    )
    (net (code "247") (name "N$91") (class "Default")
      (node (ref "IC60") (pin "11") (pinfunction "O_11") (pintype "output"))
      (node (ref "IC64") (pin "4") (pinfunction "PRE_4") (pintype "input"))
    )
    (net (code "248") (name "N$92") (class "Default")
      (node (ref "IC59") (pin "11") (pinfunction "O_11") (pintype "output"))
      (node (ref "IC62") (pin "10") (pinfunction "PRE_10") (pintype "input"))
    )
    (net (code "249") (name "N$93") (class "Default")
      (node (ref "IC126") (pin "14") (pinfunction "J_14") (pintype "input"))
      (node (ref "IC126") (pin "3") (pinfunction "K_3") (pintype "input"))
      (node (ref "IC129") (pin "6") (pinfunction "2Y_6") (pintype "output"))
    )
    (net (code "250") (name "N$94") (class "Default")
      (node (ref "IC126") (pin "10") (pinfunction "K_10") (pintype "input"))
      (node (ref "IC126") (pin "7") (pinfunction "J_7") (pintype "input"))
      (node (ref "IC129") (pin "8") (pinfunction "1Y_8") (pintype "output"))
    )
    (net (code "251") (name "N$95") (class "Default")
      (node (ref "IC127") (pin "14") (pinfunction "J_14") (pintype "input"))
      (node (ref "IC127") (pin "3") (pinfunction "K_3") (pintype "input"))
      (node (ref "IC131") (pin "8") (pinfunction "1Y_8") (pintype "output"))
    )
    (net (code "252") (name "N$96") (class "Default")
      (node (ref "IC128") (pin "14") (pinfunction "J_14") (pintype "input"))
      (node (ref "IC128") (pin "3") (pinfunction "K_3") (pintype "input"))
      (node (ref "IC130") (pin "6") (pinfunction "2Y_6") (pintype "output"))
    )
    (net (code "253") (name "N$97") (class "Default")
      (node (ref "IC59") (pin "3") (pinfunction "O_3") (pintype "output"))
      (node (ref "IC62") (pin "4") (pinfunction "PRE_4") (pintype "input"))
    )
    (net (code "254") (name "N$99") (class "Default")
      (node (ref "IC128") (pin "10") (pinfunction "K_10") (pintype "input"))
      (node (ref "IC128") (pin "7") (pinfunction "J_7") (pintype "input"))
      (node (ref "IC131") (pin "6") (pinfunction "2Y_6") (pintype "output"))
    )
    (net (code "255") (name "N$100") (class "Default")
      (node (ref "IC127") (pin "10") (pinfunction "K_10") (pintype "input"))
      (node (ref "IC127") (pin "7") (pinfunction "J_7") (pintype "input"))
      (node (ref "IC130") (pin "8") (pinfunction "1Y_8") (pintype "output"))
    )
    (net (code "256") (name "N$101") (class "Default")
      (node (ref "IC123") (pin "6") (pinfunction "O_6") (pintype "output"))
      (node (ref "IC126") (pin "5") (pinfunction "CLK_5") (pintype "input"))
      (node (ref "IC127") (pin "5") (pinfunction "CLK_5") (pintype "input"))
      (node (ref "IC128") (pin "5") (pinfunction "CLK_5") (pintype "input"))
    )
    (net (code "257") (name "N$103") (class "Default")
      (node (ref "IC122") (pin "12") (pinfunction "O_12") (pintype "output"))
      (node (ref "IC126") (pin "1") (pinfunction "CLK_1") (pintype "input"))
      (node (ref "IC127") (pin "1") (pinfunction "CLK_1") (pintype "input"))
      (node (ref "IC128") (pin "1") (pinfunction "CLK_1") (pintype "input"))
    )
    (net (code "258") (name "N$104") (class "Default")
      (node (ref "IC101") (pin "10") (pinfunction "PRE_10") (pintype "input"))
      (node (ref "IC96") (pin "8") (pinfunction "1Y_8") (pintype "output"))
    )
    (net (code "259") (name "N$105") (class "Default")
      (node (ref "IC4") (pin "9") (pinfunction "I_9") (pintype "input"))
      (node (ref "IC8") (pin "6") (pinfunction "O_6") (pintype "output"))
    )
    (net (code "260") (name "N$106") (class "Default")
      (node (ref "IC4") (pin "8") (pinfunction "O_8") (pintype "output"))
      (node (ref "IC9") (pin "13") (pinfunction "I3_13") (pintype "input"))
    )
    (net (code "261") (name "N$107") (class "Default")
      (node (ref "IC6") (pin "12") (pinfunction "D_12") (pintype "input"))
      (node (ref "IC9") (pin "8") (pinfunction "O_8") (pintype "output"))
    )
    (net (code "262") (name "N$108") (class "Default")
      (node (ref "IC103") (pin "8") (pinfunction "1Y_8") (pintype "output"))
      (node (ref "IC122") (pin "13") (pinfunction "I_13") (pintype "input"))
    )
    (net (code "263") (name "N$109") (class "Default")
      (node (ref "IC105") (pin "6") (pinfunction "2Y_6") (pintype "output"))
      (node (ref "IC123") (pin "5") (pinfunction "I_5") (pintype "input"))
    )
    (net (code "264") (name "N$111") (class "Default")
      (node (ref "IC10") (pin "13") (pinfunction "I3_13") (pintype "input"))
      (node (ref "IC123") (pin "4") (pinfunction "O_4") (pintype "output"))
    )
    (net (code "265") (name "N$112") (class "Default")
      (node (ref "IC59") (pin "6") (pinfunction "O_6") (pintype "output"))
      (node (ref "IC64") (pin "10") (pinfunction "PRE_10") (pintype "input"))
    )
    (net (code "266") (name "N$113") (class "Default")
      (node (ref "IC59") (pin "8") (pinfunction "O_8") (pintype "output"))
      (node (ref "IC63") (pin "4") (pinfunction "PRE_4") (pintype "input"))
    )
    (net (code "267") (name "N$114") (class "Default")
      (node (ref "IC10") (pin "8") (pinfunction "O_8") (pintype "output"))
      (node (ref "IC15") (pin "11") (pinfunction "I_11") (pintype "input"))
    )
    (net (code "268") (name "N$115") (class "Default")
      (node (ref "IC117") (pin "8") (pinfunction "O_8") (pintype "output"))
      (node (ref "IC123") (pin "3") (pinfunction "I_3") (pintype "input"))
    )
    (net (code "269") (name "N$116") (class "Default")
      (node (ref "IC112") (pin "5") (pinfunction "I_5") (pintype "input"))
      (node (ref "IC117") (pin "3") (pinfunction "O_3") (pintype "output"))
    )
    (net (code "270") (name "N$117") (class "Default")
      (node (ref "IC109") (pin "6") (pinfunction "O_6") (pintype "output"))
      (node (ref "IC140") (pin "12") (pinfunction "I2_12") (pintype "input"))
      (node (ref "IC140") (pin "13") (pinfunction "I3_13") (pintype "input"))
    )
    (net (code "271") (name "N$118") (class "Default")
      (node (ref "IC106") (pin "8") (pinfunction "O_8") (pintype "output"))
      (node (ref "IC140") (pin "10") (pinfunction "I1_10") (pintype "input"))
      (node (ref "IC140") (pin "9") (pinfunction "I0_9") (pintype "input"))
    )
    (net (code "272") (name "N$119") (class "Default")
      (node (ref "IC112") (pin "1") (pinfunction "I_1") (pintype "input"))
      (node (ref "IC116") (pin "8") (pinfunction "O_8") (pintype "output"))
    )
    (net (code "273") (name "N$123") (class "Default")
      (node (ref "M916_3") (pin "D2") (pinfunction "P$2_D2") (pintype "bidirectional"))
      (node (ref "M916_3") (pin "J2") (pinfunction "P$2_J2") (pintype "bidirectional"))
    )
    (net (code "274") (name "N$124") (class "Default")
      (node (ref "IC12") (pin "11") (pinfunction "O_11") (pintype "output"))
      (node (ref "IC4") (pin "11") (pinfunction "I_11") (pintype "input"))
    )
    (net (code "275") (name "N$125") (class "Default")
      (node (ref "IC12") (pin "6") (pinfunction "O_6") (pintype "output"))
      (node (ref "IC7") (pin "2") (pinfunction "D_2") (pintype "input"))
    )
    (net (code "276") (name "N$126") (class "Default")
      (node (ref "M916_3") (pin "E2") (pinfunction "P$2_E2") (pintype "bidirectional"))
      (node (ref "M916_3") (pin "K2") (pinfunction "P$2_K2") (pintype "bidirectional"))
    )
    (net (code "277") (name "N$127") (class "Default")
      (node (ref "M916_13") (pin "D2") (pinfunction "P$2_D2") (pintype "bidirectional"))
      (node (ref "M916_13") (pin "J2") (pinfunction "P$2_J2") (pintype "bidirectional"))
    )
    (net (code "278") (name "N$128") (class "Default")
      (node (ref "IC4") (pin "10") (pinfunction "O_10") (pintype "output"))
      (node (ref "IC7") (pin "3") (pinfunction "CLK_3") (pintype "input"))
    )
    (net (code "279") (name "N$129") (class "Default")
      (node (ref "IC102") (pin "10") (pinfunction "PRE_10") (pintype "input"))
      (node (ref "IC98") (pin "6") (pinfunction "2Y_6") (pintype "output"))
    )
    (net (code "280") (name "N$130") (class "Default")
      (node (ref "M916_13") (pin "E2") (pinfunction "P$2_E2") (pintype "bidirectional"))
      (node (ref "M916_13") (pin "K2") (pinfunction "P$2_K2") (pintype "bidirectional"))
    )
    (net (code "281") (name "N$131") (class "Default")
      (node (ref "M916_4") (pin "D2") (pinfunction "P$2_D2") (pintype "bidirectional"))
      (node (ref "M916_4") (pin "J2") (pinfunction "P$2_J2") (pintype "bidirectional"))
    )
    (net (code "282") (name "N$132") (class "Default")
      (node (ref "IC4") (pin "12") (pinfunction "O_12") (pintype "output"))
      (node (ref "IC6") (pin "4") (pinfunction "PRE_4") (pintype "input"))
    )
    (net (code "283") (name "N$133") (class "Default")
      (node (ref "M916_4") (pin "E2") (pinfunction "P$2_E2") (pintype "bidirectional"))
      (node (ref "M916_4") (pin "K2") (pinfunction "P$2_K2") (pintype "bidirectional"))
    )
    (net (code "284") (name "N$134") (class "Default")
      (node (ref "M916_14") (pin "D2") (pinfunction "P$2_D2") (pintype "bidirectional"))
      (node (ref "M916_14") (pin "J2") (pinfunction "P$2_J2") (pintype "bidirectional"))
    )
    (net (code "285") (name "N$135") (class "Default")
      (node (ref "M916_14") (pin "E2") (pinfunction "P$2_E2") (pintype "bidirectional"))
      (node (ref "M916_14") (pin "K2") (pinfunction "P$2_K2") (pintype "bidirectional"))
    )
    (net (code "286") (name "N$136") (class "Default")
      (node (ref "M916_5") (pin "D2") (pinfunction "P$2_D2") (pintype "bidirectional"))
      (node (ref "M916_5") (pin "J2") (pinfunction "P$2_J2") (pintype "bidirectional"))
    )
    (net (code "287") (name "N$137") (class "Default")
      (node (ref "IC13") (pin "6") (pinfunction "O_6") (pintype "output"))
      (node (ref "IC4") (pin "13") (pinfunction "I_13") (pintype "input"))
    )
    (net (code "288") (name "N$138") (class "Default")
      (node (ref "IC13") (pin "5") (pinfunction "I1_5") (pintype "input"))
      (node (ref "IC9") (pin "6") (pinfunction "O_6") (pintype "output"))
    )
    (net (code "289") (name "N$139") (class "Default")
      (node (ref "IC13") (pin "3") (pinfunction "O_3") (pintype "output"))
      (node (ref "IC13") (pin "4") (pinfunction "I0_4") (pintype "input"))
    )
    (net (code "290") (name "N$140") (class "Default")
      (node (ref "M916_5") (pin "E2") (pinfunction "P$2_E2") (pintype "bidirectional"))
      (node (ref "M916_5") (pin "K2") (pinfunction "P$2_K2") (pintype "bidirectional"))
    )
    (net (code "291") (name "N$142") (class "Default")
      (node (ref "IC102") (pin "4") (pinfunction "PRE_4") (pintype "input"))
      (node (ref "IC97") (pin "8") (pinfunction "1Y_8") (pintype "output"))
    )
    (net (code "292") (name "N$146") (class "Default")
      (node (ref "IC100") (pin "4") (pinfunction "PRE_4") (pintype "input"))
      (node (ref "IC96") (pin "6") (pinfunction "2Y_6") (pintype "output"))
    )
    (net (code "293") (name "N$147") (class "Default")
      (node (ref "IC100") (pin "10") (pinfunction "PRE_10") (pintype "input"))
      (node (ref "IC98") (pin "8") (pinfunction "1Y_8") (pintype "output"))
    )
    (net (code "294") (name "N$148") (class "Default")
      (node (ref "IC101") (pin "4") (pinfunction "PRE_4") (pintype "input"))
      (node (ref "IC97") (pin "6") (pinfunction "2Y_6") (pintype "output"))
    )
    (net (code "295") (name "N$150") (class "Default")
      (node (ref "M916_22") (pin "S1") (pinfunction "P$2_S1") (pintype "bidirectional"))
      (node (ref "M916_22") (pin "S2") (pinfunction "P$2_S2") (pintype "bidirectional"))
    )
    (net (code "296") (name "N$151") (class "Default")
      (node (ref "M916_22") (pin "R2") (pinfunction "P$2_R2") (pintype "bidirectional"))
      (node (ref "M916_22") (pin "V2") (pinfunction "P$2_V2") (pintype "bidirectional"))
    )
    (net (code "297") (name "N$153") (class "Default")
      (node (ref "IC11") (pin "8") (pinfunction "O_8") (pintype "output"))
      (node (ref "IC12") (pin "2") (pinfunction "I1_2") (pintype "input"))
    )
    (net (code "298") (name "N$155") (class "Default")
      (node (ref "IC105") (pin "8") (pinfunction "1Y_8") (pintype "output"))
      (node (ref "IC113") (pin "12") (pinfunction "D_12") (pintype "input"))
    )
    (net (code "299") (name "N$161") (class "Default")
      (node (ref "IC10") (pin "6") (pinfunction "O_6") (pintype "output"))
      (node (ref "IC14") (pin "1") (pinfunction "I_1") (pintype "input"))
    )
    (net (code "300") (name "N$162") (class "Default")
      (node (ref "IC13") (pin "10") (pinfunction "I1_10") (pintype "input"))
      (node (ref "IC13") (pin "12") (pinfunction "I0_12") (pintype "input"))
      (node (ref "IC14") (pin "2") (pinfunction "O_2") (pintype "output"))
    )
    (net (code "301") (name "N$185") (class "Default")
      (node (ref "IC103") (pin "6") (pinfunction "2Y_6") (pintype "output"))
      (node (ref "IC113") (pin "2") (pinfunction "D_2") (pintype "input"))
    )
    (net (code "302") (name "N$193") (class "Default")
      (node (ref "IC104") (pin "6") (pinfunction "2Y_6") (pintype "output"))
      (node (ref "IC114") (pin "2") (pinfunction "D_2") (pintype "input"))
    )
    (net (code "303") (name "PAR") (class "Default")
      (node (ref "IC7") (pin "6") (pinfunction "~{Q}_6") (pintype "output"))
      (node (ref "M916_9") (pin "T1") (pinfunction "P$2_T1") (pintype "bidirectional"))
    )
    (net (code "304") (name "PC+ES") (class "Default")
      (node (ref "IC13") (pin "8") (pinfunction "O_8") (pintype "output"))
      (node (ref "IC14") (pin "9") (pinfunction "I_9") (pintype "input"))
    )
    (net (code "305") (name "PWR_CLR") (class "Default")
      (node (ref "IC93") (pin "6") (pinfunction "O_6") (pintype "output"))
    )
    (net (code "306") (name "RD+WD") (class "Default")
      (node (ref "IC109") (pin "2") (pinfunction "I1_2") (pintype "input"))
      (node (ref "IC60") (pin "8") (pinfunction "O_8") (pintype "output"))
      (node (ref "IC71") (pin "9") (pinfunction "I0_9") (pintype "input"))
      (node (ref "IC9") (pin "4") (pinfunction "I2_4") (pintype "input"))
    )
    (net (code "307") (name "RDD_00") (class "Default")
      (node (ref "IC129") (pin "4") (pinfunction "2C_4") (pintype "input"))
      (node (ref "IC129") (pin "9") (pinfunction "1D_9") (pintype "input"))
      (node (ref "IC63") (pin "12") (pinfunction "D_12") (pintype "input"))
      (node (ref "M916_5") (pin "U2") (pinfunction "P$2_U2") (pintype "bidirectional"))
    )
    (net (code "308") (name "RDD_01") (class "Default")
      (node (ref "IC130") (pin "9") (pinfunction "1D_9") (pintype "input"))
      (node (ref "IC131") (pin "9") (pinfunction "1D_9") (pintype "input"))
      (node (ref "IC64") (pin "2") (pinfunction "D_2") (pintype "input"))
      (node (ref "M916_14") (pin "U2") (pinfunction "P$2_U2") (pintype "bidirectional"))
    )
    (net (code "309") (name "RDD_02") (class "Default")
      (node (ref "IC130") (pin "4") (pinfunction "2C_4") (pintype "input"))
      (node (ref "IC131") (pin "4") (pinfunction "2C_4") (pintype "input"))
      (node (ref "IC62") (pin "12") (pinfunction "D_12") (pintype "input"))
      (node (ref "M916_4") (pin "U2") (pinfunction "P$2_U2") (pintype "bidirectional"))
    )
    (net (code "310") (name "RDMK") (class "Default")
      (node (ref "M916_13") (pin "U2") (pinfunction "P$2_U2") (pintype "bidirectional"))
    )
    (net (code "311") (name "RD_EN") (class "Default")
      (node (ref "IC106") (pin "5") (pinfunction "I1_5") (pintype "input"))
      (node (ref "IC107") (pin "3") (pinfunction "O_3") (pintype "output"))
    )
    (net (code "312") (name "RD_EN_LPB_00-02") (class "Default")
      (node (ref "IC103") (pin "1") (pinfunction "1A_1") (pintype "input"))
      (node (ref "IC112") (pin "6") (pinfunction "O_6") (pintype "output"))
      (node (ref "IC129") (pin "5") (pinfunction "2D_5") (pintype "input"))
      (node (ref "IC130") (pin "5") (pinfunction "2D_5") (pintype "input"))
      (node (ref "IC131") (pin "10") (pinfunction "1E_10") (pintype "input"))
    )
    (net (code "313") (name "RD_EN_LPB_03-05") (class "Default")
      (node (ref "IC105") (pin "2") (pinfunction "2A_2") (pintype "input"))
      (node (ref "IC112") (pin "2") (pinfunction "O_2") (pintype "output"))
      (node (ref "IC129") (pin "10") (pinfunction "1E_10") (pintype "input"))
      (node (ref "IC130") (pin "10") (pinfunction "1E_10") (pintype "input"))
      (node (ref "IC131") (pin "5") (pinfunction "2D_5") (pintype "input"))
    )
    (net (code "314") (name "READ_ALL") (class "Default")
      (node (ref "IC125") (pin "4") (pinfunction "O_4") (pintype "output"))
    )
    (net (code "315") (name "READ_DATA") (class "Default")
      (node (ref "IC106") (pin "4") (pinfunction "I0_4") (pintype "input"))
      (node (ref "IC12") (pin "4") (pinfunction "I0_4") (pintype "input"))
      (node (ref "IC125") (pin "2") (pinfunction "O_2") (pintype "output"))
    )
    (net (code "316") (name "RSTA") (class "Default")
      (node (ref "IC55") (pin "8") (pinfunction "O_8") (pintype "output"))
    )
    (net (code "317") (name "RSTB") (class "Default")
      (node (ref "IC91") (pin "4") (pinfunction "O_4") (pintype "output"))
    )
    (net (code "318") (name "SE") (class "Default")
      (node (ref "IC125") (pin "12") (pinfunction "O_12") (pintype "output"))
    )
    (net (code "319") (name "SEARCH") (class "Default")
      (node (ref "IC106") (pin "1") (pinfunction "I0_1") (pintype "input"))
      (node (ref "IC123") (pin "12") (pinfunction "O_12") (pintype "output"))
    )
    (net (code "320") (name "SEL") (class "Default")
      (node (ref "IC5") (pin "9") (pinfunction "Q_9") (pintype "output"))
      (node (ref "M916_9") (pin "S1") (pinfunction "P$2_S1") (pintype "bidirectional"))
    )
    (net (code "321") (name "SHIFT_CK") (class "Default")
      (node (ref "IC122") (pin "6") (pinfunction "O_6") (pintype "output"))
    )
    (net (code "322") (name "SH_DTB") (class "Default")
      (node (ref "IC100") (pin "11") (pinfunction "CLK_11") (pintype "input"))
      (node (ref "IC100") (pin "3") (pinfunction "CLK_3") (pintype "input"))
      (node (ref "IC101") (pin "11") (pinfunction "CLK_11") (pintype "input"))
      (node (ref "IC101") (pin "3") (pinfunction "CLK_3") (pintype "input"))
      (node (ref "IC102") (pin "11") (pinfunction "CLK_11") (pintype "input"))
      (node (ref "IC102") (pin "3") (pinfunction "CLK_3") (pintype "input"))
      (node (ref "IC13") (pin "2") (pinfunction "I1_2") (pintype "input"))
      (node (ref "IC62") (pin "11") (pinfunction "CLK_11") (pintype "input"))
      (node (ref "IC62") (pin "3") (pinfunction "CLK_3") (pintype "input"))
      (node (ref "IC63") (pin "11") (pinfunction "CLK_11") (pintype "input"))
      (node (ref "IC63") (pin "3") (pinfunction "CLK_3") (pintype "input"))
      (node (ref "IC64") (pin "11") (pinfunction "CLK_11") (pintype "input"))
      (node (ref "IC64") (pin "3") (pinfunction "CLK_3") (pintype "input"))
      (node (ref "IC65") (pin "6") (pinfunction "O_6") (pintype "output"))
    )
    (net (code "323") (name "SH_EN") (class "Default")
      (node (ref "IC103") (pin "2") (pinfunction "2A_2") (pintype "input"))
      (node (ref "IC104") (pin "2") (pinfunction "2A_2") (pintype "input"))
      (node (ref "IC105") (pin "1") (pinfunction "1A_1") (pintype "input"))
      (node (ref "IC15") (pin "2") (pinfunction "O_2") (pintype "output"))
      (node (ref "IC16") (pin "2") (pinfunction "I1_2") (pintype "input"))
    )
    (net (code "324") (name "SH_ST") (class "Default")
      (node (ref "IC112") (pin "11") (pinfunction "I_11") (pintype "input"))
    )
    (net (code "325") (name "SH_ST-B") (class "Default")
      (node (ref "IC120") (pin "8") (pinfunction "O_8") (pintype "output"))
    )
    (net (code "326") (name "SP_DY") (class "Default")
      (node (ref "M916_20") (pin "H2") (pinfunction "P$2_H2") (pintype "bidirectional"))
    )
    (net (code "327") (name "ST_BLK_MK") (class "Default")
      (node (ref "IC99") (pin "13") (pinfunction "I_13") (pintype "input"))
      (node (ref "M916_10") (pin "K1") (pinfunction "P$2_K1") (pintype "bidirectional"))
    )
    (net (code "328") (name "ST_CK") (class "Default")
      (node (ref "IC111") (pin "1") (pinfunction "I_1") (pintype "input"))
      (node (ref "IC12") (pin "12") (pinfunction "I0_12") (pintype "input"))
      (node (ref "M916_10") (pin "P1") (pinfunction "P$2_P1") (pintype "bidirectional"))
      (node (ref "M916_23") (pin "M2") (pinfunction "P$2_M2") (pintype "bidirectional"))
      (node (ref "M916_23") (pin "N2") (pinfunction "P$2_N2") (pintype "bidirectional"))
      (node (ref "M916_23") (pin "P2") (pinfunction "P$2_P2") (pintype "bidirectional"))
    )
    (net (code "329") (name "ST_CK_0P") (class "Default")
      (node (ref "IC109") (pin "13") (pinfunction "I2_13") (pintype "input"))
      (node (ref "IC71") (pin "13") (pinfunction "I3_13") (pintype "input"))
      (node (ref "IC99") (pin "4") (pinfunction "O_4") (pintype "output"))
    )
    (net (code "330") (name "ST_DATA") (class "Default")
      (node (ref "IC111") (pin "3") (pinfunction "I_3") (pintype "input"))
      (node (ref "IC120") (pin "6") (pinfunction "O_6") (pintype "output"))
      (node (ref "IC70") (pin "1") (pinfunction "I0_1") (pintype "input"))
    )
    (net (code "331") (name "ST_FINAL") (class "Default")
      (node (ref "IC10") (pin "10") (pinfunction "I1_10") (pintype "input"))
      (node (ref "IC90") (pin "12") (pinfunction "I0_12") (pintype "input"))
      (node (ref "M916_10") (pin "N1") (pinfunction "P$2_N1") (pintype "bidirectional"))
    )
    (net (code "332") (name "ST_IDLE") (class "Default")
      (node (ref "IC111") (pin "5") (pinfunction "I_5") (pintype "input"))
      (node (ref "M916_10") (pin "R1") (pinfunction "P$2_R1") (pintype "bidirectional"))
    )
    (net (code "333") (name "ST_REV_CK") (class "Default")
      (node (ref "IC140") (pin "4") (pinfunction "I2_4") (pintype "input"))
      (node (ref "IC140") (pin "5") (pinfunction "I3_5") (pintype "input"))
      (node (ref "IC68") (pin "5") (pinfunction "I2_5") (pintype "input"))
      (node (ref "IC90") (pin "9") (pinfunction "I0_9") (pintype "input"))
      (node (ref "IC99") (pin "9") (pinfunction "I_9") (pintype "input"))
      (node (ref "M916_10") (pin "L1") (pinfunction "P$2_L1") (pintype "bidirectional"))
    )
    (net (code "334") (name "SWTM") (class "Default")
      (node (ref "IC104") (pin "10") (pinfunction "1E_10") (pintype "input"))
      (node (ref "IC110") (pin "2") (pinfunction "I1_2") (pintype "input"))
      (node (ref "IC117") (pin "4") (pinfunction "I0_4") (pintype "input"))
      (node (ref "IC2") (pin "4") (pinfunction "I1_4") (pintype "input"))
      (node (ref "IC54") (pin "11") (pinfunction "I_11") (pintype "input"))
      (node (ref "IC55") (pin "4") (pinfunction "O_4") (pintype "output"))
      (node (ref "M916_10") (pin "V2") (pinfunction "P$2_V2") (pintype "bidirectional"))
    )
    (net (code "335") (name "SYNC") (class "Default")
      (node (ref "IC66") (pin "10") (pinfunction "I1_10") (pintype "input"))
      (node (ref "IC66") (pin "9") (pinfunction "I0_9") (pintype "input"))
    )
    (net (code "336") (name "SYNC_EN") (class "Default")
      (node (ref "IC69") (pin "12") (pinfunction "O_12") (pintype "output"))
    )
    (net (code "337") (name "T3") (class "Default")
      (node (ref "IC123") (pin "2") (pinfunction "O_2") (pintype "output"))
      (node (ref "IC139") (pin "10") (pinfunction "I1_10") (pintype "input"))
      (node (ref "IC139") (pin "12") (pinfunction "I2_12") (pintype "input"))
    )
    (net (code "338") (name "TIM") (class "Default")
      (node (ref "IC6") (pin "5") (pinfunction "Q_5") (pintype "output"))
      (node (ref "M916_9") (pin "U1") (pinfunction "P$2_U1") (pintype "bidirectional"))
    )
    (net (code "339") (name "TM_EN") (class "Default")
      (node (ref "IC111") (pin "9") (pinfunction "I_9") (pintype "input"))
      (node (ref "IC117") (pin "11") (pinfunction "O_11") (pintype "output"))
      (node (ref "IC119") (pin "9") (pinfunction "I0_9") (pintype "input"))
      (node (ref "IC121") (pin "1") (pinfunction "I0_1") (pintype "input"))
      (node (ref "M916_13") (pin "R2") (pinfunction "P$2_R2") (pintype "bidirectional"))
      (node (ref "M916_3") (pin "R2") (pinfunction "P$2_R2") (pintype "bidirectional"))
    )
    (net (code "340") (name "TP00") (class "Default")
      (node (ref "IC116") (pin "5") (pinfunction "I1_5") (pintype "input"))
      (node (ref "IC18") (pin "8") (pinfunction "O_8") (pintype "output"))
      (node (ref "IC5") (pin "3") (pinfunction "CLK_3") (pintype "input"))
      (node (ref "IC66") (pin "12") (pinfunction "I2_12") (pintype "input"))
      (node (ref "IC66") (pin "13") (pinfunction "I3_13") (pintype "input"))
      (node (ref "IC66") (pin "2") (pinfunction "I1_2") (pintype "input"))
      (node (ref "IC73") (pin "11") (pinfunction "CLK_11") (pintype "input"))
      (node (ref "IC73") (pin "3") (pinfunction "CLK_3") (pintype "input"))
      (node (ref "IC74") (pin "3") (pinfunction "CLK_3") (pintype "input"))
      (node (ref "IC78") (pin "2") (pinfunction "I1_2") (pintype "input"))
      (node (ref "M916_2") (pin "M2") (pinfunction "P$2_M2") (pintype "bidirectional"))
      (node (ref "M916_2") (pin "N2") (pinfunction "P$2_N2") (pintype "bidirectional"))
      (node (ref "M916_2") (pin "P2") (pinfunction "P$2_P2") (pintype "bidirectional"))
    )
    (net (code "341") (name "TP00_A") (class "Default")
      (node (ref "IC109") (pin "4") (pinfunction "I1_4") (pintype "input"))
      (node (ref "IC19") (pin "6") (pinfunction "O_6") (pintype "output"))
      (node (ref "IC65") (pin "10") (pinfunction "I1_10") (pintype "input"))
    )
    (net (code "342") (name "TP01") (class "Default")
      (node (ref "IC106") (pin "10") (pinfunction "I1_10") (pintype "input"))
      (node (ref "IC116") (pin "2") (pinfunction "I1_2") (pintype "input"))
      (node (ref "IC16") (pin "10") (pinfunction "I1_10") (pintype "input"))
      (node (ref "IC20") (pin "6") (pinfunction "O_6") (pintype "output"))
      (node (ref "M916_12") (pin "M2") (pinfunction "P$2_M2") (pintype "bidirectional"))
      (node (ref "M916_12") (pin "N2") (pinfunction "P$2_N2") (pintype "bidirectional"))
      (node (ref "M916_12") (pin "P2") (pinfunction "P$2_P2") (pintype "bidirectional"))
    )
    (net (code "343") (name "TP01_A") (class "Default")
      (node (ref "IC117") (pin "10") (pinfunction "I1_10") (pintype "input"))
      (node (ref "IC20") (pin "8") (pinfunction "O_8") (pintype "output"))
      (node (ref "IC72") (pin "12") (pinfunction "I2_12") (pintype "input"))
    )
    (net (code "344") (name "T_TRK") (class "Default")
      (node (ref "IC118") (pin "2") (pinfunction "I1_2") (pintype "input"))
      (node (ref "IC61") (pin "13") (pinfunction "I1_13") (pintype "input"))
      (node (ref "M916_20") (pin "S1") (pinfunction "P$2_S1") (pintype "bidirectional"))
      (node (ref "M916_20") (pin "U1") (pinfunction "P$2_U1") (pintype "bidirectional"))
      (node (ref "M916_3") (pin "U2") (pinfunction "P$2_U2") (pintype "bidirectional"))
    )
    (net (code "345") (name "U+M_DY") (class "Default")
      (node (ref "M916_20") (pin "K1") (pinfunction "P$2_K1") (pintype "bidirectional"))
    )
    (net (code "346") (name "USR_00") (class "Default")
      (node (ref "IC1") (pin "22") (pinfunction "B_22") (pintype "input"))
      (node (ref "IC56") (pin "12") (pinfunction "Q_12") (pintype "output"))
      (node (ref "M916_9") (pin "A1") (pinfunction "P$2_A1") (pintype "bidirectional"))
    )
    (net (code "347") (name "USR_01") (class "Default")
      (node (ref "IC1") (pin "21") (pinfunction "C_21") (pintype "input"))
      (node (ref "IC56") (pin "9") (pinfunction "Q_9") (pintype "output"))
      (node (ref "M916_9") (pin "B1") (pinfunction "P$2_B1") (pintype "bidirectional"))
    )
    (net (code "348") (name "USR_02") (class "Default")
      (node (ref "IC1") (pin "20") (pinfunction "D_20") (pintype "input"))
      (node (ref "IC57") (pin "12") (pinfunction "Q_12") (pintype "output"))
      (node (ref "M916_9") (pin "C1") (pinfunction "P$2_C1") (pintype "bidirectional"))
    )
    (net (code "349") (name "USR_02_") (class "Default")
      (node (ref "IC1") (pin "18") (pinfunction "G1_18") (pintype "input"))
      (node (ref "IC1") (pin "19") (pinfunction "G2_19") (pintype "input"))
      (node (ref "IC2") (pin "12") (pinfunction "O_12") (pintype "output"))
    )
    (net (code "350") (name "UTS") (class "Default")
      (node (ref "IC11") (pin "5") (pinfunction "I1_5") (pintype "input"))
      (node (ref "IC114") (pin "8") (pinfunction "~{Q}_8") (pintype "output"))
      (node (ref "IC78") (pin "9") (pinfunction "I0_9") (pintype "input"))
      (node (ref "M916_10") (pin "J1") (pinfunction "P$2_J1") (pintype "bidirectional"))
    )
    (net (code "351") (name "VCC") (class "Default")
      (node (ref "IC103") (pin "11") (pinfunction "1F_11") (pintype "input"))
      (node (ref "IC103") (pin "13") (pinfunction "1C_13") (pintype "input"))
      (node (ref "IC104") (pin "11") (pinfunction "1F_11") (pintype "input"))
      (node (ref "IC104") (pin "13") (pinfunction "1C_13") (pintype "input"))
      (node (ref "IC105") (pin "11") (pinfunction "1F_11") (pintype "input"))
      (node (ref "IC105") (pin "13") (pinfunction "1C_13") (pintype "input"))
      (node (ref "IC129") (pin "11") (pinfunction "1F_11") (pintype "input"))
      (node (ref "IC129") (pin "13") (pinfunction "1C_13") (pintype "input"))
      (node (ref "IC130") (pin "11") (pinfunction "1F_11") (pintype "input"))
      (node (ref "IC130") (pin "13") (pinfunction "1C_13") (pintype "input"))
      (node (ref "IC131") (pin "11") (pinfunction "1F_11") (pintype "input"))
      (node (ref "IC131") (pin "13") (pinfunction "1C_13") (pintype "input"))
      (node (ref "IC96") (pin "11") (pinfunction "1F_11") (pintype "input"))
      (node (ref "IC96") (pin "13") (pinfunction "1C_13") (pintype "input"))
      (node (ref "IC97") (pin "11") (pinfunction "1F_11") (pintype "input"))
      (node (ref "IC97") (pin "13") (pinfunction "1C_13") (pintype "input"))
      (node (ref "IC98") (pin "11") (pinfunction "1F_11") (pintype "input"))
      (node (ref "IC98") (pin "13") (pinfunction "1C_13") (pintype "input"))
      (node (ref "M916_1") (pin "A2") (pinfunction "P$2_A2") (pintype "bidirectional"))
      (node (ref "M916_12") (pin "A2") (pinfunction "P$2_A2") (pintype "bidirectional"))
      (node (ref "M916_13") (pin "A2") (pinfunction "P$2_A2") (pintype "bidirectional"))
      (node (ref "M916_14") (pin "A2") (pinfunction "P$2_A2") (pintype "bidirectional"))
      (node (ref "M916_15") (pin "A2") (pinfunction "P$2_A2") (pintype "bidirectional"))
      (node (ref "M916_16") (pin "A2") (pinfunction "P$2_A2") (pintype "bidirectional"))
      (node (ref "M916_19") (pin "A2") (pinfunction "P$2_A2") (pintype "bidirectional"))
      (node (ref "M916_2") (pin "A2") (pinfunction "P$2_A2") (pintype "bidirectional"))
      (node (ref "M916_20") (pin "A2") (pinfunction "P$2_A2") (pintype "bidirectional"))
      (node (ref "M916_21") (pin "A2") (pinfunction "P$2_A2") (pintype "bidirectional"))
      (node (ref "M916_22") (pin "A2") (pinfunction "P$2_A2") (pintype "bidirectional"))
      (node (ref "M916_23") (pin "A2") (pinfunction "P$2_A2") (pintype "bidirectional"))
      (node (ref "M916_3") (pin "A2") (pinfunction "P$2_A2") (pintype "bidirectional"))
      (node (ref "M916_4") (pin "A2") (pinfunction "P$2_A2") (pintype "bidirectional"))
      (node (ref "M916_5") (pin "A2") (pinfunction "P$2_A2") (pintype "bidirectional"))
      (node (ref "M916_6") (pin "A2") (pinfunction "P$2_A2") (pintype "bidirectional"))
      (node (ref "M916_7") (pin "A2") (pinfunction "P$2_A2") (pintype "bidirectional"))
    )
    (net (code "352") (name "W+UTS") (class "Default")
      (node (ref "IC109") (pin "8") (pinfunction "O_8") (pintype "output"))
      (node (ref "IC18") (pin "1") (pinfunction "I0_1") (pintype "input"))
      (node (ref "IC19") (pin "13") (pinfunction "I3_13") (pintype "input"))
    )
    (net (code "353") (name "W-INH") (class "Default")
      (node (ref "IC7") (pin "8") (pinfunction "~{Q}_8") (pintype "output"))
    )
    (net (code "354") (name "W01") (class "Default")
      (node (ref "M916_10") (pin "J2") (pinfunction "P$2_J2") (pintype "bidirectional"))
    )
    (net (code "355") (name "W02") (class "Default")
      (node (ref "M916_10") (pin "K2") (pinfunction "P$2_K2") (pintype "bidirectional"))
    )
    (net (code "356") (name "W03") (class "Default")
      (node (ref "M916_10") (pin "L2") (pinfunction "P$2_L2") (pintype "bidirectional"))
    )
    (net (code "357") (name "W04") (class "Default")
      (node (ref "M916_10") (pin "M2") (pinfunction "P$2_M2") (pintype "bidirectional"))
    )
    (net (code "358") (name "W05") (class "Default")
      (node (ref "M916_10") (pin "N2") (pinfunction "P$2_N2") (pintype "bidirectional"))
    )
    (net (code "359") (name "W06") (class "Default")
      (node (ref "M916_10") (pin "P2") (pinfunction "P$2_P2") (pintype "bidirectional"))
    )
    (net (code "360") (name "W07") (class "Default")
      (node (ref "M916_10") (pin "R2") (pinfunction "P$2_R2") (pintype "bidirectional"))
    )
    (net (code "361") (name "W08") (class "Default")
      (node (ref "M916_10") (pin "S2") (pinfunction "P$2_S2") (pintype "bidirectional"))
    )
    (net (code "362") (name "W09") (class "Default")
      (node (ref "M916_10") (pin "T2") (pinfunction "P$2_T2") (pintype "bidirectional"))
    )
    (net (code "363") (name "WB00") (class "Default")
      (node (ref "IC113") (pin "6") (pinfunction "~{Q}_6") (pintype "output"))
      (node (ref "IC129") (pin "2") (pinfunction "2A_2") (pintype "input"))
      (node (ref "M916_13") (pin "N2") (pinfunction "P$2_N2") (pintype "bidirectional"))
      (node (ref "M916_5") (pin "N2") (pinfunction "P$2_N2") (pintype "bidirectional"))
      (node (ref "M916_9") (pin "P2") (pinfunction "P$2_P2") (pintype "bidirectional"))
    )
    (net (code "364") (name "WB01") (class "Default")
      (node (ref "IC113") (pin "8") (pinfunction "~{Q}_8") (pintype "output"))
      (node (ref "IC131") (pin "1") (pinfunction "1A_1") (pintype "input"))
      (node (ref "M916_14") (pin "N2") (pinfunction "P$2_N2") (pintype "bidirectional"))
      (node (ref "M916_9") (pin "R2") (pinfunction "P$2_R2") (pintype "bidirectional"))
    )
    (net (code "365") (name "WB02") (class "Default")
      (node (ref "IC114") (pin "6") (pinfunction "~{Q}_6") (pintype "output"))
      (node (ref "IC130") (pin "2") (pinfunction "2A_2") (pintype "input"))
      (node (ref "M916_4") (pin "N2") (pinfunction "P$2_N2") (pintype "bidirectional"))
      (node (ref "M916_9") (pin "S2") (pinfunction "P$2_S2") (pintype "bidirectional"))
    )
    (net (code "366") (name "WC") (class "Default")
      (node (ref "IC137") (pin "9") (pinfunction "Q_9") (pintype "output"))
      (node (ref "IC66") (pin "1") (pinfunction "I0_1") (pintype "input"))
      (node (ref "IC68") (pin "1") (pinfunction "I0_1") (pintype "input"))
      (node (ref "M916_10") (pin "H1") (pinfunction "P$2_H1") (pintype "bidirectional"))
    )
    (net (code "367") (name "WC0") (class "Default")
      (node (ref "IC79") (pin "8") (pinfunction "O_8") (pintype "output"))
      (node (ref "IC93") (pin "1") (pinfunction "I_1") (pintype "input"))
    )
    (net (code "368") (name "WRITE_ALL") (class "Default")
      (node (ref "IC125") (pin "8") (pinfunction "O_8") (pintype "output"))
      (node (ref "IC68") (pin "13") (pinfunction "I2_13") (pintype "input"))
      (node (ref "IC7") (pin "11") (pinfunction "CLK_11") (pintype "input"))
      (node (ref "IC70") (pin "9") (pinfunction "I0_9") (pintype "input"))
    )
    (net (code "369") (name "WRITE_DATA") (class "Default")
      (node (ref "IC10") (pin "9") (pinfunction "I0_9") (pintype "input"))
      (node (ref "IC125") (pin "6") (pinfunction "O_6") (pintype "output"))
      (node (ref "IC68") (pin "4") (pinfunction "I1_4") (pintype "input"))
      (node (ref "IC70") (pin "2") (pinfunction "I1_2") (pintype "input"))
      (node (ref "IC71") (pin "4") (pinfunction "I2_4") (pintype "input"))
    )
    (net (code "370") (name "WRITE_OK") (class "Default")
      (node (ref "IC122") (pin "9") (pinfunction "I_9") (pintype "input"))
      (node (ref "IC2") (pin "5") (pinfunction "I2_5") (pintype "input"))
      (node (ref "IC78") (pin "10") (pinfunction "I1_10") (pintype "input"))
      (node (ref "M916_6") (pin "D2") (pinfunction "P$2_D2") (pintype "bidirectional"))
    )
    (net (code "371") (name "WRITE_OK+UTS") (class "Default")
      (node (ref "IC70") (pin "13") (pinfunction "I3_13") (pintype "input"))
      (node (ref "IC70") (pin "5") (pinfunction "I3_5") (pintype "input"))
    )
    (net (code "372") (name "WRTM") (class "Default")
      (node (ref "IC104") (pin "1") (pinfunction "1A_1") (pintype "input"))
      (node (ref "IC110") (pin "1") (pinfunction "I0_1") (pintype "input"))
      (node (ref "IC125") (pin "10") (pinfunction "O_10") (pintype "output"))
      (node (ref "IC2") (pin "3") (pinfunction "I0_3") (pintype "input"))
    )
    (net (code "373") (name "WRTM+FR03") (class "Default")
      (node (ref "IC108") (pin "11") (pinfunction "I2_11") (pintype "input"))
      (node (ref "IC110") (pin "5") (pinfunction "I2_5") (pintype "input"))
      (node (ref "IC60") (pin "3") (pinfunction "O_3") (pintype "output"))
    )
    (net (code "374") (name "WR_EN") (class "Default")
      (node (ref "IC103") (pin "10") (pinfunction "1E_10") (pintype "input"))
      (node (ref "IC105") (pin "5") (pinfunction "2D_5") (pintype "input"))
      (node (ref "IC109") (pin "3") (pinfunction "I0_3") (pintype "input"))
      (node (ref "IC115") (pin "6") (pinfunction "~{Q}_6") (pintype "output"))
      (node (ref "IC116") (pin "1") (pinfunction "I0_1") (pintype "input"))
      (node (ref "IC117") (pin "5") (pinfunction "I1_5") (pintype "input"))
      (node (ref "IC129") (pin "12") (pinfunction "1B_12") (pintype "input"))
      (node (ref "IC129") (pin "3") (pinfunction "2B_3") (pintype "input"))
      (node (ref "IC130") (pin "12") (pinfunction "1B_12") (pintype "input"))
      (node (ref "IC130") (pin "3") (pinfunction "2B_3") (pintype "input"))
      (node (ref "IC131") (pin "12") (pinfunction "1B_12") (pintype "input"))
      (node (ref "IC131") (pin "3") (pinfunction "2B_3") (pintype "input"))
      (node (ref "M916_10") (pin "F1") (pinfunction "P$2_F1") (pintype "bidirectional"))
      (node (ref "M916_14") (pin "R2") (pinfunction "P$2_R2") (pintype "bidirectional"))
      (node (ref "M916_4") (pin "R2") (pinfunction "P$2_R2") (pintype "bidirectional"))
      (node (ref "M916_5") (pin "R2") (pinfunction "P$2_R2") (pintype "bidirectional"))
    )
    (net (code "375") (name "XOR_TO_LPB") (class "Default")
      (node (ref "IC103") (pin "12") (pinfunction "1B_12") (pintype "input"))
      (node (ref "IC103") (pin "9") (pinfunction "1D_9") (pintype "input"))
      (node (ref "IC105") (pin "3") (pinfunction "2B_3") (pintype "input"))
      (node (ref "IC105") (pin "4") (pinfunction "2C_4") (pintype "input"))
      (node (ref "IC140") (pin "8") (pinfunction "O_8") (pintype "output"))
    )
    (net (code "376") (name "XSAD") (class "Default")
      (node (ref "IC14") (pin "10") (pinfunction "O_10") (pintype "output"))
      (node (ref "IC9") (pin "5") (pinfunction "I3_5") (pintype "input"))
    )
    (net (code "377") (name "XSA_DY") (class "Default")
      (node (ref "IC123") (pin "8") (pinfunction "O_8") (pintype "output"))
      (node (ref "IC5") (pin "11") (pinfunction "CLK_11") (pintype "input"))
      (node (ref "IC76") (pin "11") (pinfunction "CLK_11") (pintype "input"))
      (node (ref "IC76") (pin "3") (pinfunction "CLK_3") (pintype "input"))
    )
    (net (code "378") (name "XSTA") (class "Default")
      (node (ref "IC137") (pin "11") (pinfunction "CLK_11") (pintype "input"))
      (node (ref "IC55") (pin "12") (pinfunction "O_12") (pintype "output"))
      (node (ref "IC56") (pin "1") (pinfunction "CLK_1") (pintype "input"))
      (node (ref "IC56") (pin "5") (pinfunction "CLK_5") (pintype "input"))
      (node (ref "IC57") (pin "1") (pinfunction "CLK_1") (pintype "input"))
      (node (ref "IC57") (pin "5") (pinfunction "CLK_5") (pintype "input"))
      (node (ref "IC58") (pin "1") (pinfunction "CLK_1") (pintype "input"))
      (node (ref "IC58") (pin "5") (pinfunction "CLK_5") (pintype "input"))
      (node (ref "IC94") (pin "1") (pinfunction "CLK_1") (pintype "input"))
      (node (ref "IC94") (pin "5") (pinfunction "CLK_5") (pintype "input"))
      (node (ref "IC95") (pin "1") (pinfunction "CLK_1") (pintype "input"))
      (node (ref "IC95") (pin "5") (pinfunction "CLK_5") (pintype "input"))
      (node (ref "M916_19") (pin "M2") (pinfunction "P$2_M2") (pintype "bidirectional"))
      (node (ref "M916_19") (pin "N2") (pinfunction "P$2_N2") (pintype "bidirectional"))
      (node (ref "M916_19") (pin "P2") (pinfunction "P$2_P2") (pintype "bidirectional"))
    )
    (net (code "379") (name "unconnected-(IC1A-8-Pad9)") (class "Default")
      (node (ref "IC1") (pin "9") (pinfunction "8_9") (pintype "output"))
    )
    (net (code "380") (name "unconnected-(IC1A-9-Pad10)") (class "Default")
      (node (ref "IC1") (pin "10") (pinfunction "9_10") (pintype "output"))
    )
    (net (code "381") (name "unconnected-(IC1A-10-Pad11)") (class "Default")
      (node (ref "IC1") (pin "11") (pinfunction "10_11") (pintype "output"))
    )
    (net (code "382") (name "unconnected-(IC1A-11-Pad13)") (class "Default")
      (node (ref "IC1") (pin "13") (pinfunction "11_13") (pintype "output"))
    )
    (net (code "383") (name "unconnected-(IC1A-12-Pad14)") (class "Default")
      (node (ref "IC1") (pin "14") (pinfunction "12_14") (pintype "output"))
    )
    (net (code "384") (name "unconnected-(IC1A-13-Pad15)") (class "Default")
      (node (ref "IC1") (pin "15") (pinfunction "13_15") (pintype "output"))
    )
    (net (code "385") (name "unconnected-(IC1A-14-Pad16)") (class "Default")
      (node (ref "IC1") (pin "16") (pinfunction "14_16") (pintype "output"))
    )
    (net (code "386") (name "unconnected-(IC1A-15-Pad17)") (class "Default")
      (node (ref "IC1") (pin "17") (pinfunction "15_17") (pintype "output"))
    )
    (net (code "387") (name "unconnected-(IC124A-8-Pad9)") (class "Default")
      (node (ref "IC124") (pin "9") (pinfunction "8_9") (pintype "output"))
    )
    (net (code "388") (name "unconnected-(IC124A-9-Pad10)") (class "Default")
      (node (ref "IC124") (pin "10") (pinfunction "9_10") (pintype "output"))
    )
    (net (code "389") (name "unconnected-(IC124A-10-Pad11)") (class "Default")
      (node (ref "IC124") (pin "11") (pinfunction "10_11") (pintype "output"))
    )
    (net (code "390") (name "unconnected-(IC124A-11-Pad13)") (class "Default")
      (node (ref "IC124") (pin "13") (pinfunction "11_13") (pintype "output"))
    )
    (net (code "391") (name "unconnected-(IC124A-12-Pad14)") (class "Default")
      (node (ref "IC124") (pin "14") (pinfunction "12_14") (pintype "output"))
    )
    (net (code "392") (name "unconnected-(IC124A-13-Pad15)") (class "Default")
      (node (ref "IC124") (pin "15") (pinfunction "13_15") (pintype "output"))
    )
    (net (code "393") (name "unconnected-(IC124A-14-Pad16)") (class "Default")
      (node (ref "IC124") (pin "16") (pinfunction "14_16") (pintype "output"))
    )
    (net (code "394") (name "unconnected-(IC124A-15-Pad17)") (class "Default")
      (node (ref "IC124") (pin "17") (pinfunction "15_17") (pintype "output"))
    )
    (net (code "395") (name "unconnected-(SV3-34-PadNN)") (class "Default")
      (node (ref "SV3") (pin "NN") (pinfunction "34_NN") (pintype "bidirectional"))
    )
    (net (code "396") (name "unconnected-(SV3-38-PadTT)") (class "Default")
      (node (ref "SV3") (pin "TT") (pinfunction "38_TT") (pintype "bidirectional"))
    )
    (net (code "397") (name "unconnected-(SV4-10-PadL)") (class "Default")
      (node (ref "SV4") (pin "L") (pinfunction "10_L") (pintype "bidirectional"))
    )
    (net (code "398") (name "unconnected-(SV4-14-PadR)") (class "Default")
      (node (ref "SV4") (pin "R") (pinfunction "14_R") (pintype "bidirectional"))
    )
    (net (code "399") (name "unconnected-(SV4-34-PadNN)") (class "Default")
      (node (ref "SV4") (pin "NN") (pinfunction "34_NN") (pintype "bidirectional"))
    )
    (net (code "400") (name "unconnected-(SV4-38-PadTT)") (class "Default")
      (node (ref "SV4") (pin "TT") (pinfunction "38_TT") (pintype "bidirectional"))
    )
    (net (code "401") (name "unconnected-(SV8-34-PadNN)") (class "Default")
      (node (ref "SV8") (pin "NN") (pinfunction "34_NN") (pintype "bidirectional"))
    )
    (net (code "402") (name "unconnected-(SV8-38-PadTT)") (class "Default")
      (node (ref "SV8") (pin "TT") (pinfunction "38_TT") (pintype "bidirectional"))
    )
    (net (code "403") (name "unconnected-(SV9-10-PadL)") (class "Default")
      (node (ref "SV9") (pin "L") (pinfunction "10_L") (pintype "bidirectional"))
    )
    (net (code "404") (name "unconnected-(SV9-14-PadR)") (class "Default")
      (node (ref "SV9") (pin "R") (pinfunction "14_R") (pintype "bidirectional"))
    )
    (net (code "405") (name "unconnected-(SV9-34-PadNN)") (class "Default")
      (node (ref "SV9") (pin "NN") (pinfunction "34_NN") (pintype "bidirectional"))
    )
    (net (code "406") (name "unconnected-(SV9-38-PadTT)") (class "Default")
      (node (ref "SV9") (pin "TT") (pinfunction "38_TT") (pintype "bidirectional"))
    )
    (net (code "407") (name "~{0_TO_AC}") (class "Default")
      (node (ref "IC45") (pin "11") (pinfunction "I0_11") (pintype "input"))
      (node (ref "IC55") (pin "2") (pinfunction "O_2") (pintype "output"))
    )
    (net (code "408") (name "~{0_TO_DTB}") (class "Default")
      (node (ref "IC100") (pin "1") (pinfunction "CLR_1") (pintype "input"))
      (node (ref "IC100") (pin "13") (pinfunction "CLR_13") (pintype "input"))
      (node (ref "IC101") (pin "1") (pinfunction "CLR_1") (pintype "input"))
      (node (ref "IC101") (pin "13") (pinfunction "CLR_13") (pintype "input"))
      (node (ref "IC102") (pin "1") (pinfunction "CLR_1") (pintype "input"))
      (node (ref "IC102") (pin "13") (pinfunction "CLR_13") (pintype "input"))
      (node (ref "IC62") (pin "1") (pinfunction "CLR_1") (pintype "input"))
      (node (ref "IC62") (pin "13") (pinfunction "CLR_13") (pintype "input"))
      (node (ref "IC63") (pin "1") (pinfunction "CLR_1") (pintype "input"))
      (node (ref "IC63") (pin "13") (pinfunction "CLR_13") (pintype "input"))
      (node (ref "IC64") (pin "1") (pinfunction "CLR_1") (pintype "input"))
      (node (ref "IC64") (pin "13") (pinfunction "CLR_13") (pintype "input"))
      (node (ref "IC65") (pin "8") (pinfunction "O_8") (pintype "output"))
    )
    (net (code "409") (name "~{0_TO_EF}") (class "Default")
      (node (ref "IC14") (pin "4") (pinfunction "O_4") (pintype "output"))
      (node (ref "IC5") (pin "1") (pinfunction "CLR_1") (pintype "input"))
      (node (ref "IC5") (pin "13") (pinfunction "CLR_13") (pintype "input"))
      (node (ref "IC6") (pin "1") (pinfunction "CLR_1") (pintype "input"))
      (node (ref "IC6") (pin "10") (pinfunction "PRE_10") (pintype "input"))
      (node (ref "IC7") (pin "4") (pinfunction "PRE_4") (pintype "input"))
    )
    (net (code "410") (name "~{0_TO_LPB}") (class "Default")
      (node (ref "IC126") (pin "2") (pinfunction "CL_2") (pintype "input"))
      (node (ref "IC126") (pin "6") (pinfunction "CL_6") (pintype "input"))
      (node (ref "IC127") (pin "2") (pinfunction "CL_2") (pintype "input"))
      (node (ref "IC127") (pin "6") (pinfunction "CL_6") (pintype "input"))
      (node (ref "IC128") (pin "2") (pinfunction "CL_2") (pintype "input"))
      (node (ref "IC128") (pin "6") (pinfunction "CL_6") (pintype "input"))
      (node (ref "IC140") (pin "6") (pinfunction "O_6") (pintype "output"))
    )
    (net (code "411") (name "~{0_TO_STATE}") (class "Default")
      (node (ref "IC119") (pin "6") (pinfunction "O_6") (pintype "output"))
    )
    (net (code "412") (name "~{0_TO_STA}") (class "Default")
      (node (ref "IC14") (pin "12") (pinfunction "O_12") (pintype "output"))
      (node (ref "IC56") (pin "2") (pinfunction "CL_2") (pintype "input"))
      (node (ref "IC56") (pin "6") (pinfunction "CL_6") (pintype "input"))
      (node (ref "IC57") (pin "2") (pinfunction "CL_2") (pintype "input"))
      (node (ref "IC57") (pin "6") (pinfunction "CL_6") (pintype "input"))
      (node (ref "IC58") (pin "2") (pinfunction "CL_2") (pintype "input"))
      (node (ref "IC58") (pin "6") (pinfunction "CL_6") (pintype "input"))
      (node (ref "IC69") (pin "4") (pinfunction "I1_4") (pintype "input"))
      (node (ref "IC94") (pin "2") (pinfunction "CL_2") (pintype "input"))
      (node (ref "IC94") (pin "6") (pinfunction "CL_6") (pintype "input"))
      (node (ref "IC95") (pin "2") (pinfunction "CL_2") (pintype "input"))
    )
    (net (code "413") (name "~{0_TO_W}") (class "Default")
      (node (ref "IC67") (pin "8") (pinfunction "O_8") (pintype "output"))
    )
    (net (code "414") (name "~{00}") (class "Default")
      (node (ref "IC1") (pin "1") (pinfunction "0_1") (pintype "output"))
      (node (ref "IC3") (pin "1") (pinfunction "I_1") (pintype "input"))
      (node (ref "M916_16") (pin "S2") (pinfunction "P$2_S2") (pintype "bidirectional"))
    )
    (net (code "415") (name "~{01}") (class "Default")
      (node (ref "IC1") (pin "2") (pinfunction "1_2") (pintype "output"))
      (node (ref "IC3") (pin "3") (pinfunction "I_3") (pintype "input"))
      (node (ref "M916_7") (pin "N1") (pinfunction "P$2_N1") (pintype "bidirectional"))
    )
    (net (code "416") (name "~{02}") (class "Default")
      (node (ref "IC1") (pin "3") (pinfunction "2_3") (pintype "output"))
      (node (ref "IC3") (pin "5") (pinfunction "I_5") (pintype "input"))
      (node (ref "M916_7") (pin "D2") (pinfunction "P$2_D2") (pintype "bidirectional"))
    )
    (net (code "417") (name "~{03}") (class "Default")
      (node (ref "IC1") (pin "4") (pinfunction "3_4") (pintype "output"))
      (node (ref "IC3") (pin "9") (pinfunction "I_9") (pintype "input"))
      (node (ref "M916_7") (pin "E2") (pinfunction "P$2_E2") (pintype "bidirectional"))
    )
    (net (code "418") (name "~{04}") (class "Default")
      (node (ref "IC1") (pin "5") (pinfunction "4_5") (pintype "output"))
      (node (ref "IC3") (pin "11") (pinfunction "I_11") (pintype "input"))
      (node (ref "M916_7") (pin "K2") (pinfunction "P$2_K2") (pintype "bidirectional"))
    )
    (net (code "419") (name "~{05}") (class "Default")
      (node (ref "IC1") (pin "6") (pinfunction "5_6") (pintype "output"))
      (node (ref "IC3") (pin "13") (pinfunction "I_13") (pintype "input"))
      (node (ref "M916_7") (pin "L2") (pinfunction "P$2_L2") (pintype "bidirectional"))
    )
    (net (code "420") (name "~{06}") (class "Default")
      (node (ref "IC1") (pin "7") (pinfunction "6_7") (pintype "output"))
      (node (ref "IC4") (pin "1") (pinfunction "I_1") (pintype "input"))
      (node (ref "M916_7") (pin "R2") (pinfunction "P$2_R2") (pintype "bidirectional"))
    )
    (net (code "421") (name "~{07}") (class "Default")
      (node (ref "IC1") (pin "8") (pinfunction "7_8") (pintype "output"))
      (node (ref "IC4") (pin "3") (pinfunction "I_3") (pintype "input"))
      (node (ref "M916_7") (pin "S2") (pinfunction "P$2_S2") (pintype "bidirectional"))
    )
    (net (code "422") (name "~{76}") (class "Default")
      (node (ref "IC141") (pin "1") (pinfunction "I0_1") (pintype "input"))
      (node (ref "IC141") (pin "2") (pinfunction "I1_2") (pintype "input"))
      (node (ref "IC93") (pin "10") (pinfunction "O_10") (pintype "output"))
    )
    (net (code "423") (name "~{77}") (class "Default")
      (node (ref "IC141") (pin "4") (pinfunction "I2_4") (pintype "input"))
      (node (ref "IC141") (pin "5") (pinfunction "I3_5") (pintype "input"))
      (node (ref "IC93") (pin "12") (pinfunction "O_12") (pintype "output"))
    )
    (net (code "424") (name "~{ADDR_ACC}") (class "Default")
      (node (ref "IC122") (pin "10") (pinfunction "O_10") (pintype "output"))
      (node (ref "IC61") (pin "4") (pinfunction "I0_4") (pintype "input"))
    )
    (net (code "425") (name "~{B-BRK}") (class "Default")
      (node (ref "IC21") (pin "12") (pinfunction "I1_12") (pintype "input"))
      (node (ref "IC21") (pin "3") (pinfunction "I1_3") (pintype "input"))
      (node (ref "IC21") (pin "6") (pinfunction "I1_6") (pintype "input"))
      (node (ref "IC21") (pin "9") (pinfunction "I1_9") (pintype "input"))
      (node (ref "IC22") (pin "12") (pinfunction "I1_12") (pintype "input"))
      (node (ref "IC22") (pin "3") (pinfunction "I1_3") (pintype "input"))
      (node (ref "IC22") (pin "6") (pinfunction "I1_6") (pintype "input"))
      (node (ref "IC22") (pin "9") (pinfunction "I1_9") (pintype "input"))
      (node (ref "IC23") (pin "12") (pinfunction "I1_12") (pintype "input"))
      (node (ref "IC23") (pin "3") (pinfunction "I1_3") (pintype "input"))
      (node (ref "IC23") (pin "6") (pinfunction "I1_6") (pintype "input"))
      (node (ref "IC23") (pin "9") (pinfunction "I1_9") (pintype "input"))
      (node (ref "IC67") (pin "6") (pinfunction "O_6") (pintype "output"))
    )
    (net (code "426") (name "~{BAC_00}") (class "Default")
      (node (ref "IC134") (pin "1") (pinfunction "I0_1") (pintype "input"))
      (node (ref "IC53") (pin "1") (pinfunction "I_1") (pintype "input"))
      (node (ref "IC83") (pin "3") (pinfunction "O_3") (pintype "output"))
    )
    (net (code "427") (name "~{BAC_01}") (class "Default")
      (node (ref "IC134") (pin "2") (pinfunction "I1_2") (pintype "input"))
      (node (ref "IC53") (pin "5") (pinfunction "I_5") (pintype "input"))
      (node (ref "IC83") (pin "6") (pinfunction "O_6") (pintype "output"))
    )
    (net (code "428") (name "~{BAC_02}") (class "Default")
      (node (ref "IC134") (pin "3") (pinfunction "I2_3") (pintype "input"))
      (node (ref "IC53") (pin "9") (pinfunction "I_9") (pintype "input"))
      (node (ref "IC85") (pin "8") (pinfunction "O_8") (pintype "output"))
    )
    (net (code "429") (name "~{BAC_03}") (class "Default")
      (node (ref "IC134") (pin "4") (pinfunction "I3_4") (pintype "input"))
      (node (ref "IC53") (pin "13") (pinfunction "I_13") (pintype "input"))
      (node (ref "IC84") (pin "8") (pinfunction "O_8") (pintype "output"))
    )
    (net (code "430") (name "~{BAC_04}") (class "Default")
      (node (ref "IC134") (pin "5") (pinfunction "I4_5") (pintype "input"))
      (node (ref "IC84") (pin "11") (pinfunction "O_11") (pintype "output"))
    )
    (net (code "431") (name "~{BAC_05}") (class "Default")
      (node (ref "IC54") (pin "5") (pinfunction "I_5") (pintype "input"))
      (node (ref "IC85") (pin "3") (pinfunction "O_3") (pintype "output"))
    )
    (net (code "432") (name "~{BAC_06}") (class "Default")
      (node (ref "IC54") (pin "9") (pinfunction "I_9") (pintype "input"))
      (node (ref "IC85") (pin "6") (pinfunction "O_6") (pintype "output"))
    )
    (net (code "433") (name "~{BAC_07}") (class "Default")
      (node (ref "IC54") (pin "13") (pinfunction "I_13") (pintype "input"))
      (node (ref "IC84") (pin "6") (pinfunction "O_6") (pintype "output"))
    )
    (net (code "434") (name "~{BAC_08}") (class "Default")
      (node (ref "IC53") (pin "3") (pinfunction "I_3") (pintype "input"))
      (node (ref "IC83") (pin "8") (pinfunction "O_8") (pintype "output"))
    )
    (net (code "435") (name "~{BAC_09}") (class "Default")
      (node (ref "IC53") (pin "11") (pinfunction "I_11") (pintype "input"))
      (node (ref "IC83") (pin "11") (pinfunction "O_11") (pintype "output"))
    )
    (net (code "436") (name "~{BAC_10}") (class "Default")
      (node (ref "IC11") (pin "9") (pinfunction "I0_9") (pintype "input"))
      (node (ref "IC54") (pin "1") (pinfunction "I_1") (pintype "input"))
      (node (ref "IC84") (pin "3") (pinfunction "O_3") (pintype "output"))
    )
    (net (code "437") (name "~{BAC_11}") (class "Default")
      (node (ref "IC107") (pin "10") (pinfunction "I1_10") (pintype "input"))
      (node (ref "IC54") (pin "3") (pinfunction "I_3") (pintype "input"))
      (node (ref "IC85") (pin "11") (pinfunction "O_11") (pintype "output"))
    )
    (net (code "438") (name "~{BLK_IN_SYNC}") (class "Default")
      (node (ref "IC11") (pin "1") (pinfunction "I0_1") (pintype "input"))
      (node (ref "IC111") (pin "13") (pinfunction "I_13") (pintype "input"))
      (node (ref "IC133") (pin "8") (pinfunction "O_8") (pintype "output"))
    )
    (net (code "439") (name "~{BMB_00}") (class "Default")
      (node (ref "IC79") (pin "11") (pinfunction "O_11") (pintype "output"))
      (node (ref "IC91") (pin "9") (pinfunction "I_9") (pintype "input"))
    )
    (net (code "440") (name "~{BMB_01}") (class "Default")
      (node (ref "IC80") (pin "3") (pinfunction "O_3") (pintype "output"))
      (node (ref "IC91") (pin "13") (pinfunction "I_13") (pintype "input"))
    )
    (net (code "441") (name "~{BMB_02}") (class "Default")
      (node (ref "IC82") (pin "6") (pinfunction "O_6") (pintype "output"))
      (node (ref "IC92") (pin "1") (pinfunction "I_1") (pintype "input"))
    )
    (net (code "442") (name "~{BMB_03}") (class "Default")
      (node (ref "IC81") (pin "6") (pinfunction "O_6") (pintype "output"))
      (node (ref "IC92") (pin "5") (pinfunction "I_5") (pintype "input"))
    )
    (net (code "443") (name "~{BMB_04}") (class "Default")
      (node (ref "IC81") (pin "8") (pinfunction "O_8") (pintype "output"))
    )
    (net (code "444") (name "~{BMB_05}") (class "Default")
      (node (ref "IC81") (pin "11") (pinfunction "O_11") (pintype "output"))
      (node (ref "IC92") (pin "13") (pinfunction "I_13") (pintype "input"))
    )
    (net (code "445") (name "~{BMB_06}") (class "Default")
      (node (ref "IC82") (pin "3") (pinfunction "O_3") (pintype "output"))
      (node (ref "IC93") (pin "3") (pinfunction "I_3") (pintype "input"))
    )
    (net (code "446") (name "~{BMB_07}") (class "Default")
      (node (ref "IC81") (pin "3") (pinfunction "O_3") (pintype "output"))
      (node (ref "IC93") (pin "9") (pinfunction "I_9") (pintype "input"))
    )
    (net (code "447") (name "~{BMB_08}") (class "Default")
      (node (ref "IC80") (pin "6") (pinfunction "O_6") (pintype "output"))
      (node (ref "IC91") (pin "11") (pinfunction "I_11") (pintype "input"))
    )
    (net (code "448") (name "~{BMB_09}") (class "Default")
      (node (ref "IC80") (pin "8") (pinfunction "O_8") (pintype "output"))
      (node (ref "IC92") (pin "3") (pinfunction "I_3") (pintype "input"))
    )
    (net (code "449") (name "~{BMB_10}") (class "Default")
      (node (ref "IC80") (pin "11") (pinfunction "O_11") (pintype "output"))
      (node (ref "IC92") (pin "9") (pinfunction "I_9") (pintype "input"))
    )
    (net (code "450") (name "~{BMB_11}") (class "Default")
      (node (ref "IC82") (pin "8") (pinfunction "O_8") (pintype "output"))
      (node (ref "IC92") (pin "11") (pinfunction "I_11") (pintype "input"))
    )
    (net (code "451") (name "~{BMR00}") (class "Default")
      (node (ref "IC76") (pin "8") (pinfunction "~{Q}_8") (pintype "output"))
      (node (ref "M916_7") (pin "H1") (pinfunction "P$2_H1") (pintype "bidirectional"))
    )
    (net (code "452") (name "~{BMR01}") (class "Default")
      (node (ref "IC76") (pin "5") (pinfunction "Q_5") (pintype "output"))
      (node (ref "M916_7") (pin "A1") (pinfunction "P$2_A1") (pintype "bidirectional"))
    )
    (net (code "453") (name "~{C00}") (class "Default")
      (node (ref "IC117") (pin "2") (pinfunction "I1_2") (pintype "input"))
      (node (ref "IC17") (pin "9") (pinfunction "I0_9") (pintype "input"))
      (node (ref "IC75") (pin "11") (pinfunction "CLK_11") (pintype "input"))
      (node (ref "IC75") (pin "2") (pinfunction "D_2") (pintype "input"))
      (node (ref "IC75") (pin "6") (pinfunction "~{Q}_6") (pintype "output"))
      (node (ref "IC78") (pin "1") (pinfunction "I0_1") (pintype "input"))
    )
    (net (code "454") (name "~{C01}") (class "Default")
      (node (ref "IC109") (pin "5") (pinfunction "I2_5") (pintype "input"))
      (node (ref "IC133") (pin "4") (pinfunction "I3_4") (pintype "input"))
      (node (ref "IC17") (pin "10") (pinfunction "I1_10") (pintype "input"))
      (node (ref "IC66") (pin "4") (pinfunction "I2_4") (pintype "input"))
      (node (ref "IC74") (pin "12") (pinfunction "D_12") (pintype "input"))
      (node (ref "IC74") (pin "8") (pinfunction "~{Q}_8") (pintype "output"))
    )
    (net (code "455") (name "~{CK00}") (class "Default")
      (node (ref "IC77") (pin "12") (pinfunction "D_12") (pintype "input"))
      (node (ref "IC77") (pin "6") (pinfunction "~{Q}_6") (pintype "output"))
      (node (ref "M916_3") (pin "N2") (pinfunction "P$2_N2") (pintype "bidirectional"))
    )
    (net (code "456") (name "~{CK01}") (class "Default")
      (node (ref "IC121") (pin "2") (pinfunction "I1_2") (pintype "input"))
      (node (ref "IC121") (pin "4") (pinfunction "I2_4") (pintype "input"))
      (node (ref "IC121") (pin "5") (pinfunction "I3_5") (pintype "input"))
      (node (ref "IC77") (pin "8") (pinfunction "~{Q}_8") (pintype "output"))
    )
    (net (code "457") (name "~{CLR_DF}") (class "Default")
      (node (ref "IC137") (pin "4") (pinfunction "PRE_4") (pintype "input"))
      (node (ref "IC15") (pin "8") (pinfunction "O_8") (pintype "output"))
    )
    (net (code "458") (name "~{CLR_DTF}") (class "Default")
      (node (ref "IC112") (pin "4") (pinfunction "O_4") (pintype "output"))
      (node (ref "IC138") (pin "4") (pinfunction "PRE_4") (pintype "input"))
    )
    (net (code "459") (name "~{CSTA}") (class "Default")
      (node (ref "IC12") (pin "9") (pinfunction "I0_9") (pintype "input"))
      (node (ref "IC55") (pin "11") (pinfunction "I_11") (pintype "input"))
      (node (ref "IC87") (pin "8") (pinfunction "O_8") (pintype "output"))
    )
    (net (code "460") (name "~{DATA}") (class "Default")
      (node (ref "IC107") (pin "1") (pinfunction "I0_1") (pintype "input"))
      (node (ref "IC120") (pin "1") (pinfunction "I0_1") (pintype "input"))
      (node (ref "IC71") (pin "2") (pinfunction "I1_2") (pintype "input"))
      (node (ref "IC99") (pin "10") (pinfunction "O_10") (pintype "output"))
    )
    (net (code "461") (name "~{DB_00_}") (class "Default")
      (node (ref "IC21") (pin "1") (pinfunction "O_1") (pintype "output"))
      (node (ref "IC24") (pin "1") (pinfunction "I0_1") (pintype "input"))
      (node (ref "IC24") (pin "2") (pinfunction "I1_2") (pintype "input"))
    )
    (net (code "462") (name "~{DB_00}") (class "Default")
      (node (ref "IC24") (pin "3") (pinfunction "O_3") (pintype "open_collector"))
      (node (ref "SV10") (pin "D") (pinfunction "4_D") (pintype "bidirectional"))
      (node (ref "SV5") (pin "D") (pinfunction "4_D") (pintype "bidirectional"))
    )
    (net (code "463") (name "~{DB_01_}") (class "Default")
      (node (ref "IC21") (pin "4") (pinfunction "O_4") (pintype "output"))
      (node (ref "IC24") (pin "6") (pinfunction "I0_6") (pintype "input"))
      (node (ref "IC24") (pin "7") (pinfunction "I1_7") (pintype "input"))
    )
    (net (code "464") (name "~{DB_01}") (class "Default")
      (node (ref "IC24") (pin "5") (pinfunction "O_5") (pintype "open_collector"))
      (node (ref "SV10") (pin "J") (pinfunction "8_J") (pintype "bidirectional"))
      (node (ref "SV5") (pin "J") (pinfunction "8_J") (pintype "bidirectional"))
    )
    (net (code "465") (name "~{DB_02_}") (class "Default")
      (node (ref "IC21") (pin "10") (pinfunction "O_10") (pintype "output"))
      (node (ref "IC25") (pin "1") (pinfunction "I0_1") (pintype "input"))
      (node (ref "IC25") (pin "2") (pinfunction "I1_2") (pintype "input"))
    )
    (net (code "466") (name "~{DB_02}") (class "Default")
      (node (ref "IC25") (pin "3") (pinfunction "O_3") (pintype "open_collector"))
      (node (ref "SV10") (pin "N") (pinfunction "12_N") (pintype "bidirectional"))
      (node (ref "SV5") (pin "N") (pinfunction "12_N") (pintype "bidirectional"))
    )
    (net (code "467") (name "~{DB_03_}") (class "Default")
      (node (ref "IC21") (pin "13") (pinfunction "O_13") (pintype "output"))
      (node (ref "IC25") (pin "6") (pinfunction "I0_6") (pintype "input"))
      (node (ref "IC25") (pin "7") (pinfunction "I1_7") (pintype "input"))
    )
    (net (code "468") (name "~{DB_03}") (class "Default")
      (node (ref "IC25") (pin "5") (pinfunction "O_5") (pintype "open_collector"))
      (node (ref "SV10") (pin "T") (pinfunction "16_T") (pintype "bidirectional"))
      (node (ref "SV5") (pin "T") (pinfunction "16_T") (pintype "bidirectional"))
    )
    (net (code "469") (name "~{DB_04_}") (class "Default")
      (node (ref "IC22") (pin "1") (pinfunction "O_1") (pintype "output"))
      (node (ref "IC26") (pin "1") (pinfunction "I0_1") (pintype "input"))
      (node (ref "IC26") (pin "2") (pinfunction "I1_2") (pintype "input"))
    )
    (net (code "470") (name "~{DB_04}") (class "Default")
      (node (ref "IC26") (pin "3") (pinfunction "O_3") (pintype "open_collector"))
      (node (ref "SV10") (pin "X") (pinfunction "20_X") (pintype "bidirectional"))
      (node (ref "SV5") (pin "X") (pinfunction "20_X") (pintype "bidirectional"))
    )
    (net (code "471") (name "~{DB_05_}") (class "Default")
      (node (ref "IC22") (pin "4") (pinfunction "O_4") (pintype "output"))
      (node (ref "IC26") (pin "6") (pinfunction "I0_6") (pintype "input"))
      (node (ref "IC26") (pin "7") (pinfunction "I1_7") (pintype "input"))
    )
    (net (code "472") (name "~{DB_05}") (class "Default")
      (node (ref "IC26") (pin "5") (pinfunction "O_5") (pintype "open_collector"))
      (node (ref "SV10") (pin "BB") (pinfunction "24_BB") (pintype "bidirectional"))
      (node (ref "SV5") (pin "BB") (pinfunction "24_BB") (pintype "bidirectional"))
    )
    (net (code "473") (name "~{DB_06_}") (class "Default")
      (node (ref "IC22") (pin "10") (pinfunction "O_10") (pintype "output"))
      (node (ref "IC27") (pin "1") (pinfunction "I0_1") (pintype "input"))
      (node (ref "IC27") (pin "2") (pinfunction "I1_2") (pintype "input"))
    )
    (net (code "474") (name "~{DB_06}") (class "Default")
      (node (ref "IC27") (pin "3") (pinfunction "O_3") (pintype "open_collector"))
      (node (ref "SV10") (pin "FF") (pinfunction "28_FF") (pintype "bidirectional"))
      (node (ref "SV5") (pin "FF") (pinfunction "28_FF") (pintype "bidirectional"))
    )
    (net (code "475") (name "~{DB_07_}") (class "Default")
      (node (ref "IC22") (pin "13") (pinfunction "O_13") (pintype "output"))
      (node (ref "IC27") (pin "6") (pinfunction "I0_6") (pintype "input"))
      (node (ref "IC27") (pin "7") (pinfunction "I1_7") (pintype "input"))
    )
    (net (code "476") (name "~{DB_07}") (class "Default")
      (node (ref "IC27") (pin "5") (pinfunction "O_5") (pintype "open_collector"))
      (node (ref "SV10") (pin "LL") (pinfunction "32_LL") (pintype "bidirectional"))
      (node (ref "SV5") (pin "LL") (pinfunction "32_LL") (pintype "bidirectional"))
    )
    (net (code "477") (name "~{DB_08_}") (class "Default")
      (node (ref "IC23") (pin "1") (pinfunction "O_1") (pintype "output"))
      (node (ref "IC28") (pin "1") (pinfunction "I0_1") (pintype "input"))
      (node (ref "IC28") (pin "2") (pinfunction "I1_2") (pintype "input"))
    )
    (net (code "478") (name "~{DB_08}") (class "Default")
      (node (ref "IC28") (pin "3") (pinfunction "O_3") (pintype "open_collector"))
      (node (ref "SV10") (pin "RR") (pinfunction "36_RR") (pintype "bidirectional"))
      (node (ref "SV5") (pin "RR") (pinfunction "36_RR") (pintype "bidirectional"))
    )
    (net (code "479") (name "~{DB_09_}") (class "Default")
      (node (ref "IC23") (pin "4") (pinfunction "O_4") (pintype "output"))
      (node (ref "IC28") (pin "6") (pinfunction "I0_6") (pintype "input"))
      (node (ref "IC28") (pin "7") (pinfunction "I1_7") (pintype "input"))
    )
    (net (code "480") (name "~{DB_09}") (class "Default")
      (node (ref "IC28") (pin "5") (pinfunction "O_5") (pintype "open_collector"))
      (node (ref "SV10") (pin "F") (pinfunction "6_F") (pintype "bidirectional"))
      (node (ref "SV5") (pin "F") (pinfunction "6_F") (pintype "bidirectional"))
    )
    (net (code "481") (name "~{DB_10_}") (class "Default")
      (node (ref "IC23") (pin "10") (pinfunction "O_10") (pintype "output"))
      (node (ref "IC29") (pin "1") (pinfunction "I0_1") (pintype "input"))
      (node (ref "IC29") (pin "2") (pinfunction "I1_2") (pintype "input"))
    )
    (net (code "482") (name "~{DB_10}") (class "Default")
      (node (ref "IC29") (pin "3") (pinfunction "O_3") (pintype "open_collector"))
      (node (ref "SV10") (pin "L") (pinfunction "10_L") (pintype "bidirectional"))
      (node (ref "SV5") (pin "L") (pinfunction "10_L") (pintype "bidirectional"))
    )
    (net (code "483") (name "~{DB_11_}") (class "Default")
      (node (ref "IC23") (pin "13") (pinfunction "O_13") (pintype "output"))
      (node (ref "IC29") (pin "6") (pinfunction "I0_6") (pintype "input"))
      (node (ref "IC29") (pin "7") (pinfunction "I1_7") (pintype "input"))
    )
    (net (code "484") (name "~{DB_11}") (class "Default")
      (node (ref "IC29") (pin "5") (pinfunction "O_5") (pintype "open_collector"))
      (node (ref "SV10") (pin "R") (pinfunction "14_R") (pintype "bidirectional"))
      (node (ref "SV5") (pin "R") (pinfunction "14_R") (pintype "bidirectional"))
    )
    (net (code "485") (name "~{DF}") (class "Default")
      (node (ref "IC137") (pin "5") (pinfunction "Q_5") (pintype "output"))
      (node (ref "IC45") (pin "2") (pinfunction "I0_2") (pintype "input"))
      (node (ref "IC70") (pin "12") (pinfunction "I2_12") (pintype "input"))
    )
    (net (code "486") (name "~{DTB_00}") (class "Default")
      (node (ref "IC100") (pin "6") (pinfunction "~{Q}_6") (pintype "output"))
      (node (ref "IC21") (pin "2") (pinfunction "I0_2") (pintype "input"))
    )
    (net (code "487") (name "~{DTB_01}") (class "Default")
      (node (ref "IC100") (pin "8") (pinfunction "~{Q}_8") (pintype "output"))
      (node (ref "IC21") (pin "5") (pinfunction "I0_5") (pintype "input"))
    )
    (net (code "488") (name "~{DTB_02}") (class "Default")
      (node (ref "IC101") (pin "6") (pinfunction "~{Q}_6") (pintype "output"))
      (node (ref "IC21") (pin "8") (pinfunction "I0_8") (pintype "input"))
    )
    (net (code "489") (name "~{DTB_03}") (class "Default")
      (node (ref "IC101") (pin "8") (pinfunction "~{Q}_8") (pintype "output"))
      (node (ref "IC21") (pin "11") (pinfunction "I0_11") (pintype "input"))
    )
    (net (code "490") (name "~{DTB_04}") (class "Default")
      (node (ref "IC102") (pin "6") (pinfunction "~{Q}_6") (pintype "output"))
      (node (ref "IC22") (pin "2") (pinfunction "I0_2") (pintype "input"))
    )
    (net (code "491") (name "~{DTB_05}") (class "Default")
      (node (ref "IC102") (pin "8") (pinfunction "~{Q}_8") (pintype "output"))
      (node (ref "IC22") (pin "5") (pinfunction "I0_5") (pintype "input"))
    )
    (net (code "492") (name "~{DTB_06}") (class "Default")
      (node (ref "IC22") (pin "8") (pinfunction "I0_8") (pintype "input"))
      (node (ref "IC62") (pin "6") (pinfunction "~{Q}_6") (pintype "output"))
    )
    (net (code "493") (name "~{DTB_07}") (class "Default")
      (node (ref "IC22") (pin "11") (pinfunction "I0_11") (pintype "input"))
      (node (ref "IC64") (pin "8") (pinfunction "~{Q}_8") (pintype "output"))
    )
    (net (code "494") (name "~{DTB_08}") (class "Default")
      (node (ref "IC23") (pin "2") (pinfunction "I0_2") (pintype "input"))
      (node (ref "IC63") (pin "6") (pinfunction "~{Q}_6") (pintype "output"))
    )
    (net (code "495") (name "~{DTB_09}") (class "Default")
      (node (ref "IC23") (pin "5") (pinfunction "I0_5") (pintype "input"))
      (node (ref "IC63") (pin "8") (pinfunction "~{Q}_8") (pintype "output"))
    )
    (net (code "496") (name "~{DTB_10}") (class "Default")
      (node (ref "IC23") (pin "8") (pinfunction "I0_8") (pintype "input"))
      (node (ref "IC64") (pin "6") (pinfunction "~{Q}_6") (pintype "output"))
    )
    (net (code "497") (name "~{DTB_11}") (class "Default")
      (node (ref "IC23") (pin "11") (pinfunction "I0_11") (pintype "input"))
      (node (ref "IC62") (pin "8") (pinfunction "~{Q}_8") (pintype "output"))
    )
    (net (code "498") (name "~{DTF}") (class "Default")
      (node (ref "IC138") (pin "5") (pinfunction "Q_5") (pintype "output"))
      (node (ref "IC39") (pin "11") (pinfunction "I0_11") (pintype "input"))
      (node (ref "IC70") (pin "4") (pinfunction "I2_4") (pintype "input"))
    )
    (net (code "499") (name "~{DTSF}") (class "Default")
      (node (ref "IC88") (pin "8") (pinfunction "O_8") (pintype "output"))
      (node (ref "IC91") (pin "1") (pinfunction "I_1") (pintype "input"))
    )
    (net (code "500") (name "~{EA_00_}") (class "Default")
      (node (ref "IC46") (pin "1") (pinfunction "O_1") (pintype "output"))
      (node (ref "IC50") (pin "1") (pinfunction "I0_1") (pintype "input"))
      (node (ref "IC50") (pin "2") (pinfunction "I1_2") (pintype "input"))
    )
    (net (code "501") (name "~{EA_00}") (class "Default")
      (node (ref "IC50") (pin "3") (pinfunction "O_3") (pintype "open_collector"))
      (node (ref "SV10") (pin "TT") (pinfunction "38_TT") (pintype "bidirectional"))
      (node (ref "SV5") (pin "TT") (pinfunction "38_TT") (pintype "bidirectional"))
    )
    (net (code "502") (name "~{EA_01_}") (class "Default")
      (node (ref "IC46") (pin "4") (pinfunction "O_4") (pintype "output"))
      (node (ref "IC50") (pin "6") (pinfunction "I0_6") (pintype "input"))
      (node (ref "IC50") (pin "7") (pinfunction "I1_7") (pintype "input"))
    )
    (net (code "503") (name "~{EA_01}") (class "Default")
      (node (ref "IC50") (pin "5") (pinfunction "O_5") (pintype "open_collector"))
      (node (ref "SV10") (pin "NN") (pinfunction "34_NN") (pintype "bidirectional"))
      (node (ref "SV5") (pin "NN") (pinfunction "34_NN") (pintype "bidirectional"))
    )
    (net (code "504") (name "~{EA_02_}") (class "Default")
      (node (ref "IC46") (pin "10") (pinfunction "O_10") (pintype "output"))
      (node (ref "IC51") (pin "1") (pinfunction "I0_1") (pintype "input"))
      (node (ref "IC51") (pin "2") (pinfunction "I1_2") (pintype "input"))
    )
    (net (code "505") (name "~{EA_02}") (class "Default")
      (node (ref "IC51") (pin "3") (pinfunction "O_3") (pintype "open_collector"))
      (node (ref "SV10") (pin "JJ") (pinfunction "30_JJ") (pintype "bidirectional"))
      (node (ref "SV5") (pin "JJ") (pinfunction "30_JJ") (pintype "bidirectional"))
    )
    (net (code "506") (name "~{EF}") (class "Default")
      (node (ref "IC14") (pin "6") (pinfunction "O_6") (pintype "output"))
      (node (ref "IC32") (pin "8") (pinfunction "I0_8") (pintype "input"))
    )
    (net (code "507") (name "~{END}") (class "Default")
      (node (ref "IC10") (pin "4") (pinfunction "I2_4") (pintype "input"))
      (node (ref "IC38") (pin "2") (pinfunction "I0_2") (pintype "input"))
      (node (ref "IC5") (pin "6") (pinfunction "~{Q}_6") (pintype "output"))
    )
    (net (code "508") (name "~{ENI}") (class "Default")
      (node (ref "IC32") (pin "5") (pinfunction "I0_5") (pintype "input"))
      (node (ref "IC95") (pin "13") (pinfunction "~{Q}_13") (pintype "output"))
    )
    (net (code "509") (name "~{FR_00}") (class "Default")
      (node (ref "IC108") (pin "9") (pinfunction "I0_9") (pintype "input"))
      (node (ref "IC109") (pin "1") (pinfunction "I0_1") (pintype "input"))
      (node (ref "IC31") (pin "5") (pinfunction "I0_5") (pintype "input"))
      (node (ref "IC58") (pin "13") (pinfunction "~{Q}_13") (pintype "output"))
    )
    (net (code "510") (name "~{FR_01}") (class "Default")
      (node (ref "IC16") (pin "9") (pinfunction "I0_9") (pintype "input"))
      (node (ref "IC31") (pin "8") (pinfunction "I0_8") (pintype "input"))
      (node (ref "IC46") (pin "11") (pinfunction "I0_11") (pintype "input"))
      (node (ref "IC58") (pin "8") (pinfunction "~{Q}_8") (pintype "output"))
    )
    (net (code "511") (name "~{FR_02}") (class "Default")
      (node (ref "IC31") (pin "11") (pinfunction "I0_11") (pintype "input"))
      (node (ref "IC94") (pin "13") (pinfunction "~{Q}_13") (pintype "output"))
    )
    (net (code "512") (name "~{FR_03}") (class "Default")
      (node (ref "IC32") (pin "2") (pinfunction "I0_2") (pintype "input"))
      (node (ref "IC60") (pin "2") (pinfunction "I1_2") (pintype "input"))
      (node (ref "IC94") (pin "8") (pinfunction "~{Q}_8") (pintype "output"))
    )
    (net (code "513") (name "~{IM_00_}") (class "Default")
      (node (ref "IC30") (pin "1") (pinfunction "O_1") (pintype "output"))
      (node (ref "IC32") (pin "10") (pinfunction "O_10") (pintype "output"))
      (node (ref "IC33") (pin "1") (pinfunction "I0_1") (pintype "input"))
      (node (ref "IC33") (pin "2") (pinfunction "I1_2") (pintype "input"))
      (node (ref "IC40") (pin "1") (pinfunction "I0_1") (pintype "input"))
      (node (ref "IC40") (pin "2") (pinfunction "I1_2") (pintype "input"))
    )
    (net (code "514") (name "~{IM_00}") (class "Default")
      (node (ref "IC33") (pin "3") (pinfunction "O_3") (pintype "open_collector"))
      (node (ref "IC40") (pin "3") (pinfunction "O_3") (pintype "open_collector"))
      (node (ref "SV3") (pin "D") (pinfunction "4_D") (pintype "bidirectional"))
      (node (ref "SV8") (pin "D") (pinfunction "4_D") (pintype "bidirectional"))
    )
    (net (code "515") (name "~{IM_01_}") (class "Default")
      (node (ref "IC30") (pin "4") (pinfunction "O_4") (pintype "output"))
      (node (ref "IC32") (pin "13") (pinfunction "O_13") (pintype "output"))
      (node (ref "IC33") (pin "6") (pinfunction "I0_6") (pintype "input"))
      (node (ref "IC33") (pin "7") (pinfunction "I1_7") (pintype "input"))
      (node (ref "IC40") (pin "6") (pinfunction "I0_6") (pintype "input"))
      (node (ref "IC40") (pin "7") (pinfunction "I1_7") (pintype "input"))
    )
    (net (code "516") (name "~{IM_01}") (class "Default")
      (node (ref "IC33") (pin "5") (pinfunction "O_5") (pintype "open_collector"))
      (node (ref "IC40") (pin "5") (pinfunction "O_5") (pintype "open_collector"))
      (node (ref "SV3") (pin "J") (pinfunction "8_J") (pintype "bidirectional"))
      (node (ref "SV8") (pin "J") (pinfunction "8_J") (pintype "bidirectional"))
    )
    (net (code "517") (name "~{IM_02_}") (class "Default")
      (node (ref "IC30") (pin "10") (pinfunction "O_10") (pintype "output"))
      (node (ref "IC34") (pin "1") (pinfunction "I0_1") (pintype "input"))
      (node (ref "IC34") (pin "2") (pinfunction "I1_2") (pintype "input"))
      (node (ref "IC38") (pin "1") (pinfunction "O_1") (pintype "output"))
      (node (ref "IC41") (pin "1") (pinfunction "I0_1") (pintype "input"))
      (node (ref "IC41") (pin "2") (pinfunction "I1_2") (pintype "input"))
    )
    (net (code "518") (name "~{IM_02}") (class "Default")
      (node (ref "IC34") (pin "3") (pinfunction "O_3") (pintype "open_collector"))
      (node (ref "IC41") (pin "3") (pinfunction "O_3") (pintype "open_collector"))
      (node (ref "SV3") (pin "N") (pinfunction "12_N") (pintype "bidirectional"))
      (node (ref "SV8") (pin "N") (pinfunction "12_N") (pintype "bidirectional"))
    )
    (net (code "519") (name "~{IM_03_}") (class "Default")
      (node (ref "IC30") (pin "13") (pinfunction "O_13") (pintype "output"))
      (node (ref "IC34") (pin "6") (pinfunction "I0_6") (pintype "input"))
      (node (ref "IC34") (pin "7") (pinfunction "I1_7") (pintype "input"))
      (node (ref "IC38") (pin "4") (pinfunction "O_4") (pintype "output"))
      (node (ref "IC41") (pin "6") (pinfunction "I0_6") (pintype "input"))
      (node (ref "IC41") (pin "7") (pinfunction "I1_7") (pintype "input"))
    )
    (net (code "520") (name "~{IM_03}") (class "Default")
      (node (ref "IC34") (pin "5") (pinfunction "O_5") (pintype "open_collector"))
      (node (ref "IC41") (pin "5") (pinfunction "O_5") (pintype "open_collector"))
      (node (ref "SV3") (pin "T") (pinfunction "16_T") (pintype "bidirectional"))
      (node (ref "SV8") (pin "T") (pinfunction "16_T") (pintype "bidirectional"))
    )
    (net (code "521") (name "~{IM_04_}") (class "Default")
      (node (ref "IC31") (pin "1") (pinfunction "O_1") (pintype "output"))
      (node (ref "IC35") (pin "1") (pinfunction "I0_1") (pintype "input"))
      (node (ref "IC35") (pin "2") (pinfunction "I1_2") (pintype "input"))
      (node (ref "IC38") (pin "10") (pinfunction "O_10") (pintype "output"))
      (node (ref "IC42") (pin "1") (pinfunction "I0_1") (pintype "input"))
      (node (ref "IC42") (pin "2") (pinfunction "I1_2") (pintype "input"))
    )
    (net (code "522") (name "~{IM_04}") (class "Default")
      (node (ref "IC35") (pin "3") (pinfunction "O_3") (pintype "open_collector"))
      (node (ref "IC42") (pin "3") (pinfunction "O_3") (pintype "open_collector"))
      (node (ref "SV3") (pin "X") (pinfunction "20_X") (pintype "bidirectional"))
      (node (ref "SV8") (pin "X") (pinfunction "20_X") (pintype "bidirectional"))
    )
    (net (code "523") (name "~{IM_05_}") (class "Default")
      (node (ref "IC31") (pin "4") (pinfunction "O_4") (pintype "output"))
      (node (ref "IC35") (pin "6") (pinfunction "I0_6") (pintype "input"))
      (node (ref "IC35") (pin "7") (pinfunction "I1_7") (pintype "input"))
      (node (ref "IC38") (pin "13") (pinfunction "O_13") (pintype "output"))
      (node (ref "IC42") (pin "6") (pinfunction "I0_6") (pintype "input"))
      (node (ref "IC42") (pin "7") (pinfunction "I1_7") (pintype "input"))
    )
    (net (code "524") (name "~{IM_05}") (class "Default")
      (node (ref "IC35") (pin "5") (pinfunction "O_5") (pintype "open_collector"))
      (node (ref "IC42") (pin "5") (pinfunction "O_5") (pintype "open_collector"))
      (node (ref "SV3") (pin "BB") (pinfunction "24_BB") (pintype "bidirectional"))
      (node (ref "SV8") (pin "BB") (pinfunction "24_BB") (pintype "bidirectional"))
    )
    (net (code "525") (name "~{IM_06_}") (class "Default")
      (node (ref "IC31") (pin "10") (pinfunction "O_10") (pintype "output"))
      (node (ref "IC36") (pin "1") (pinfunction "I0_1") (pintype "input"))
      (node (ref "IC36") (pin "2") (pinfunction "I1_2") (pintype "input"))
      (node (ref "IC39") (pin "1") (pinfunction "O_1") (pintype "output"))
      (node (ref "IC43") (pin "1") (pinfunction "I0_1") (pintype "input"))
      (node (ref "IC43") (pin "2") (pinfunction "I1_2") (pintype "input"))
    )
    (net (code "526") (name "~{IM_06}") (class "Default")
      (node (ref "IC36") (pin "3") (pinfunction "O_3") (pintype "open_collector"))
      (node (ref "IC43") (pin "3") (pinfunction "O_3") (pintype "open_collector"))
      (node (ref "SV3") (pin "FF") (pinfunction "28_FF") (pintype "bidirectional"))
      (node (ref "SV8") (pin "FF") (pinfunction "28_FF") (pintype "bidirectional"))
    )
    (net (code "527") (name "~{IM_07_}") (class "Default")
      (node (ref "IC31") (pin "13") (pinfunction "O_13") (pintype "output"))
      (node (ref "IC36") (pin "6") (pinfunction "I0_6") (pintype "input"))
      (node (ref "IC36") (pin "7") (pinfunction "I1_7") (pintype "input"))
      (node (ref "IC39") (pin "4") (pinfunction "O_4") (pintype "output"))
      (node (ref "IC43") (pin "6") (pinfunction "I0_6") (pintype "input"))
      (node (ref "IC43") (pin "7") (pinfunction "I1_7") (pintype "input"))
    )
    (net (code "528") (name "~{IM_07}") (class "Default")
      (node (ref "IC36") (pin "5") (pinfunction "O_5") (pintype "open_collector"))
      (node (ref "IC43") (pin "5") (pinfunction "O_5") (pintype "open_collector"))
      (node (ref "SV3") (pin "LL") (pinfunction "32_LL") (pintype "bidirectional"))
      (node (ref "SV8") (pin "LL") (pinfunction "32_LL") (pintype "bidirectional"))
    )
    (net (code "529") (name "~{IM_08_}") (class "Default")
      (node (ref "IC32") (pin "1") (pinfunction "O_1") (pintype "output"))
      (node (ref "IC37") (pin "1") (pinfunction "I0_1") (pintype "input"))
      (node (ref "IC37") (pin "2") (pinfunction "I1_2") (pintype "input"))
      (node (ref "IC39") (pin "10") (pinfunction "O_10") (pintype "output"))
      (node (ref "IC44") (pin "1") (pinfunction "I0_1") (pintype "input"))
      (node (ref "IC44") (pin "2") (pinfunction "I1_2") (pintype "input"))
    )
    (net (code "530") (name "~{IM_08}") (class "Default")
      (node (ref "IC37") (pin "3") (pinfunction "O_3") (pintype "open_collector"))
      (node (ref "IC44") (pin "3") (pinfunction "O_3") (pintype "open_collector"))
      (node (ref "SV3") (pin "RR") (pinfunction "36_RR") (pintype "bidirectional"))
      (node (ref "SV8") (pin "RR") (pinfunction "36_RR") (pintype "bidirectional"))
    )
    (net (code "531") (name "~{IM_09_}") (class "Default")
      (node (ref "IC32") (pin "4") (pinfunction "O_4") (pintype "output"))
      (node (ref "IC37") (pin "6") (pinfunction "I0_6") (pintype "input"))
      (node (ref "IC37") (pin "7") (pinfunction "I1_7") (pintype "input"))
    )
    (net (code "532") (name "~{IM_09}") (class "Default")
      (node (ref "IC37") (pin "5") (pinfunction "O_5") (pintype "open_collector"))
      (node (ref "SV3") (pin "F") (pinfunction "6_F") (pintype "bidirectional"))
      (node (ref "SV8") (pin "F") (pinfunction "6_F") (pintype "bidirectional"))
    )
    (net (code "533") (name "~{IM_10}") (class "Default")
      (node (ref "SV3") (pin "L") (pinfunction "10_L") (pintype "bidirectional"))
      (node (ref "SV8") (pin "L") (pinfunction "10_L") (pintype "bidirectional"))
    )
    (net (code "534") (name "~{IM_11_}") (class "Default")
      (node (ref "IC39") (pin "13") (pinfunction "O_13") (pintype "output"))
      (node (ref "IC44") (pin "6") (pinfunction "I0_6") (pintype "input"))
      (node (ref "IC44") (pin "7") (pinfunction "I1_7") (pintype "input"))
    )
    (net (code "535") (name "~{IM_11}") (class "Default")
      (node (ref "IC44") (pin "5") (pinfunction "O_5") (pintype "open_collector"))
      (node (ref "SV3") (pin "R") (pinfunction "14_R") (pintype "bidirectional"))
      (node (ref "SV8") (pin "R") (pinfunction "14_R") (pintype "bidirectional"))
    )
    (net (code "536") (name "~{INT_RQ}") (class "Default")
      (node (ref "IC16") (pin "6") (pinfunction "O_6") (pintype "output"))
      (node (ref "IC45") (pin "5") (pinfunction "I0_5") (pintype "input"))
    )
    (net (code "537") (name "~{LDMF}") (class "Default")
      (node (ref "IC61") (pin "1") (pinfunction "I0_1") (pintype "input"))
      (node (ref "IC90") (pin "3") (pinfunction "O_3") (pintype "output"))
      (node (ref "IC91") (pin "5") (pinfunction "I_5") (pintype "input"))
    )
    (net (code "538") (name "~{LPB_00}") (class "Default")
      (node (ref "IC126") (pin "13") (pinfunction "~{Q}_13") (pintype "output"))
      (node (ref "IC135") (pin "1") (pinfunction "I0_1") (pintype "input"))
    )
    (net (code "539") (name "~{LPB_01}") (class "Default")
      (node (ref "IC127") (pin "13") (pinfunction "~{Q}_13") (pintype "output"))
      (node (ref "IC135") (pin "2") (pinfunction "I1_2") (pintype "input"))
    )
    (net (code "540") (name "~{LPB_02}") (class "Default")
      (node (ref "IC128") (pin "13") (pinfunction "~{Q}_13") (pintype "output"))
      (node (ref "IC135") (pin "3") (pinfunction "I2_3") (pintype "input"))
    )
    (net (code "541") (name "~{LPB_03}") (class "Default")
      (node (ref "IC126") (pin "8") (pinfunction "~{Q}_8") (pintype "output"))
      (node (ref "IC135") (pin "4") (pinfunction "I3_4") (pintype "input"))
    )
    (net (code "542") (name "~{LPB_04}") (class "Default")
      (node (ref "IC127") (pin "8") (pinfunction "~{Q}_8") (pintype "output"))
      (node (ref "IC135") (pin "5") (pinfunction "I4_5") (pintype "input"))
    )
    (net (code "543") (name "~{LPB_05}") (class "Default")
      (node (ref "IC128") (pin "8") (pinfunction "~{Q}_8") (pintype "output"))
      (node (ref "IC135") (pin "11") (pinfunction "I6_11") (pintype "input"))
      (node (ref "IC135") (pin "12") (pinfunction "I7_12") (pintype "input"))
      (node (ref "IC135") (pin "6") (pinfunction "I5_6") (pintype "input"))
    )
    (net (code "544") (name "~{M-STOP}") (class "Default")
      (node (ref "IC15") (pin "4") (pinfunction "O_4") (pintype "output"))
      (node (ref "IC76") (pin "4") (pinfunction "PRE_4") (pintype "input"))
      (node (ref "IC95") (pin "6") (pinfunction "CL_6") (pintype "input"))
      (node (ref "M916_20") (pin "L1") (pinfunction "P$2_L1") (pintype "bidirectional"))
    )
    (net (code "545") (name "~{MB_TO_DTB}") (class "Default")
      (node (ref "IC139") (pin "1") (pinfunction "I0_1") (pintype "input"))
      (node (ref "IC139") (pin "2") (pinfunction "I1_2") (pintype "input"))
      (node (ref "IC139") (pin "4") (pinfunction "I2_4") (pintype "input"))
      (node (ref "IC139") (pin "5") (pinfunction "I3_5") (pintype "input"))
      (node (ref "IC139") (pin "8") (pinfunction "O_8") (pintype "output"))
    )
    (net (code "546") (name "~{MC00}") (class "Default")
      (node (ref "IC12") (pin "13") (pinfunction "I1_13") (pintype "input"))
      (node (ref "IC69") (pin "9") (pinfunction "I0_9") (pintype "input"))
      (node (ref "IC73") (pin "6") (pinfunction "~{Q}_6") (pintype "output"))
    )
    (net (code "547") (name "~{MC01}") (class "Default")
      (node (ref "IC133") (pin "6") (pinfunction "I5_6") (pintype "input"))
      (node (ref "IC68") (pin "3") (pinfunction "I0_3") (pintype "input"))
      (node (ref "IC73") (pin "8") (pinfunction "~{Q}_8") (pintype "output"))
      (node (ref "IC90") (pin "10") (pinfunction "I1_10") (pintype "input"))
    )
    (net (code "548") (name "~{MC02}") (class "Default")
      (node (ref "IC133") (pin "11") (pinfunction "I6_11") (pintype "input"))
      (node (ref "IC73") (pin "2") (pinfunction "D_2") (pintype "input"))
      (node (ref "IC74") (pin "6") (pinfunction "~{Q}_6") (pintype "output"))
    )
    (net (code "549") (name "~{MF00}") (class "Default")
      (node (ref "IC115") (pin "8") (pinfunction "~{Q}_8") (pintype "output"))
      (node (ref "IC39") (pin "2") (pinfunction "I0_2") (pintype "input"))
      (node (ref "IC46") (pin "2") (pinfunction "I0_2") (pintype "input"))
    )
    (net (code "550") (name "~{MF01}") (class "Default")
      (node (ref "IC136") (pin "6") (pinfunction "~{Q}_6") (pintype "output"))
      (node (ref "IC39") (pin "5") (pinfunction "I0_5") (pintype "input"))
      (node (ref "IC46") (pin "5") (pinfunction "I0_5") (pintype "input"))
    )
    (net (code "551") (name "~{MF02}") (class "Default")
      (node (ref "IC136") (pin "8") (pinfunction "~{Q}_8") (pintype "output"))
      (node (ref "IC39") (pin "8") (pinfunction "I0_8") (pintype "input"))
      (node (ref "IC46") (pin "8") (pinfunction "I0_8") (pintype "input"))
    )
    (net (code "552") (name "~{MKTK}") (class "Default")
      (node (ref "IC10") (pin "1") (pinfunction "I0_1") (pintype "input"))
      (node (ref "IC32") (pin "11") (pinfunction "I0_11") (pintype "input"))
      (node (ref "IC6") (pin "9") (pinfunction "Q_9") (pintype "output"))
    )
    (net (code "553") (name "~{MKT}") (class "Default")
      (node (ref "IC115") (pin "3") (pinfunction "CLK_3") (pintype "input"))
      (node (ref "IC133") (pin "12") (pinfunction "I7_12") (pintype "input"))
      (node (ref "IC66") (pin "5") (pinfunction "I3_5") (pintype "input"))
      (node (ref "IC75") (pin "12") (pinfunction "D_12") (pintype "input"))
      (node (ref "IC75") (pin "8") (pinfunction "~{Q}_8") (pintype "output"))
    )
    (net (code "554") (name "~{MK_BLK_END}") (class "Default")
      (node (ref "IC8") (pin "4") (pinfunction "I2_4") (pintype "input"))
    )
    (net (code "555") (name "~{MK_BLK_START}") (class "Default")
      (node (ref "IC8") (pin "1") (pinfunction "I0_1") (pintype "input"))
    )
    (net (code "556") (name "~{MK_DATA}") (class "Default")
      (node (ref "IC8") (pin "2") (pinfunction "I1_2") (pintype "input"))
    )
    (net (code "557") (name "~{MK_END}") (class "Default")
      (node (ref "IC8") (pin "5") (pinfunction "I3_5") (pintype "input"))
    )
    (net (code "558") (name "~{MOVE}") (class "Default")
      (node (ref "IC123") (pin "11") (pinfunction "I_11") (pintype "input"))
      (node (ref "IC124") (pin "1") (pinfunction "0_1") (pintype "output"))
      (node (ref "IC9") (pin "12") (pinfunction "I2_12") (pintype "input"))
    )
    (net (code "559") (name "~{MR00}") (class "Default")
      (node (ref "IC30") (pin "11") (pinfunction "I0_11") (pintype "input"))
      (node (ref "IC57") (pin "8") (pinfunction "~{Q}_8") (pintype "output"))
    )
    (net (code "560") (name "~{MR01}") (class "Default")
      (node (ref "IC31") (pin "2") (pinfunction "I0_2") (pintype "input"))
      (node (ref "IC76") (pin "2") (pinfunction "D_2") (pintype "input"))
      (node (ref "IC95") (pin "8") (pinfunction "~{Q}_8") (pintype "output"))
    )
    (net (code "561") (name "~{PAR}") (class "Default")
      (node (ref "IC13") (pin "13") (pinfunction "I1_13") (pintype "input"))
      (node (ref "IC38") (pin "8") (pinfunction "I0_8") (pintype "input"))
      (node (ref "IC7") (pin "5") (pinfunction "Q_5") (pintype "output"))
    )
    (net (code "562") (name "~{PC+ES}") (class "Default")
      (node (ref "IC14") (pin "8") (pinfunction "O_8") (pintype "output"))
      (node (ref "IC69") (pin "5") (pinfunction "I2_5") (pintype "input"))
    )
    (net (code "563") (name "~{PWR_CLR}") (class "Default")
      (node (ref "IC107") (pin "13") (pinfunction "I1_13") (pintype "input"))
      (node (ref "IC115") (pin "13") (pinfunction "CLR_13") (pintype "input"))
      (node (ref "IC115") (pin "4") (pinfunction "PRE_4") (pintype "input"))
      (node (ref "IC12") (pin "1") (pinfunction "I0_1") (pintype "input"))
      (node (ref "IC12") (pin "10") (pinfunction "I1_10") (pintype "input"))
      (node (ref "IC13") (pin "9") (pinfunction "I0_9") (pintype "input"))
      (node (ref "IC136") (pin "1") (pinfunction "CLR_1") (pintype "input"))
      (node (ref "IC136") (pin "13") (pinfunction "CLR_13") (pintype "input"))
      (node (ref "IC61") (pin "5") (pinfunction "I1_5") (pintype "input"))
      (node (ref "IC90") (pin "6") (pinfunction "O_6") (pintype "output"))
      (node (ref "IC93") (pin "5") (pinfunction "I_5") (pintype "input"))
      (node (ref "M916_7") (pin "M1") (pinfunction "P$2_M1") (pintype "bidirectional"))
    )
    (net (code "564") (name "~{RDD_00}") (class "Default")
      (node (ref "M916_5") (pin "V2") (pinfunction "P$2_V2") (pintype "bidirectional"))
    )
    (net (code "565") (name "~{RDD_01}") (class "Default")
      (node (ref "M916_14") (pin "V2") (pinfunction "P$2_V2") (pintype "bidirectional"))
    )
    (net (code "566") (name "~{RDD_02}") (class "Default")
      (node (ref "M916_4") (pin "V2") (pinfunction "P$2_V2") (pintype "bidirectional"))
    )
    (net (code "567") (name "~{RDMK}") (class "Default")
      (node (ref "M916_13") (pin "V2") (pinfunction "P$2_V2") (pintype "bidirectional"))
    )
    (net (code "568") (name "~{READ_ALL}") (class "Default")
      (node (ref "IC106") (pin "13") (pinfunction "I1_13") (pintype "input"))
      (node (ref "IC124") (pin "4") (pinfunction "3_4") (pintype "output"))
      (node (ref "IC125") (pin "3") (pinfunction "I_3") (pintype "input"))
    )
    (net (code "569") (name "~{READ_DATA}") (class "Default")
      (node (ref "IC124") (pin "3") (pinfunction "2_3") (pintype "output"))
      (node (ref "IC125") (pin "1") (pinfunction "I_1") (pintype "input"))
      (node (ref "IC60") (pin "9") (pinfunction "I0_9") (pintype "input"))
      (node (ref "IC69") (pin "1") (pinfunction "I0_1") (pintype "input"))
    )
    (net (code "570") (name "~{RSTA}") (class "Default")
      (node (ref "IC30") (pin "12") (pinfunction "I1_12") (pintype "input"))
      (node (ref "IC30") (pin "3") (pinfunction "I1_3") (pintype "input"))
      (node (ref "IC30") (pin "6") (pinfunction "I1_6") (pintype "input"))
      (node (ref "IC30") (pin "9") (pinfunction "I1_9") (pintype "input"))
      (node (ref "IC31") (pin "12") (pinfunction "I1_12") (pintype "input"))
      (node (ref "IC31") (pin "3") (pinfunction "I1_3") (pintype "input"))
      (node (ref "IC31") (pin "6") (pinfunction "I1_6") (pintype "input"))
      (node (ref "IC31") (pin "9") (pinfunction "I1_9") (pintype "input"))
      (node (ref "IC32") (pin "3") (pinfunction "I1_3") (pintype "input"))
      (node (ref "IC32") (pin "6") (pinfunction "I1_6") (pintype "input"))
      (node (ref "IC55") (pin "9") (pinfunction "I_9") (pintype "input"))
      (node (ref "IC87") (pin "6") (pinfunction "O_6") (pintype "output"))
    )
    (net (code "571") (name "~{RSTB}") (class "Default")
      (node (ref "IC32") (pin "12") (pinfunction "I1_12") (pintype "input"))
      (node (ref "IC32") (pin "9") (pinfunction "I1_9") (pintype "input"))
      (node (ref "IC38") (pin "12") (pinfunction "I1_12") (pintype "input"))
      (node (ref "IC38") (pin "3") (pinfunction "I1_3") (pintype "input"))
      (node (ref "IC38") (pin "6") (pinfunction "I1_6") (pintype "input"))
      (node (ref "IC38") (pin "9") (pinfunction "I1_9") (pintype "input"))
      (node (ref "IC39") (pin "12") (pinfunction "I1_12") (pintype "input"))
      (node (ref "IC39") (pin "3") (pinfunction "I1_3") (pintype "input"))
      (node (ref "IC39") (pin "6") (pinfunction "I1_6") (pintype "input"))
      (node (ref "IC39") (pin "9") (pinfunction "I1_9") (pintype "input"))
      (node (ref "IC88") (pin "11") (pinfunction "O_11") (pintype "output"))
      (node (ref "IC91") (pin "3") (pinfunction "I_3") (pintype "input"))
    )
    (net (code "572") (name "~{SEARCH}") (class "Default")
      (node (ref "IC123") (pin "13") (pinfunction "I_13") (pintype "input"))
      (node (ref "IC124") (pin "2") (pinfunction "1_2") (pintype "output"))
      (node (ref "IC47") (pin "2") (pinfunction "I0_2") (pintype "input"))
      (node (ref "IC69") (pin "2") (pinfunction "I1_2") (pintype "input"))
    )
    (net (code "573") (name "~{SEL}") (class "Default")
      (node (ref "IC10") (pin "5") (pinfunction "I3_5") (pintype "input"))
      (node (ref "IC38") (pin "5") (pinfunction "I0_5") (pintype "input"))
      (node (ref "IC5") (pin "8") (pinfunction "~{Q}_8") (pintype "output"))
    )
    (net (code "574") (name "~{SE}") (class "Default")
      (node (ref "IC124") (pin "8") (pinfunction "7_8") (pintype "output"))
      (node (ref "IC125") (pin "13") (pinfunction "I_13") (pintype "input"))
      (node (ref "IC8") (pin "10") (pinfunction "I1_10") (pintype "input"))
    )
    (net (code "575") (name "~{SH_EN}") (class "Default")
      (node (ref "IC103") (pin "4") (pinfunction "2C_4") (pintype "input"))
      (node (ref "IC104") (pin "4") (pinfunction "2C_4") (pintype "input"))
      (node (ref "IC105") (pin "9") (pinfunction "1D_9") (pintype "input"))
      (node (ref "IC15") (pin "1") (pinfunction "I_1") (pintype "input"))
      (node (ref "IC17") (pin "11") (pinfunction "O_11") (pintype "output"))
    )
    (net (code "576") (name "~{SKP_RQ}") (class "Default")
      (node (ref "IC17") (pin "6") (pinfunction "O_6") (pintype "output"))
      (node (ref "IC45") (pin "8") (pinfunction "I0_8") (pintype "input"))
    )
    (net (code "577") (name "~{SP_DY}") (class "Default")
      (node (ref "IC114") (pin "12") (pinfunction "D_12") (pintype "input"))
      (node (ref "M916_20") (pin "F2") (pinfunction "P$2_F2") (pintype "bidirectional"))
    )
    (net (code "578") (name "~{ST_BLK_MK}") (class "Default")
      (node (ref "IC9") (pin "1") (pinfunction "I0_1") (pintype "input"))
      (node (ref "IC9") (pin "9") (pinfunction "I0_9") (pintype "input"))
      (node (ref "IC99") (pin "12") (pinfunction "O_12") (pintype "output"))
    )
    (net (code "579") (name "~{ST_CK_0P}") (class "Default")
      (node (ref "IC99") (pin "3") (pinfunction "I_3") (pintype "input"))
      (node (ref "M916_23") (pin "L2") (pinfunction "P$2_L2") (pintype "bidirectional"))
    )
    (net (code "580") (name "~{ST_CK}") (class "Default")
      (node (ref "IC111") (pin "2") (pinfunction "O_2") (pintype "output"))
      (node (ref "IC120") (pin "2") (pinfunction "I1_2") (pintype "input"))
    )
    (net (code "581") (name "~{ST_DATA}") (class "Default")
      (node (ref "IC111") (pin "4") (pinfunction "O_4") (pintype "output"))
    )
    (net (code "582") (name "~{ST_FINAL}") (class "Default")
      (node (ref "IC107") (pin "2") (pinfunction "I1_2") (pintype "input"))
      (node (ref "IC120") (pin "4") (pinfunction "I2_4") (pintype "input"))
    )
    (net (code "583") (name "~{ST_IDLE}") (class "Default")
      (node (ref "IC111") (pin "6") (pinfunction "O_6") (pintype "output"))
      (node (ref "IC9") (pin "10") (pinfunction "I1_10") (pintype "input"))
      (node (ref "IC9") (pin "2") (pinfunction "I1_2") (pintype "input"))
    )
    (net (code "584") (name "~{ST_REV_CK}") (class "Default")
      (node (ref "IC99") (pin "8") (pinfunction "O_8") (pintype "output"))
    )
    (net (code "585") (name "~{SWTM}") (class "Default")
      (node (ref "IC104") (pin "12") (pinfunction "1B_12") (pintype "input"))
      (node (ref "IC54") (pin "10") (pinfunction "O_10") (pintype "output"))
    )
    (net (code "586") (name "~{SYNC-P}") (class "Default")
      (node (ref "IC66") (pin "8") (pinfunction "O_8") (pintype "output"))
      (node (ref "IC73") (pin "1") (pinfunction "CLR_1") (pintype "input"))
      (node (ref "IC73") (pin "13") (pinfunction "CLR_13") (pintype "input"))
      (node (ref "IC74") (pin "1") (pinfunction "CLR_1") (pintype "input"))
      (node (ref "IC74") (pin "13") (pinfunction "CLR_13") (pintype "input"))
      (node (ref "IC75") (pin "1") (pinfunction "CLR_1") (pintype "input"))
      (node (ref "IC75") (pin "13") (pinfunction "CLR_13") (pintype "input"))
    )
    (net (code "587") (name "~{TIM}") (class "Default")
      (node (ref "IC10") (pin "2") (pinfunction "I1_2") (pintype "input"))
      (node (ref "IC38") (pin "11") (pinfunction "I0_11") (pintype "input"))
      (node (ref "IC6") (pin "6") (pinfunction "~{Q}_6") (pintype "output"))
    )
    (net (code "588") (name "~{TM_EN}") (class "Default")
      (node (ref "IC108") (pin "13") (pinfunction "I2_13") (pintype "input"))
      (node (ref "IC109") (pin "10") (pinfunction "I1_10") (pintype "input"))
      (node (ref "IC111") (pin "8") (pinfunction "O_8") (pintype "output"))
      (node (ref "IC61") (pin "12") (pinfunction "I0_12") (pintype "input"))
      (node (ref "IC61") (pin "9") (pinfunction "I0_9") (pintype "input"))
      (node (ref "M916_21") (pin "J2") (pinfunction "P$2_J2") (pintype "bidirectional"))
      (node (ref "M916_21") (pin "K2") (pinfunction "P$2_K2") (pintype "bidirectional"))
    )
    (net (code "589") (name "~{TP00_A}") (class "Default")
      (node (ref "IC19") (pin "1") (pinfunction "I0_1") (pintype "input"))
      (node (ref "IC19") (pin "2") (pinfunction "I1_2") (pintype "input"))
      (node (ref "IC19") (pin "4") (pinfunction "I2_4") (pintype "input"))
      (node (ref "IC19") (pin "5") (pinfunction "I3_5") (pintype "input"))
      (node (ref "M916_2") (pin "L2") (pinfunction "P$2_L2") (pintype "bidirectional"))
    )
    (net (code "590") (name "~{TP0_XTLK_DY}") (class "Default")
      (node (ref "IC15") (pin "6") (pinfunction "O_6") (pintype "output"))
      (node (ref "IC19") (pin "12") (pinfunction "I2_12") (pintype "input"))
      (node (ref "M916_2") (pin "J2") (pinfunction "P$2_J2") (pintype "bidirectional"))
      (node (ref "M916_2") (pin "K2") (pinfunction "P$2_K2") (pintype "bidirectional"))
    )
    (net (code "591") (name "~{TP00}") (class "Default")
      (node (ref "IC18") (pin "10") (pinfunction "I1_10") (pintype "input"))
      (node (ref "IC18") (pin "12") (pinfunction "I2_12") (pintype "input"))
      (node (ref "IC18") (pin "13") (pinfunction "I3_13") (pintype "input"))
      (node (ref "IC18") (pin "6") (pinfunction "O_6") (pintype "output"))
      (node (ref "IC18") (pin "9") (pinfunction "I0_9") (pintype "input"))
      (node (ref "IC75") (pin "3") (pinfunction "CLK_3") (pintype "input"))
    )
    (net (code "592") (name "~{TP01_A}") (class "Default")
      (node (ref "IC20") (pin "10") (pinfunction "I1_10") (pintype "input"))
      (node (ref "IC20") (pin "12") (pinfunction "I2_12") (pintype "input"))
      (node (ref "IC20") (pin "13") (pinfunction "I3_13") (pintype "input"))
      (node (ref "IC20") (pin "9") (pinfunction "I0_9") (pintype "input"))
      (node (ref "M916_12") (pin "L2") (pinfunction "P$2_L2") (pintype "bidirectional"))
    )
    (net (code "593") (name "~{TP1_XTLK_DY}") (class "Default")
      (node (ref "IC15") (pin "12") (pinfunction "O_12") (pintype "output"))
      (node (ref "IC18") (pin "2") (pinfunction "I1_2") (pintype "input"))
      (node (ref "M916_12") (pin "H2") (pinfunction "P$2_H2") (pintype "bidirectional"))
      (node (ref "M916_12") (pin "J2") (pinfunction "P$2_J2") (pintype "bidirectional"))
    )
    (net (code "594") (name "~{TP01}") (class "Default")
      (node (ref "IC19") (pin "8") (pinfunction "O_8") (pintype "output"))
      (node (ref "IC20") (pin "1") (pinfunction "I0_1") (pintype "input"))
      (node (ref "IC20") (pin "2") (pinfunction "I1_2") (pintype "input"))
      (node (ref "IC20") (pin "4") (pinfunction "I2_4") (pintype "input"))
      (node (ref "IC20") (pin "5") (pinfunction "I3_5") (pintype "input"))
      (node (ref "IC74") (pin "11") (pinfunction "CLK_11") (pintype "input"))
    )
    (net (code "595") (name "~{TS03}") (class "Default")
      (node (ref "IC88") (pin "3") (pinfunction "O_3") (pintype "output"))
      (node (ref "M916_23") (pin "H2") (pinfunction "P$2_H2") (pintype "bidirectional"))
      (node (ref "M916_23") (pin "J2") (pinfunction "P$2_J2") (pintype "bidirectional"))
      (node (ref "M916_23") (pin "K2") (pinfunction "P$2_K2") (pintype "bidirectional"))
    )
    (net (code "596") (name "~{T_00}") (class "Default")
      (node (ref "M916_16") (pin "V2") (pinfunction "P$2_V2") (pintype "bidirectional"))
      (node (ref "M916_17") (pin "V2") (pinfunction "P$2_V2") (pintype "bidirectional"))
      (node (ref "M916_8") (pin "V2") (pinfunction "P$2_V2") (pintype "bidirectional"))
    )
    (net (code "597") (name "~{T_01}") (class "Default")
      (node (ref "M916_17") (pin "M2") (pinfunction "P$2_M2") (pintype "bidirectional"))
      (node (ref "M916_7") (pin "S1") (pinfunction "P$2_S1") (pintype "bidirectional"))
      (node (ref "M916_8") (pin "M2") (pinfunction "P$2_M2") (pintype "bidirectional"))
    )
    (net (code "598") (name "~{T_02}") (class "Default")
      (node (ref "M916_17") (pin "N2") (pinfunction "P$2_N2") (pintype "bidirectional"))
      (node (ref "M916_7") (pin "H2") (pinfunction "P$2_H2") (pintype "bidirectional"))
      (node (ref "M916_8") (pin "N2") (pinfunction "P$2_N2") (pintype "bidirectional"))
    )
    (net (code "599") (name "~{T_03}") (class "Default")
      (node (ref "M916_17") (pin "P2") (pinfunction "P$2_P2") (pintype "bidirectional"))
      (node (ref "M916_7") (pin "J2") (pinfunction "P$2_J2") (pintype "bidirectional"))
      (node (ref "M916_8") (pin "P2") (pinfunction "P$2_P2") (pintype "bidirectional"))
    )
    (net (code "600") (name "~{T_04}") (class "Default")
      (node (ref "M916_17") (pin "R2") (pinfunction "P$2_R2") (pintype "bidirectional"))
      (node (ref "M916_7") (pin "N2") (pinfunction "P$2_N2") (pintype "bidirectional"))
      (node (ref "M916_8") (pin "R2") (pinfunction "P$2_R2") (pintype "bidirectional"))
    )
    (net (code "601") (name "~{T_05}") (class "Default")
      (node (ref "M916_17") (pin "S2") (pinfunction "P$2_S2") (pintype "bidirectional"))
      (node (ref "M916_7") (pin "P2") (pinfunction "P$2_P2") (pintype "bidirectional"))
      (node (ref "M916_8") (pin "S2") (pinfunction "P$2_S2") (pintype "bidirectional"))
    )
    (net (code "602") (name "~{T_06}") (class "Default")
      (node (ref "M916_17") (pin "T2") (pinfunction "P$2_T2") (pintype "bidirectional"))
      (node (ref "M916_7") (pin "U2") (pinfunction "P$2_U2") (pintype "bidirectional"))
      (node (ref "M916_8") (pin "T2") (pinfunction "P$2_T2") (pintype "bidirectional"))
    )
    (net (code "603") (name "~{T_07}") (class "Default")
      (node (ref "M916_17") (pin "U2") (pinfunction "P$2_U2") (pintype "bidirectional"))
      (node (ref "M916_7") (pin "V2") (pinfunction "P$2_V2") (pintype "bidirectional"))
      (node (ref "M916_8") (pin "U2") (pinfunction "P$2_U2") (pintype "bidirectional"))
    )
    (net (code "604") (name "~{T_FWD}") (class "Default")
      (node (ref "M916_17") (pin "H2") (pinfunction "P$2_H2") (pintype "bidirectional"))
      (node (ref "M916_7") (pin "K1") (pinfunction "P$2_K1") (pintype "bidirectional"))
      (node (ref "M916_8") (pin "E2") (pinfunction "P$2_E2") (pintype "bidirectional"))
    )
    (net (code "605") (name "~{T_GO}") (class "Default")
      (node (ref "M916_17") (pin "D2") (pinfunction "P$2_D2") (pintype "bidirectional"))
      (node (ref "M916_8") (pin "C2") (pinfunction "P$2_C2") (pintype "bidirectional"))
    )
    (net (code "606") (name "~{T_PWR_CLR}") (class "Default")
      (node (ref "M916_17") (pin "K2") (pinfunction "P$2_K2") (pintype "bidirectional"))
      (node (ref "M916_7") (pin "R1") (pinfunction "P$2_R1") (pintype "bidirectional"))
      (node (ref "M916_8") (pin "H2") (pinfunction "P$2_H2") (pintype "bidirectional"))
    )
    (net (code "607") (name "~{T_REV}") (class "Default")
      (node (ref "M916_17") (pin "J2") (pinfunction "P$2_J2") (pintype "bidirectional"))
      (node (ref "M916_7") (pin "L1") (pinfunction "P$2_L1") (pintype "bidirectional"))
      (node (ref "M916_8") (pin "F2") (pinfunction "P$2_F2") (pintype "bidirectional"))
    )
    (net (code "608") (name "~{T_SINGLE_UNIT}") (class "Default")
      (node (ref "M916_15") (pin "T2") (pinfunction "P$2_T2") (pintype "bidirectional"))
      (node (ref "M916_8") (pin "K2") (pinfunction "P$2_K2") (pintype "bidirectional"))
    )
    (net (code "609") (name "~{T_STOP}") (class "Default")
      (node (ref "M916_17") (pin "E2") (pinfunction "P$2_E2") (pintype "bidirectional"))
      (node (ref "M916_7") (pin "E1") (pinfunction "P$2_E1") (pintype "bidirectional"))
      (node (ref "M916_8") (pin "D2") (pinfunction "P$2_D2") (pintype "bidirectional"))
    )
    (net (code "610") (name "~{T_TRK}") (class "Default")
      (node (ref "IC61") (pin "10") (pinfunction "I1_10") (pintype "input"))
      (node (ref "M916_3") (pin "V2") (pinfunction "P$2_V2") (pintype "bidirectional"))
    )
    (net (code "611") (name "~{T_WRITE_OK}") (class "Default")
      (node (ref "M916_17") (pin "L2") (pinfunction "P$2_L2") (pintype "bidirectional"))
      (node (ref "M916_6") (pin "H2") (pinfunction "P$2_H2") (pintype "bidirectional"))
      (node (ref "M916_8") (pin "L2") (pinfunction "P$2_L2") (pintype "bidirectional"))
    )
    (net (code "612") (name "~{U+M_DY}") (class "Default")
      (node (ref "IC108") (pin "1") (pinfunction "I0_1") (pintype "input"))
      (node (ref "IC110") (pin "13") (pinfunction "I2_13") (pintype "input"))
      (node (ref "M916_20") (pin "E2") (pinfunction "P$2_E2") (pintype "bidirectional"))
      (node (ref "M916_20") (pin "N1") (pinfunction "P$2_N1") (pintype "bidirectional"))
    )
    (net (code "613") (name "~{USR_00}") (class "Default")
      (node (ref "IC30") (pin "2") (pinfunction "I0_2") (pintype "input"))
      (node (ref "IC56") (pin "13") (pinfunction "~{Q}_13") (pintype "output"))
    )
    (net (code "614") (name "~{USR_01}") (class "Default")
      (node (ref "IC30") (pin "5") (pinfunction "I0_5") (pintype "input"))
      (node (ref "IC56") (pin "8") (pinfunction "~{Q}_8") (pintype "output"))
    )
    (net (code "615") (name "~{USR_02}") (class "Default")
      (node (ref "IC30") (pin "8") (pinfunction "I0_8") (pintype "input"))
      (node (ref "IC57") (pin "13") (pinfunction "~{Q}_13") (pintype "output"))
    )
    (net (code "616") (name "~{UTS}") (class "Default")
      (node (ref "IC109") (pin "11") (pinfunction "I2_11") (pintype "input"))
      (node (ref "IC114") (pin "9") (pinfunction "Q_9") (pintype "output"))
      (node (ref "IC118") (pin "1") (pinfunction "I0_1") (pintype "input"))
      (node (ref "IC119") (pin "1") (pinfunction "I0_1") (pintype "input"))
      (node (ref "IC119") (pin "2") (pinfunction "I1_2") (pintype "input"))
      (node (ref "IC119") (pin "4") (pinfunction "I2_4") (pintype "input"))
      (node (ref "IC119") (pin "5") (pinfunction "I3_5") (pintype "input"))
      (node (ref "IC67") (pin "10") (pinfunction "I1_10") (pintype "input"))
      (node (ref "IC67") (pin "12") (pinfunction "I2_12") (pintype "input"))
      (node (ref "IC67") (pin "13") (pinfunction "I3_13") (pintype "input"))
      (node (ref "IC67") (pin "9") (pinfunction "I0_9") (pintype "input"))
    )
    (net (code "617") (name "~{W-INH}") (class "Default")
      (node (ref "IC68") (pin "2") (pinfunction "I1_2") (pintype "input"))
      (node (ref "IC7") (pin "9") (pinfunction "Q_9") (pintype "output"))
      (node (ref "IC70") (pin "10") (pinfunction "I1_10") (pintype "input"))
    )
    (net (code "618") (name "~{WB00}") (class "Default")
      (node (ref "IC103") (pin "5") (pinfunction "2D_5") (pintype "input"))
      (node (ref "IC113") (pin "5") (pinfunction "Q_5") (pintype "output"))
      (node (ref "M916_13") (pin "P2") (pinfunction "P$2_P2") (pintype "bidirectional"))
      (node (ref "M916_5") (pin "P2") (pinfunction "P$2_P2") (pintype "bidirectional"))
    )
    (net (code "619") (name "~{WB01}") (class "Default")
      (node (ref "IC105") (pin "10") (pinfunction "1E_10") (pintype "input"))
      (node (ref "IC113") (pin "9") (pinfunction "Q_9") (pintype "output"))
      (node (ref "M916_14") (pin "P2") (pinfunction "P$2_P2") (pintype "bidirectional"))
    )
    (net (code "620") (name "~{WB02}") (class "Default")
      (node (ref "IC104") (pin "5") (pinfunction "2D_5") (pintype "input"))
      (node (ref "IC114") (pin "5") (pinfunction "Q_5") (pintype "output"))
      (node (ref "M916_4") (pin "P2") (pinfunction "P$2_P2") (pintype "bidirectional"))
    )
    (net (code "621") (name "~{WC0}") (class "Default")
      (node (ref "IC137") (pin "10") (pinfunction "PRE_10") (pintype "input"))
      (node (ref "IC93") (pin "2") (pinfunction "O_2") (pintype "output"))
    )
    (net (code "622") (name "~{WC}") (class "Default")
      (node (ref "IC110") (pin "3") (pinfunction "I0_3") (pintype "input"))
      (node (ref "IC137") (pin "2") (pinfunction "D_2") (pintype "input"))
      (node (ref "IC137") (pin "8") (pinfunction "~{Q}_8") (pintype "output"))
      (node (ref "IC71") (pin "12") (pinfunction "I2_12") (pintype "input"))
    )
    (net (code "623") (name "~{WRITE_ALL}") (class "Default")
      (node (ref "IC124") (pin "6") (pinfunction "5_6") (pintype "output"))
      (node (ref "IC125") (pin "9") (pinfunction "I_9") (pintype "input"))
    )
    (net (code "624") (name "~{WRITE_DATA}") (class "Default")
      (node (ref "IC124") (pin "5") (pinfunction "4_5") (pintype "output"))
      (node (ref "IC125") (pin "5") (pinfunction "I_5") (pintype "input"))
      (node (ref "IC60") (pin "10") (pinfunction "I1_10") (pintype "input"))
    )
    (net (code "625") (name "~{WRITE_OK}") (class "Default")
      (node (ref "IC11") (pin "13") (pinfunction "I1_13") (pintype "input"))
      (node (ref "IC122") (pin "8") (pinfunction "O_8") (pintype "output"))
    )
    (net (code "626") (name "~{WRTM}") (class "Default")
      (node (ref "IC104") (pin "9") (pinfunction "1D_9") (pintype "input"))
      (node (ref "IC124") (pin "7") (pinfunction "6_7") (pintype "output"))
      (node (ref "IC125") (pin "11") (pinfunction "I_11") (pintype "input"))
      (node (ref "IC60") (pin "1") (pinfunction "I0_1") (pintype "input"))
    )
    (net (code "627") (name "~{WR_EN}") (class "Default")
      (node (ref "IC106") (pin "9") (pinfunction "I0_9") (pintype "input"))
      (node (ref "IC109") (pin "9") (pinfunction "I0_9") (pintype "input"))
      (node (ref "IC115") (pin "5") (pinfunction "Q_5") (pintype "output"))
      (node (ref "IC116") (pin "9") (pinfunction "I0_9") (pintype "input"))
      (node (ref "IC117") (pin "1") (pinfunction "I0_1") (pintype "input"))
      (node (ref "IC2") (pin "10") (pinfunction "I1_10") (pintype "input"))
    )
    (net (code "628") (name "~{XSAD}") (class "Default")
      (node (ref "IC14") (pin "11") (pinfunction "I_11") (pintype "input"))
      (node (ref "M916_19") (pin "L2") (pinfunction "P$2_L2") (pintype "bidirectional"))
    )
    (net (code "629") (name "~{XSTA}") (class "Default")
      (node (ref "IC55") (pin "13") (pinfunction "I_13") (pintype "input"))
      (node (ref "IC61") (pin "2") (pinfunction "I1_2") (pintype "input"))
      (node (ref "IC87") (pin "11") (pinfunction "O_11") (pintype "output"))
      (node (ref "M916_19") (pin "H2") (pinfunction "P$2_H2") (pintype "bidirectional"))
      (node (ref "M916_19") (pin "J2") (pinfunction "P$2_J2") (pintype "bidirectional"))
      (node (ref "M916_19") (pin "K2") (pinfunction "P$2_K2") (pintype "bidirectional"))
      (node (ref "M916_20") (pin "K2") (pinfunction "P$2_K2") (pintype "bidirectional"))
      (node (ref "M916_20") (pin "L2") (pinfunction "P$2_L2") (pintype "bidirectional"))
      (node (ref "M916_22") (pin "M2") (pinfunction "P$2_M2") (pintype "bidirectional"))
      (node (ref "M916_22") (pin "N2") (pinfunction "P$2_N2") (pintype "bidirectional"))
    )
  )
)
